# ENERGIS_Rack-PDU_1_0_0.net
KiCad netlist of a schematic drawn in EAGLE
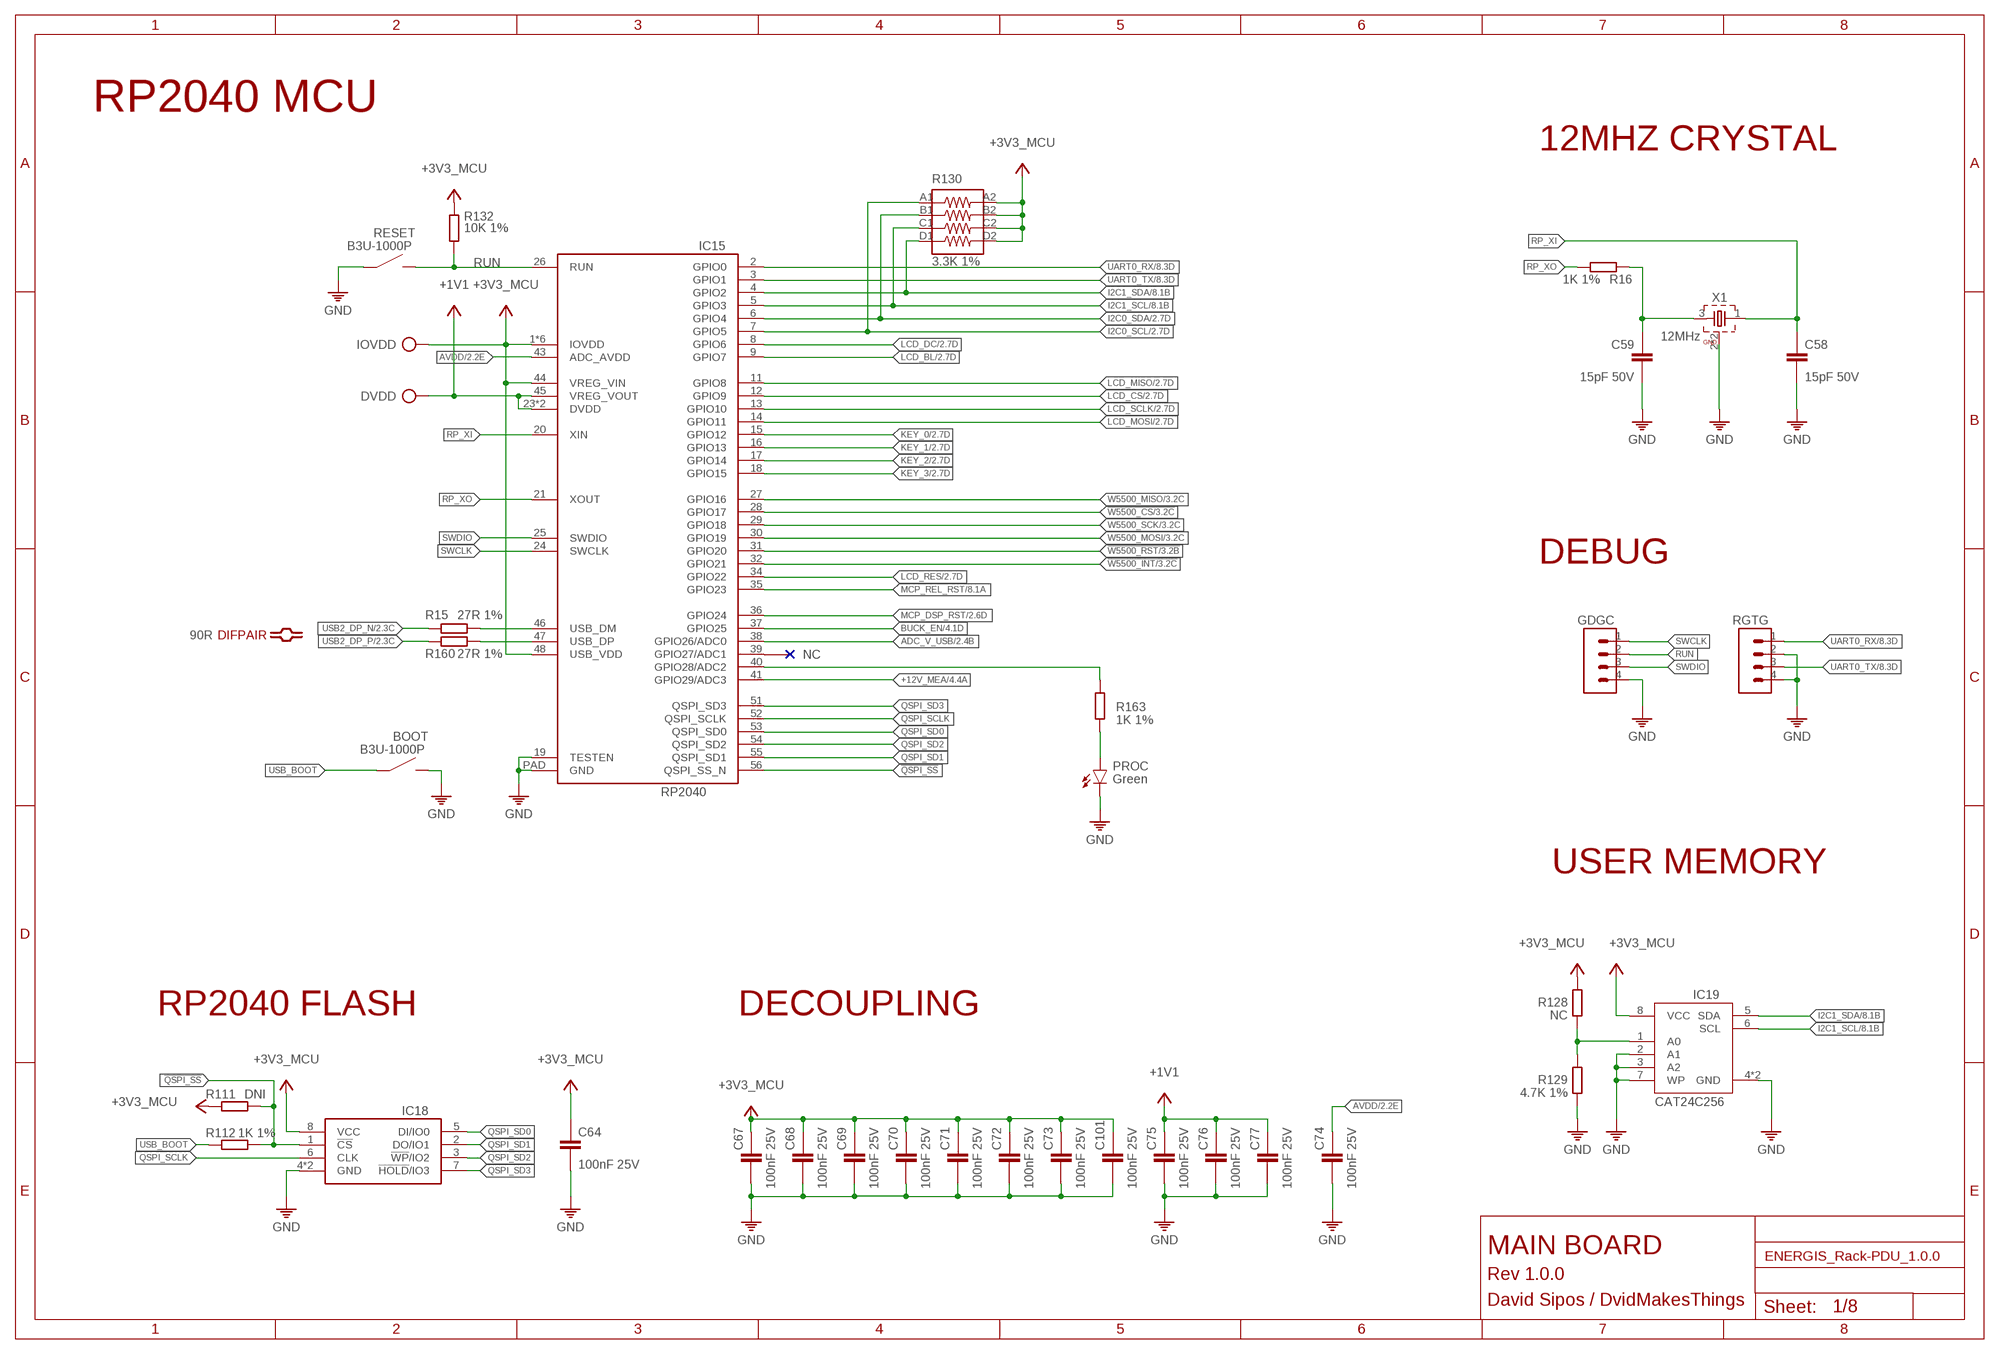
[diagram p0: schematic, sheet 1]
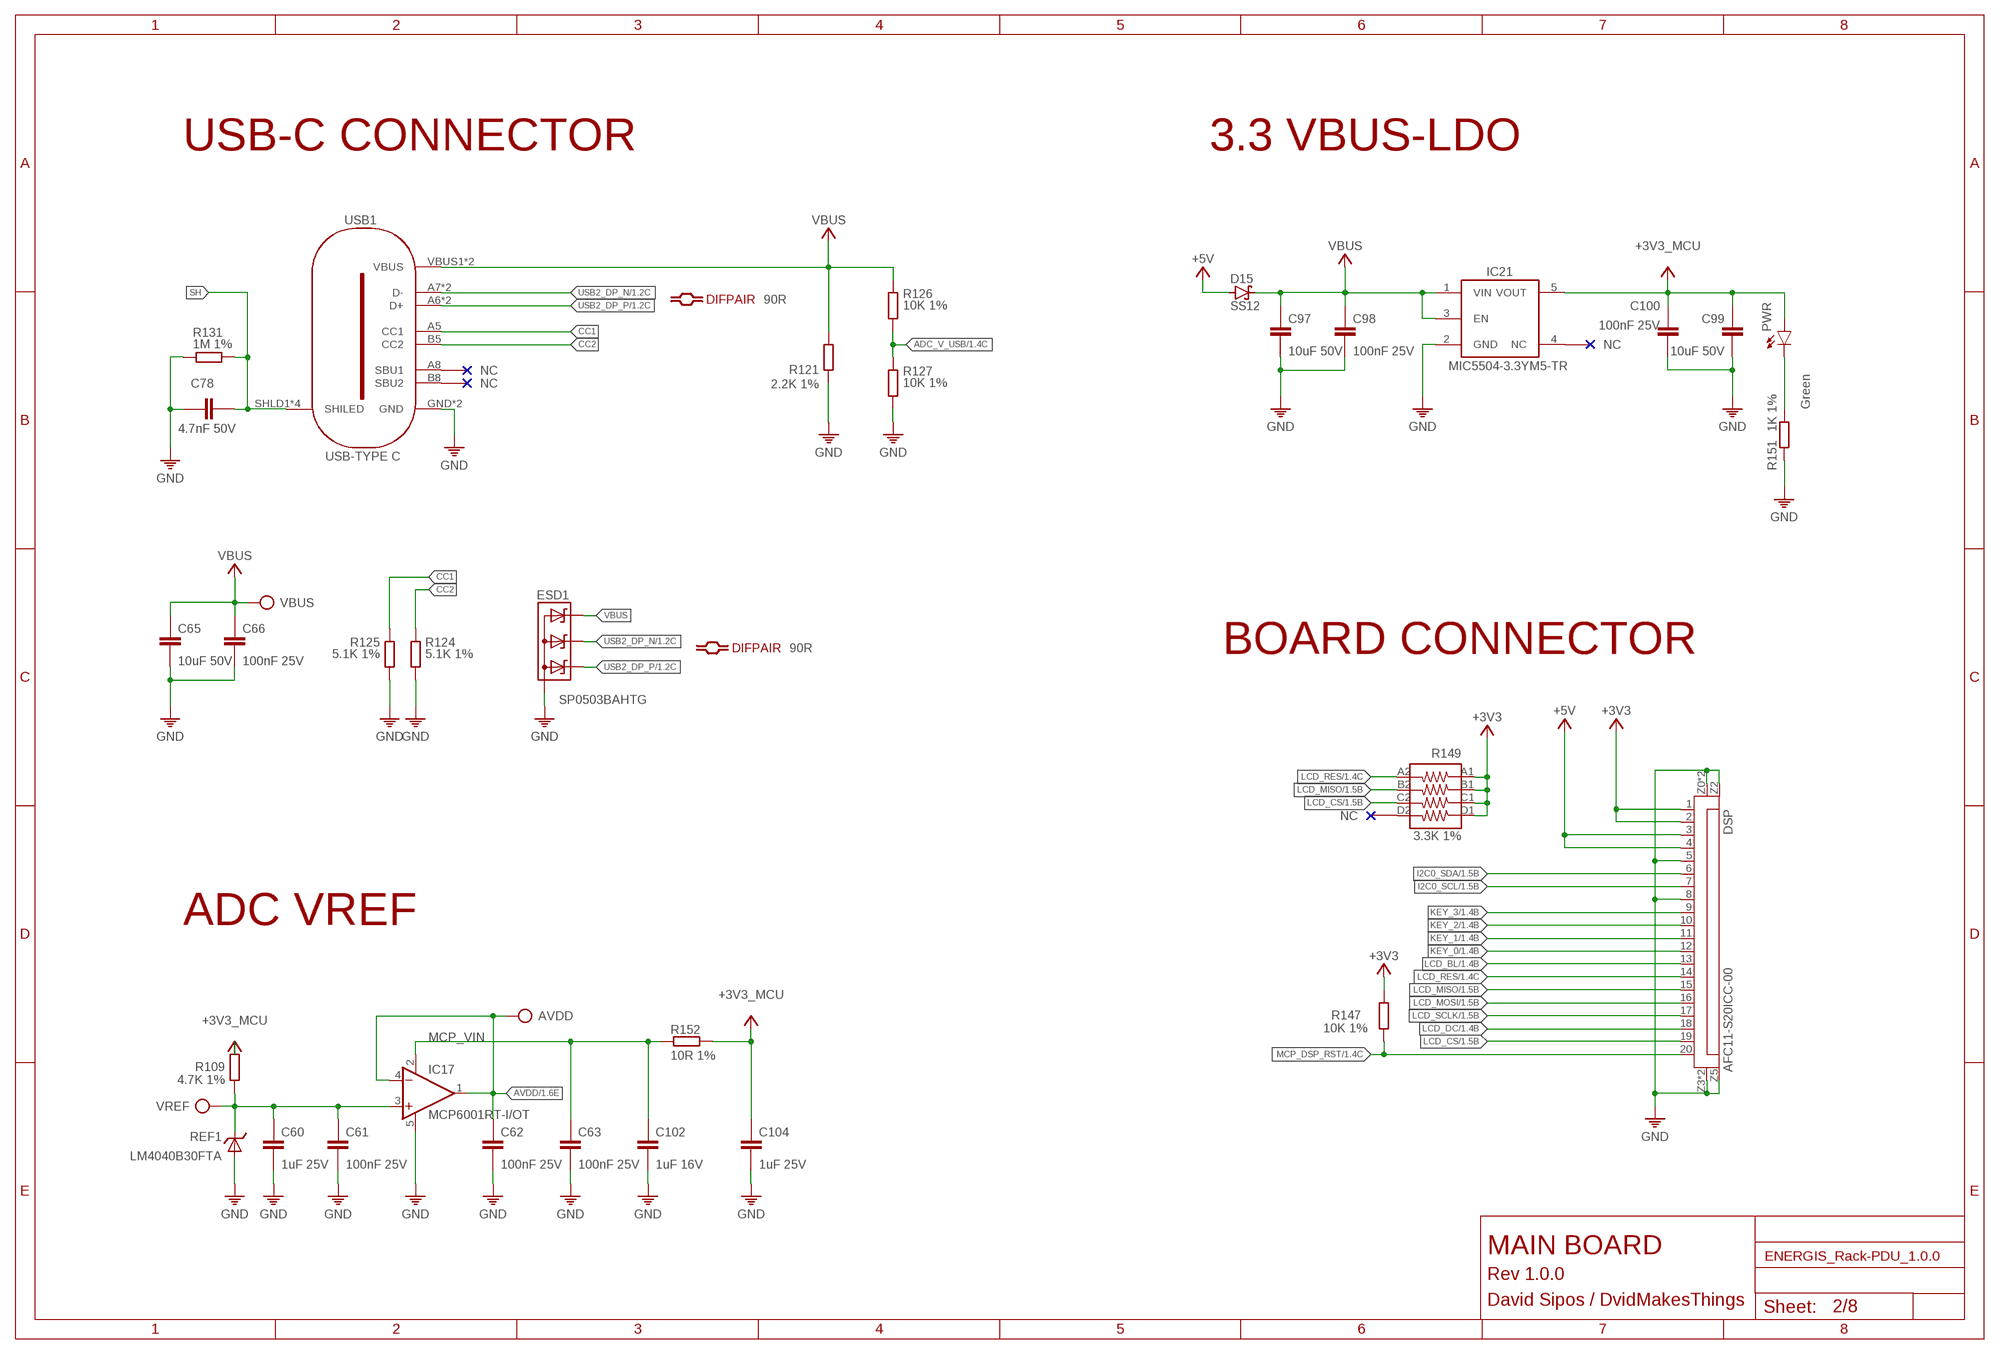
[diagram p1: schematic, sheet 2]
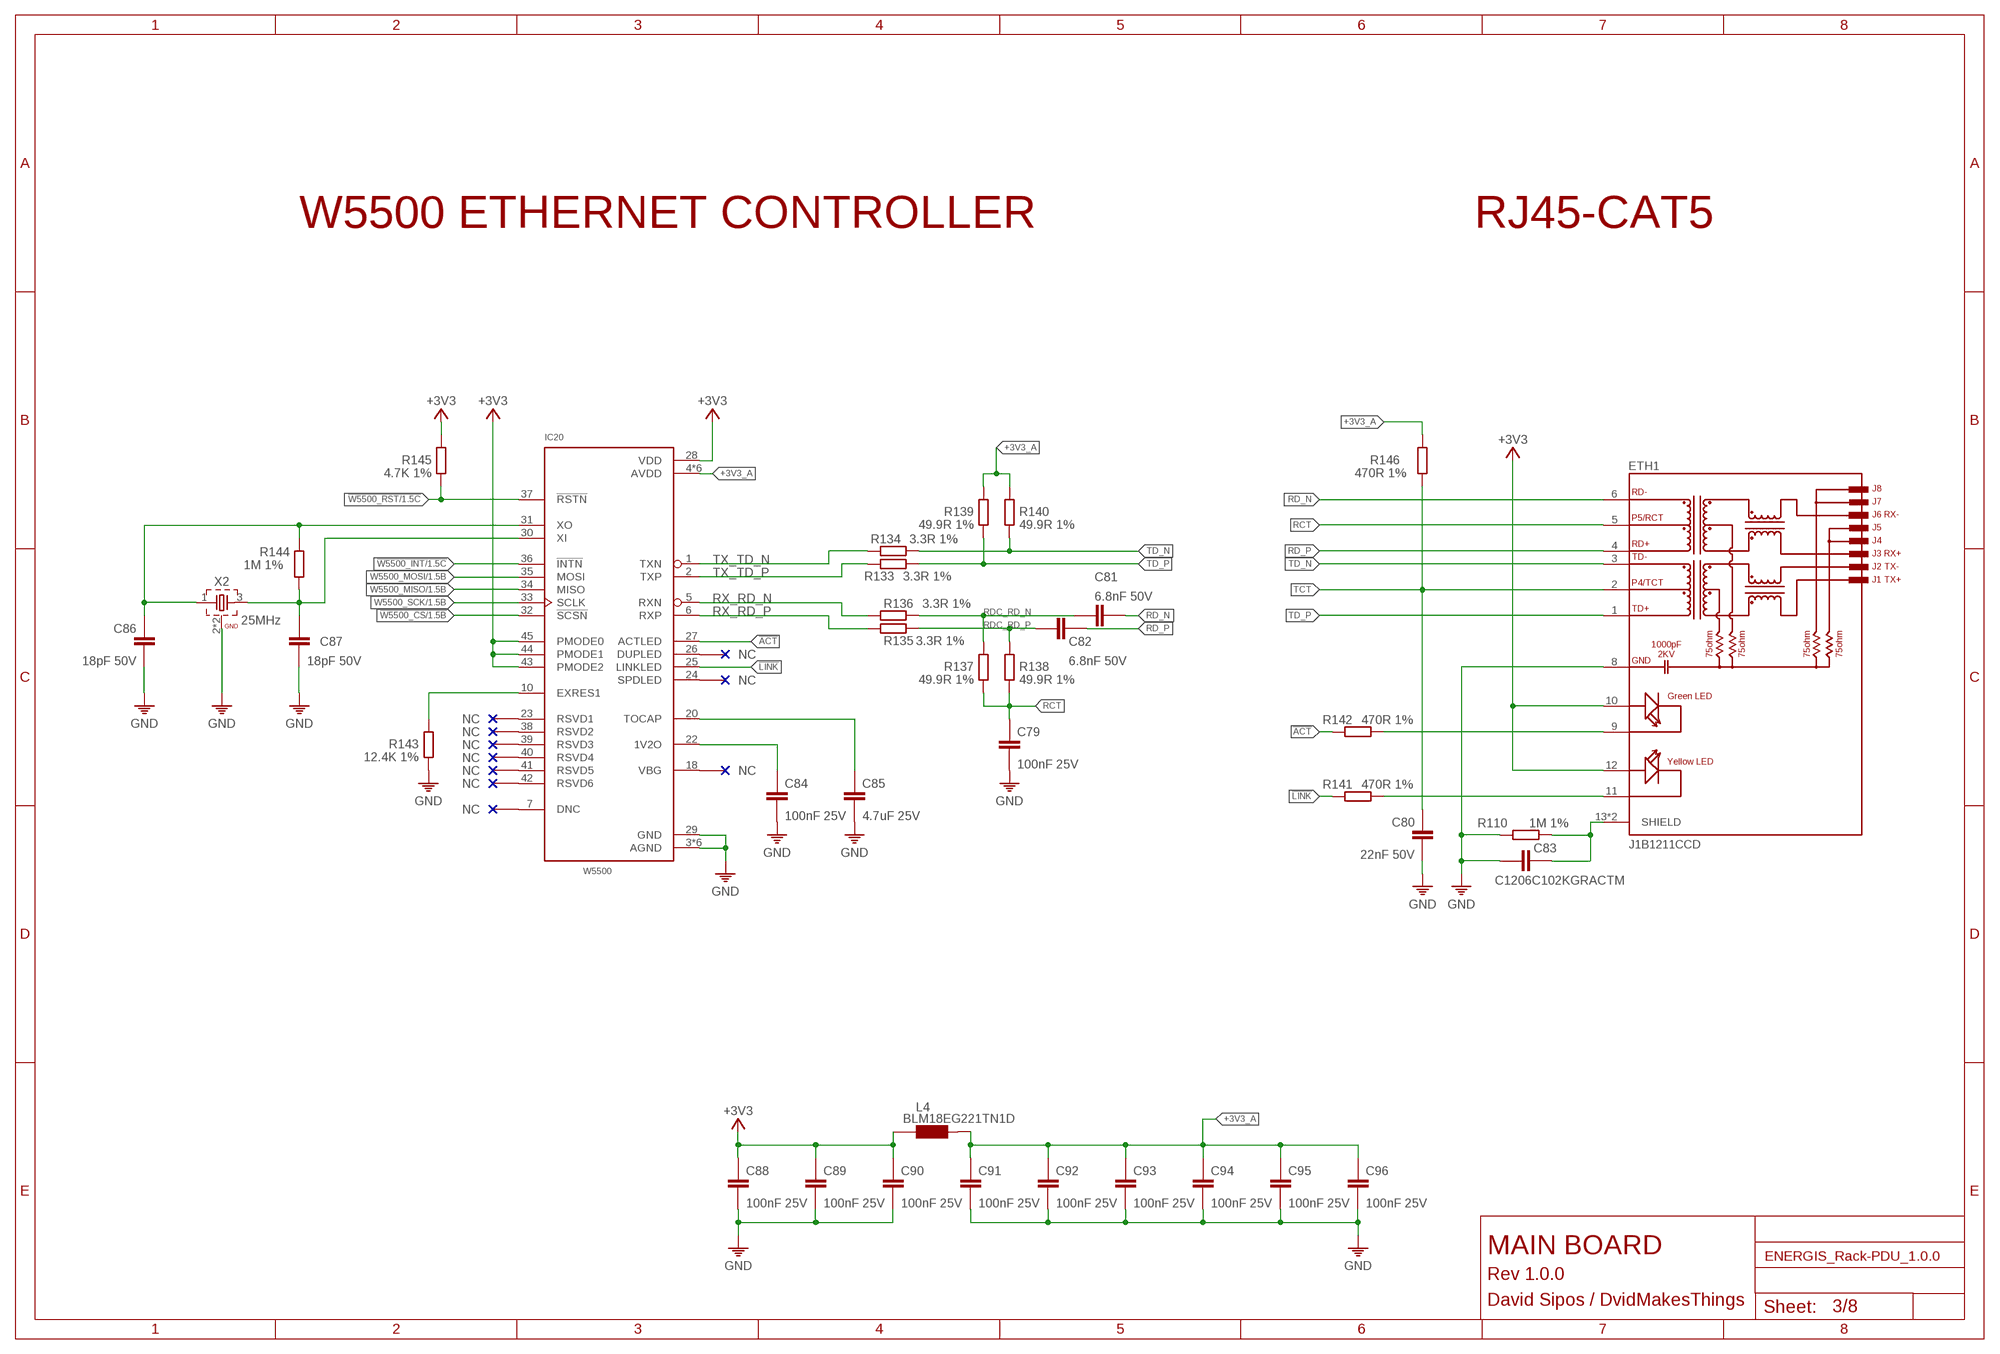
[diagram p2: schematic, sheet 3]
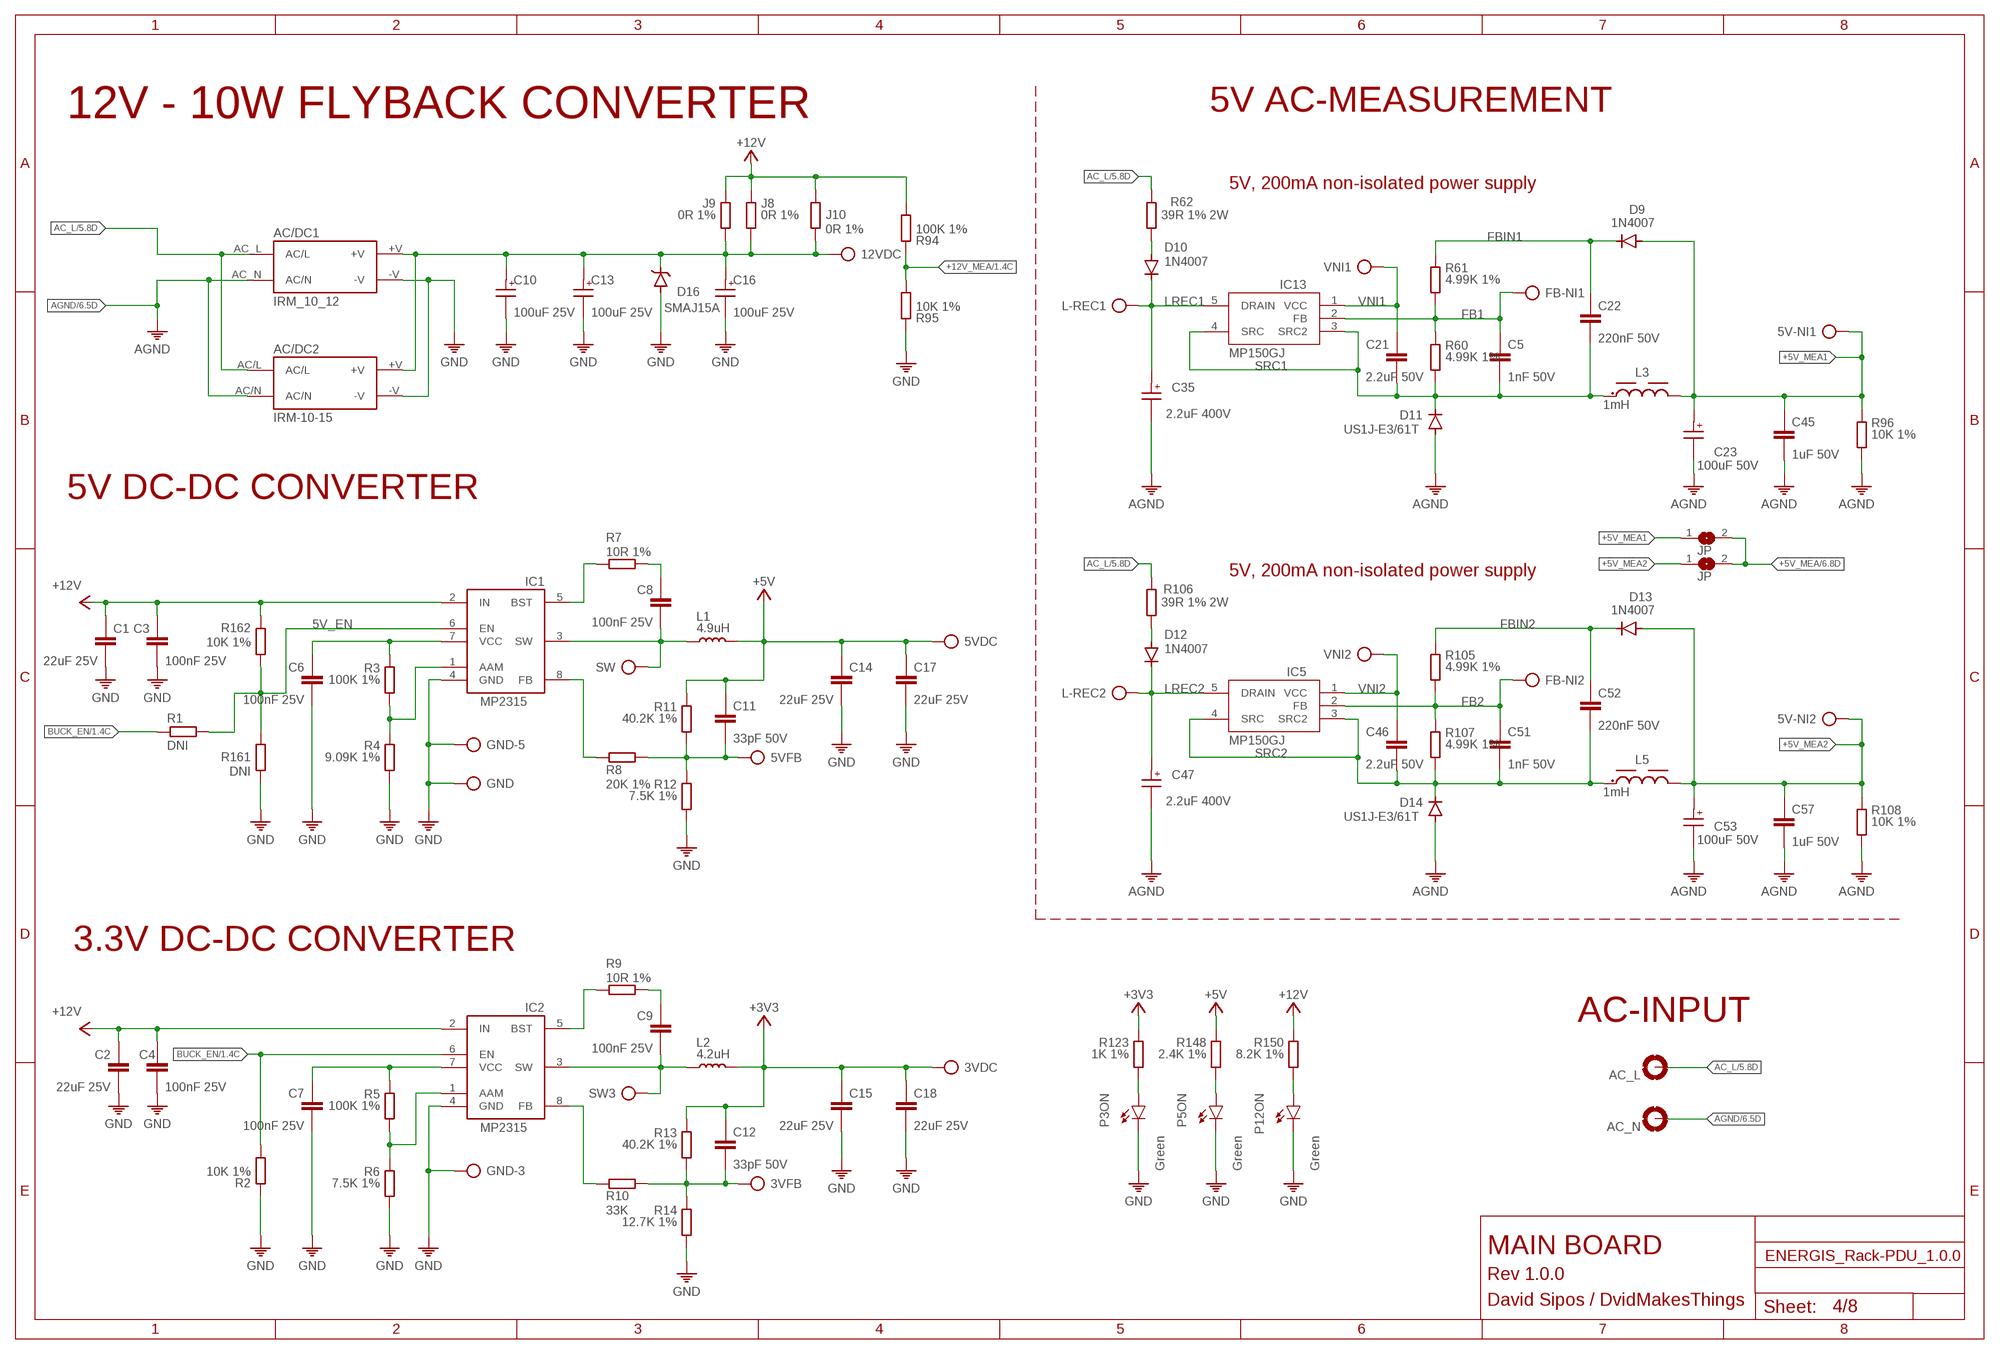
[diagram p3: schematic, sheet 4]
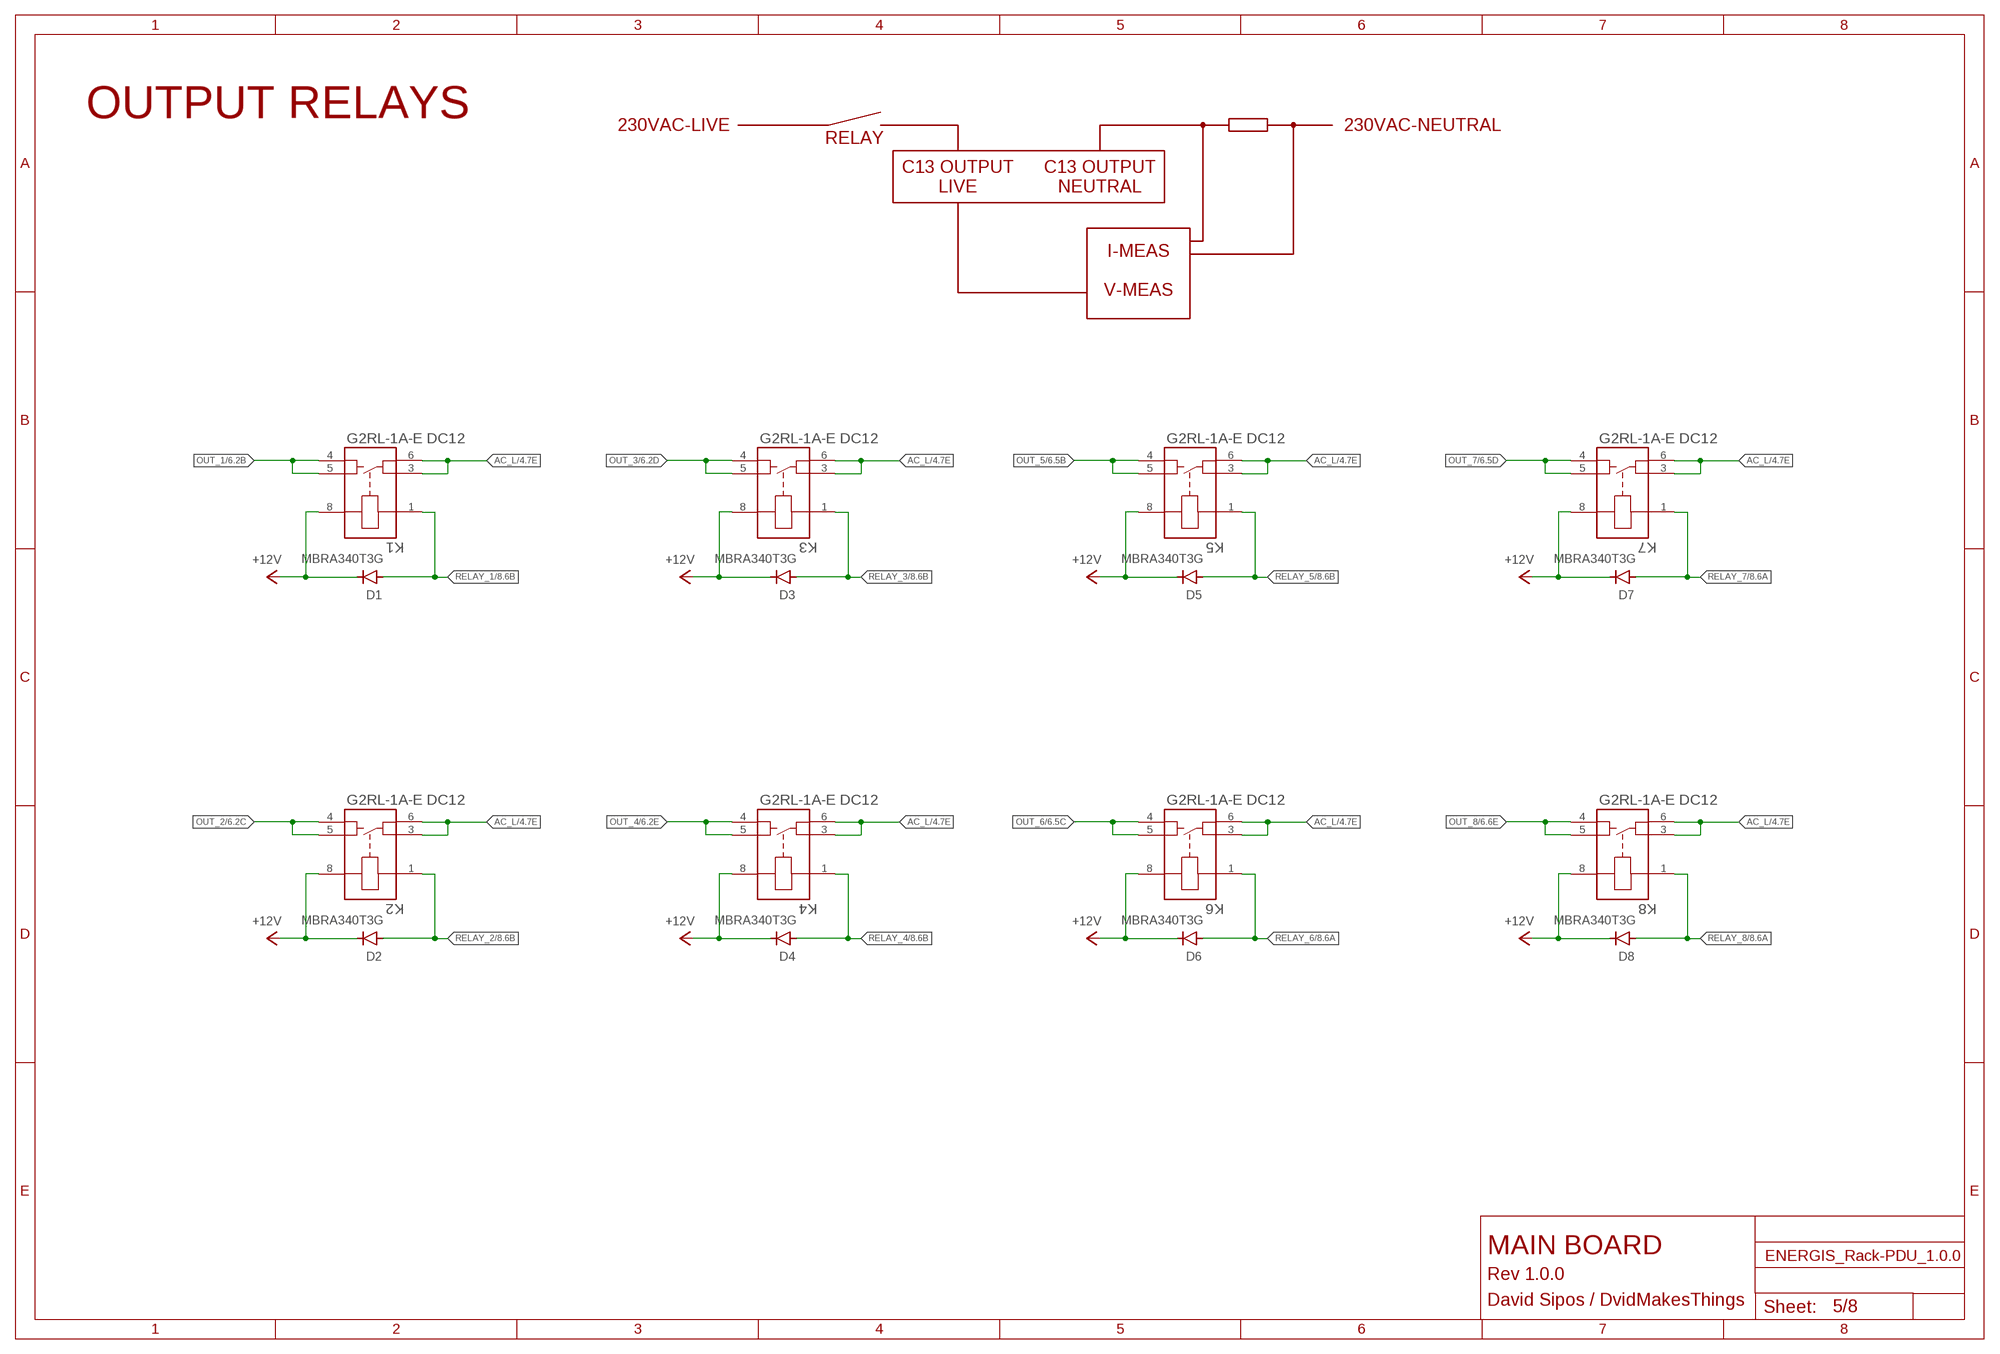
[diagram p4: schematic, sheet 5]
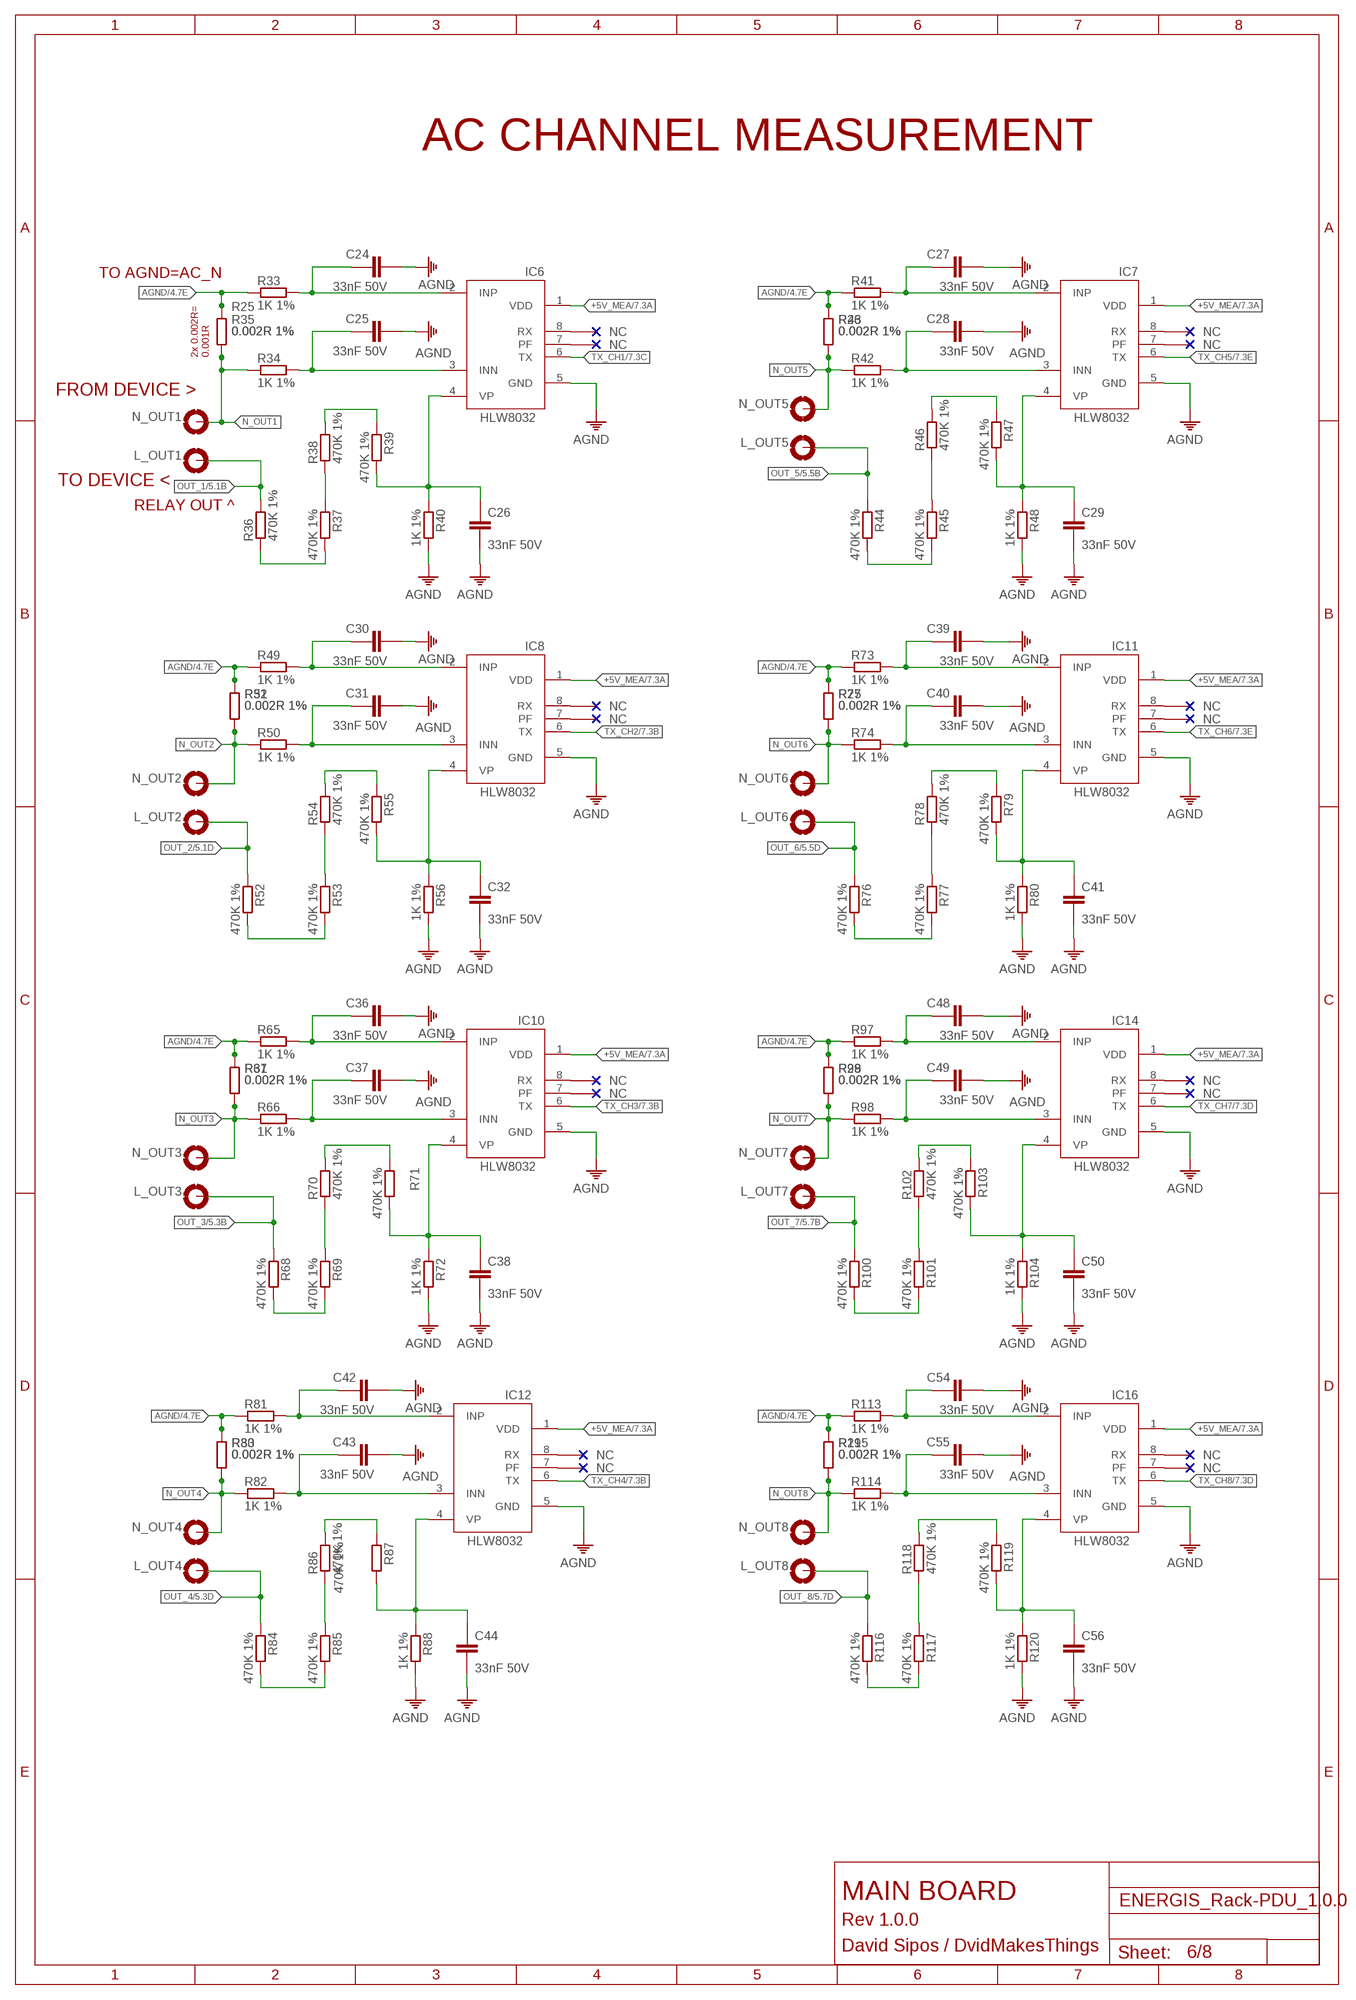
[diagram p5: schematic, sheet 6]
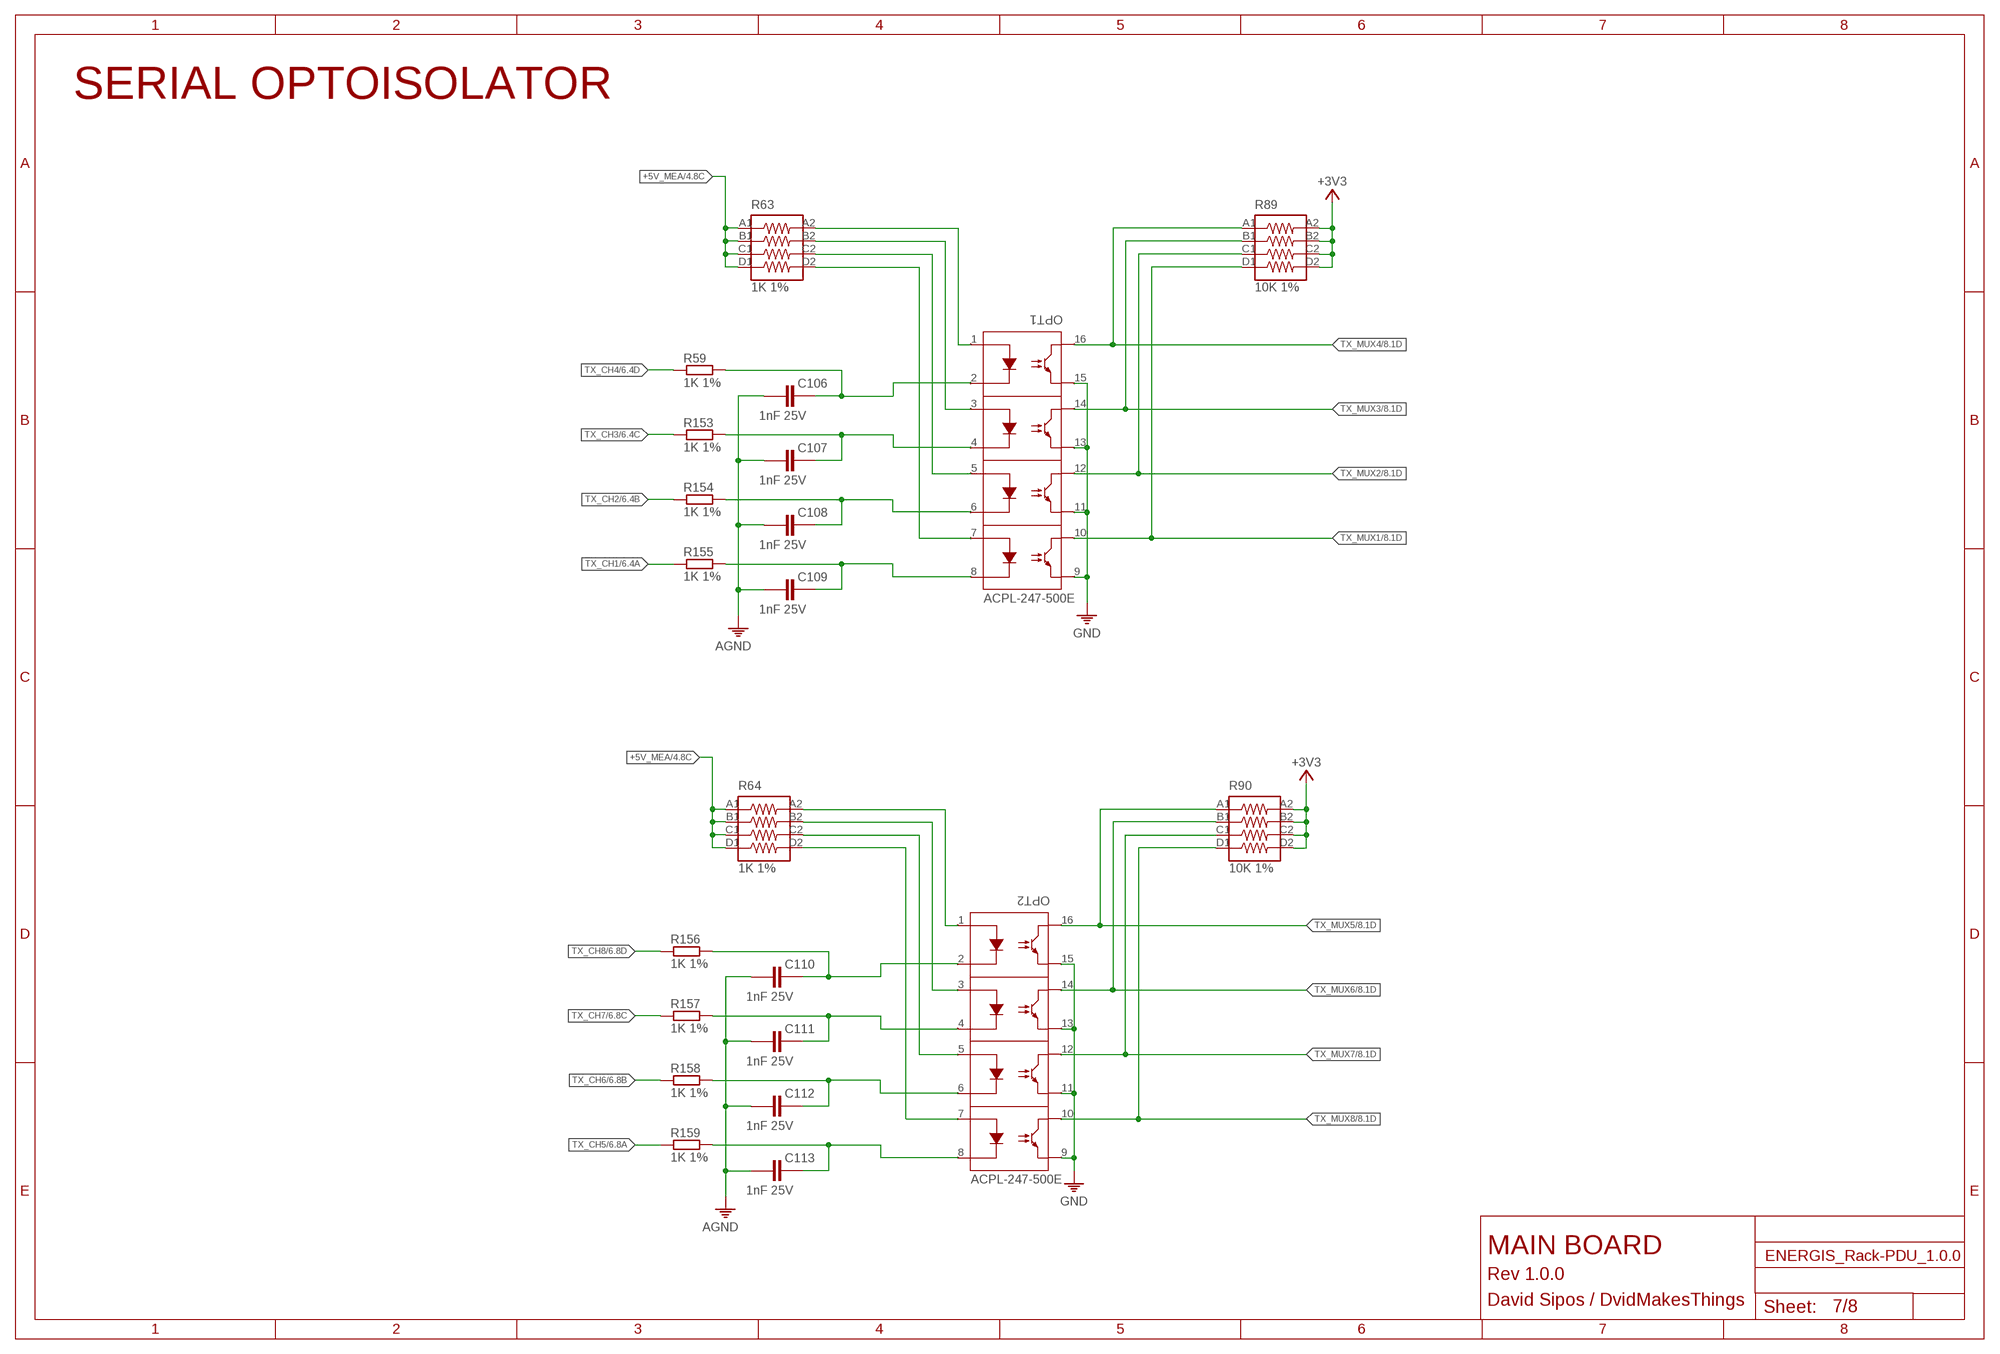
[diagram p6: schematic, sheet 7]
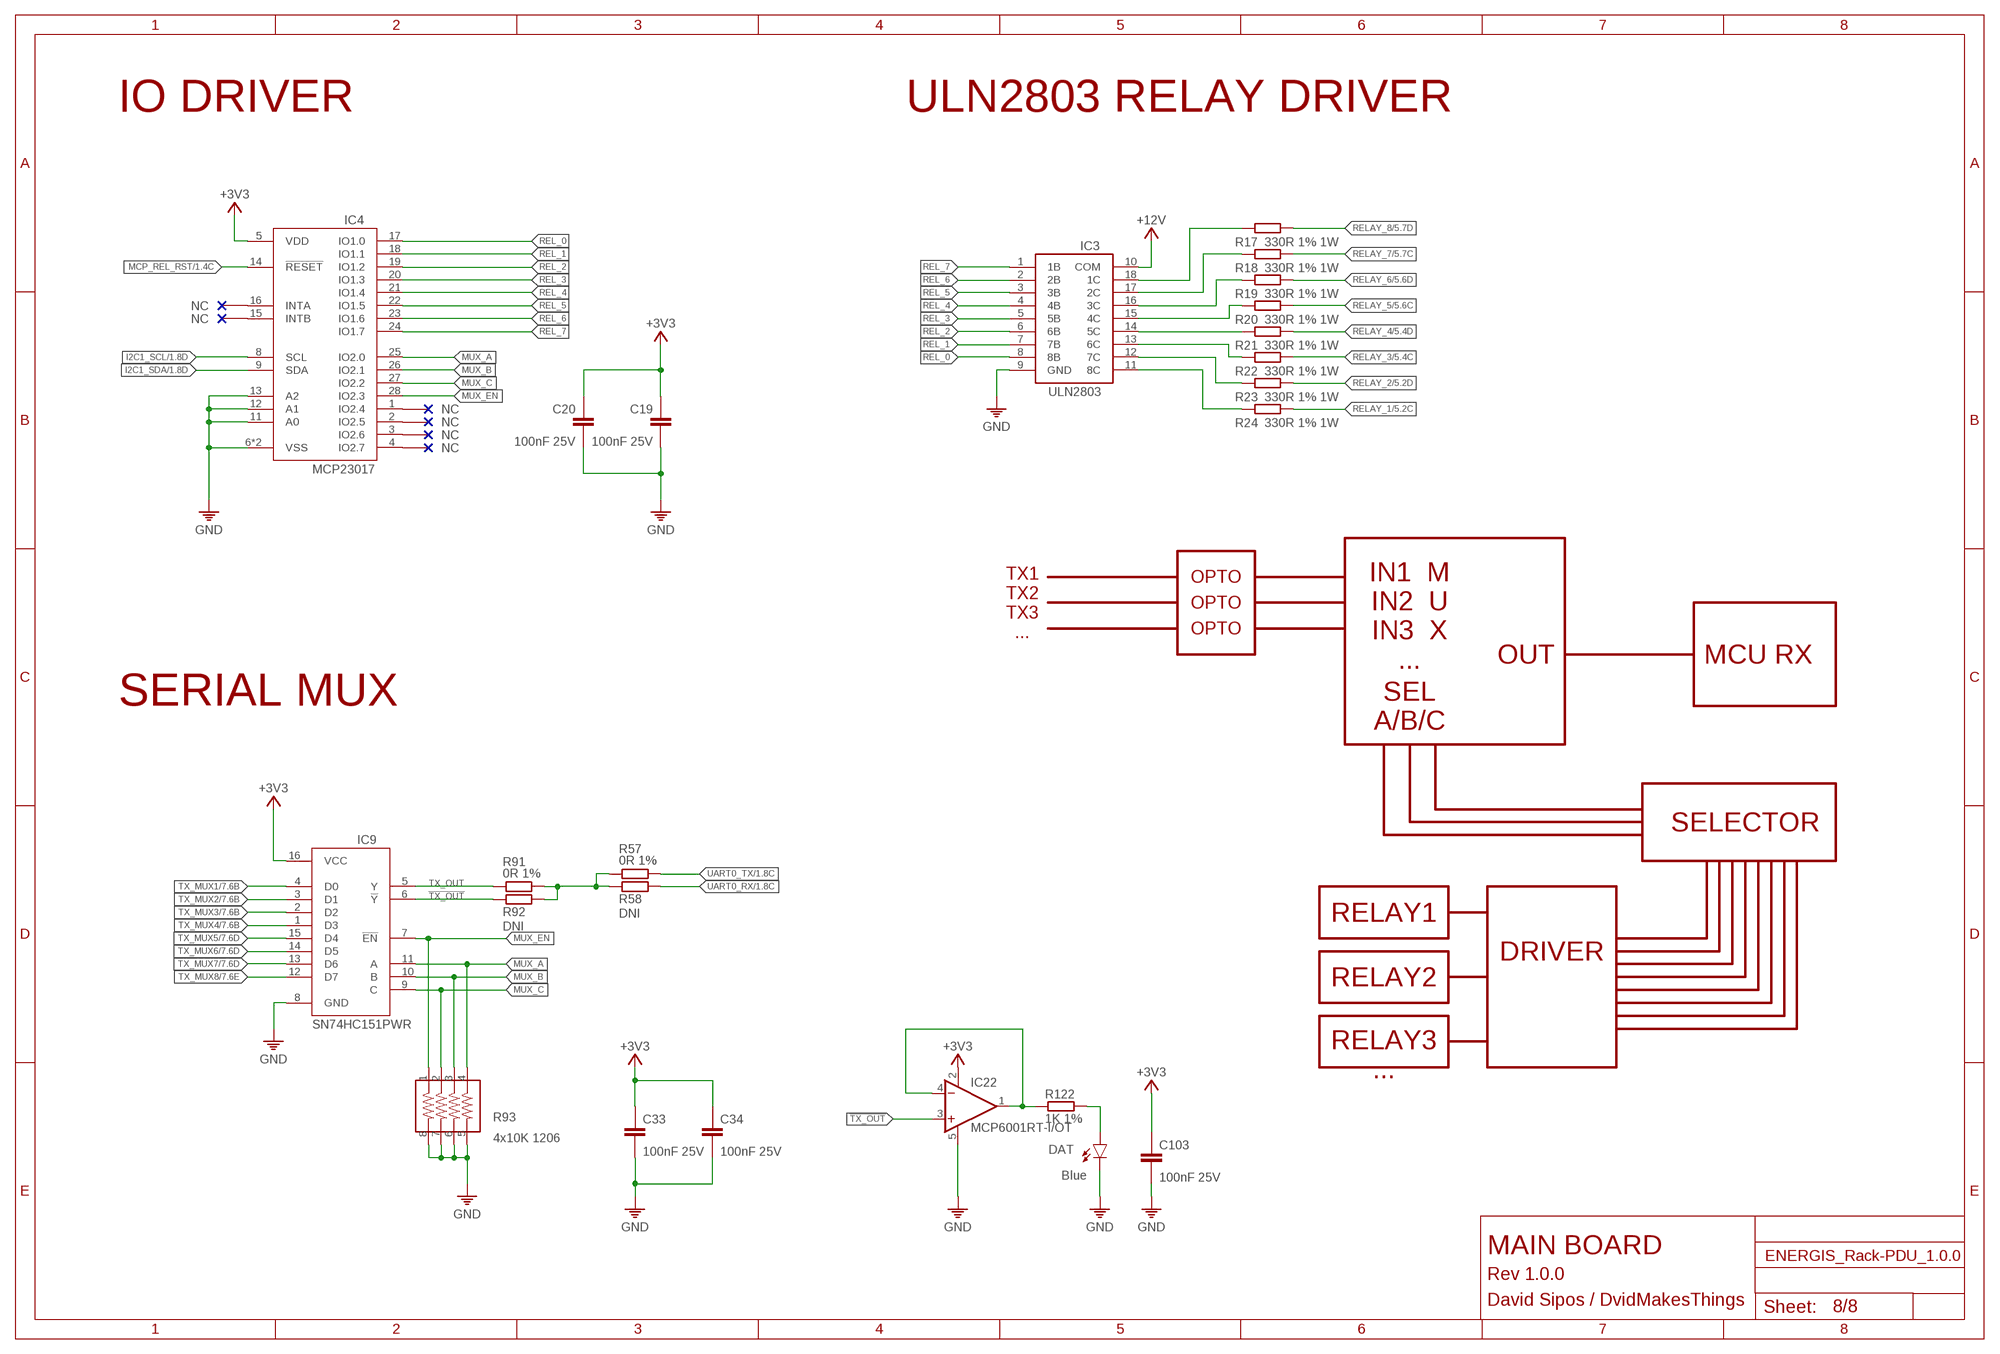
[diagram p7: schematic, sheet 8]

(export (version "E")
  (design (tool "Eeschema 10.0.6"))
  (components
    (comp (ref "D1")
      (value "MBRA340T3G")
      (footprint "eagle-import:SMA_DO-214AC")
      (fields (field (name "LCSC_PART") "C26178"))
      (libsource (lib "eagle-import") (part "MBRA340T3G"))
    )
    (comp (ref "D2")
      (value "MBRA340T3G")
      (footprint "eagle-import:SMA_DO-214AC")
      (fields (field (name "LCSC_PART") "C26178"))
      (libsource (lib "eagle-import") (part "MBRA340T3G"))
    )
    (comp (ref "D3")
      (value "MBRA340T3G")
      (footprint "eagle-import:SMA_DO-214AC")
      (fields (field (name "LCSC_PART") "C26178"))
      (libsource (lib "eagle-import") (part "MBRA340T3G"))
    )
    (comp (ref "D4")
      (value "MBRA340T3G")
      (footprint "eagle-import:SMA_DO-214AC")
      (fields (field (name "LCSC_PART") "C26178"))
      (libsource (lib "eagle-import") (part "MBRA340T3G"))
    )
    (comp (ref "D5")
      (value "MBRA340T3G")
      (footprint "eagle-import:SMA_DO-214AC")
      (fields (field (name "LCSC_PART") "C26178"))
      (libsource (lib "eagle-import") (part "MBRA340T3G"))
    )
    (comp (ref "D6")
      (value "MBRA340T3G")
      (footprint "eagle-import:SMA_DO-214AC")
      (fields (field (name "LCSC_PART") "C26178"))
      (libsource (lib "eagle-import") (part "MBRA340T3G"))
    )
    (comp (ref "D7")
      (value "MBRA340T3G")
      (footprint "eagle-import:SMA_DO-214AC")
      (fields (field (name "LCSC_PART") "C26178"))
      (libsource (lib "eagle-import") (part "MBRA340T3G"))
    )
    (comp (ref "D8")
      (value "MBRA340T3G")
      (footprint "eagle-import:SMA_DO-214AC")
      (fields (field (name "LCSC_PART") "C26178"))
      (libsource (lib "eagle-import") (part "MBRA340T3G"))
    )
    (comp (ref "K1")
      (value "G2RL-1A-E DC12")
      (footprint "eagle-import:RELAY_G2RL-1A-E_DC5_OMR")
      (fields (field (name "LCSC_PART") "C1564126"))
      (libsource (lib "eagle-import") (part "G2RL-1A-E_DC12"))
    )
    (comp (ref "K2")
      (value "G2RL-1A-E DC12")
      (footprint "eagle-import:RELAY_G2RL-1A-E_DC5_OMR")
      (fields (field (name "LCSC_PART") "C1564126"))
      (libsource (lib "eagle-import") (part "G2RL-1A-E_DC12"))
    )
    (comp (ref "K3")
      (value "G2RL-1A-E DC12")
      (footprint "eagle-import:RELAY_G2RL-1A-E_DC5_OMR")
      (fields (field (name "LCSC_PART") "C1564126"))
      (libsource (lib "eagle-import") (part "G2RL-1A-E_DC12"))
    )
    (comp (ref "K4")
      (value "G2RL-1A-E DC12")
      (footprint "eagle-import:RELAY_G2RL-1A-E_DC5_OMR")
      (fields (field (name "LCSC_PART") "C1564126"))
      (libsource (lib "eagle-import") (part "G2RL-1A-E_DC12"))
    )
    (comp (ref "K5")
      (value "G2RL-1A-E DC12")
      (footprint "eagle-import:RELAY_G2RL-1A-E_DC5_OMR")
      (fields (field (name "LCSC_PART") "C1564126"))
      (libsource (lib "eagle-import") (part "G2RL-1A-E_DC12"))
    )
    (comp (ref "K6")
      (value "G2RL-1A-E DC12")
      (footprint "eagle-import:RELAY_G2RL-1A-E_DC5_OMR")
      (fields (field (name "LCSC_PART") "C1564126"))
      (libsource (lib "eagle-import") (part "G2RL-1A-E_DC12"))
    )
    (comp (ref "K7")
      (value "G2RL-1A-E DC12")
      (footprint "eagle-import:RELAY_G2RL-1A-E_DC5_OMR")
      (fields (field (name "LCSC_PART") "C1564126"))
      (libsource (lib "eagle-import") (part "G2RL-1A-E_DC12"))
    )
    (comp (ref "K8")
      (value "G2RL-1A-E DC12")
      (footprint "eagle-import:RELAY_G2RL-1A-E_DC5_OMR")
      (fields (field (name "LCSC_PART") "C1564126"))
      (libsource (lib "eagle-import") (part "G2RL-1A-E_DC12"))
    )
    (comp (ref "C19")
      (value "100nF 25V")
      (footprint "eagle-import:0402")
      (fields (field (name "LCSC_PART") "C56392"))
      (libsource (lib "eagle-import") (part "100NF-25V-0402"))
    )
    (comp (ref "C20")
      (value "100nF 25V")
      (footprint "eagle-import:0402")
      (fields (field (name "LCSC_PART") "C56392"))
      (libsource (lib "eagle-import") (part "100NF-25V-0402"))
    )
    (comp (ref "C33")
      (value "100nF 25V")
      (footprint "eagle-import:0402")
      (fields (field (name "LCSC_PART") "C56392"))
      (libsource (lib "eagle-import") (part "100NF-25V-0402"))
    )
    (comp (ref "C34")
      (value "100nF 25V")
      (footprint "eagle-import:0402")
      (fields (field (name "LCSC_PART") "C56392"))
      (libsource (lib "eagle-import") (part "100NF-25V-0402"))
    )
    (comp (ref "C103")
      (value "100nF 25V")
      (footprint "eagle-import:0201")
      (fields (field (name "LCSC_PART") "C76939"))
      (libsource (lib "eagle-import") (part "100NF-25V-0201"))
    )
    (comp (ref "DAT")
      (value "Blue")
      (footprint "eagle-import:LED-0603")
      (fields (field (name "LCSC_PART") "C965807"))
      (libsource (lib "eagle-import") (part "LED-BLUELED-0603"))
    )
    (comp (ref "IC3")
      (value "ULN2803AFWG")
      (footprint "eagle-import:SO18")
      (fields (field (name "LCSC_PART") "C845537"))
      (libsource (lib "eagle-import") (part "ULN2803"))
    )
    (comp (ref "IC4")
      (value "MCP23017T-E/ML")
      (footprint "eagle-import:QFN28[6X6]ML")
      (fields (field (name "LCSC_PART") "C629439"))
      (libsource (lib "eagle-import") (part "MCP23017-E/ML"))
    )
    (comp (ref "IC9")
      (value "SN74HC151PWR")
      (footprint "eagle-import:TSSOP16")
      (fields (field (name "LCSC_PART") "C2653837"))
      (libsource (lib "eagle-import") (part "SN74HC151PWR"))
    )
    (comp (ref "IC22")
      (value "MCP6001RT-I/OT")
      (footprint "eagle-import:SOT23-5")
      (fields (field (name "LCSC_PART") "C154973"))
      (libsource (lib "eagle-import") (part "MCP6001RT"))
    )
    (comp (ref "R17")
      (value "330R 1% 1W")
      (footprint "eagle-import:2512")
      (fields (field (name "LCSC_PART") "C620880"))
      (libsource (lib "eagle-import") (part "330R-1%-2512"))
    )
    (comp (ref "R18")
      (value "330R 1% 1W")
      (footprint "eagle-import:2512")
      (fields (field (name "LCSC_PART") "C620880"))
      (libsource (lib "eagle-import") (part "330R-1%-2512"))
    )
    (comp (ref "R19")
      (value "330R 1% 1W")
      (footprint "eagle-import:2512")
      (fields (field (name "LCSC_PART") "C620880"))
      (libsource (lib "eagle-import") (part "330R-1%-2512"))
    )
    (comp (ref "R20")
      (value "330R 1% 1W")
      (footprint "eagle-import:2512")
      (fields (field (name "LCSC_PART") "C620880"))
      (libsource (lib "eagle-import") (part "330R-1%-2512"))
    )
    (comp (ref "R21")
      (value "330R 1% 1W")
      (footprint "eagle-import:2512")
      (fields (field (name "LCSC_PART") "C620880"))
      (libsource (lib "eagle-import") (part "330R-1%-2512"))
    )
    (comp (ref "R22")
      (value "330R 1% 1W")
      (footprint "eagle-import:2512")
      (fields (field (name "LCSC_PART") "C620880"))
      (libsource (lib "eagle-import") (part "330R-1%-2512"))
    )
    (comp (ref "R23")
      (value "330R 1% 1W")
      (footprint "eagle-import:2512")
      (fields (field (name "LCSC_PART") "C620880"))
      (libsource (lib "eagle-import") (part "330R-1%-2512"))
    )
    (comp (ref "R24")
      (value "330R 1% 1W")
      (footprint "eagle-import:2512")
      (fields (field (name "LCSC_PART") "C620880"))
      (libsource (lib "eagle-import") (part "330R-1%-2512"))
    )
    (comp (ref "R57")
      (value "0R 1%")
      (footprint "eagle-import:0402")
      (fields (field (name "LCSC_PART") "C17168"))
      (libsource (lib "eagle-import") (part "0R0402"))
    )
    (comp (ref "R58")
      (value "DNI")
      (footprint "eagle-import:0402")
      (libsource (lib "eagle-import") (part "R0402"))
    )
    (comp (ref "R91")
      (value "0R 1%")
      (footprint "eagle-import:0402")
      (fields (field (name "LCSC_PART") "C17168"))
      (libsource (lib "eagle-import") (part "0R0402"))
    )
    (comp (ref "R92")
      (value "DNI")
      (footprint "eagle-import:0402")
      (libsource (lib "eagle-import") (part "R0402"))
    )
    (comp (ref "R93")
      (value "4x10K 1206")
      (footprint "eagle-import:742C083103JP")
      (fields
        (field (name "MANUFACTURER") "CTS Resistor Products")
        (field (name "MPN") "742C083103JP")
        (field (name "CREATED_BY") "PCBLayout.com")
      )
      (libsource (lib "eagle-import") (part "742C083103JP"))
    )
    (comp (ref "R122")
      (value "1K 1%")
      (footprint "eagle-import:0402")
      (fields (field (name "LCSC_PART") "C11702"))
      (libsource (lib "eagle-import") (part "1K-1%0402"))
    )
    (comp (ref "3VDC")
      (value "TP")
      (footprint "eagle-import:TP")
      (libsource (lib "eagle-import") (part "TP"))
    )
    (comp (ref "3VFB")
      (value "TP")
      (footprint "eagle-import:TP")
      (libsource (lib "eagle-import") (part "TP"))
    )
    (comp (ref "5V-NI1")
      (value "TP")
      (footprint "eagle-import:TP")
      (libsource (lib "eagle-import") (part "TP"))
    )
    (comp (ref "5V-NI2")
      (value "TP")
      (footprint "eagle-import:TP")
      (libsource (lib "eagle-import") (part "TP"))
    )
    (comp (ref "5VDC")
      (value "TP")
      (footprint "eagle-import:TP")
      (libsource (lib "eagle-import") (part "TP"))
    )
    (comp (ref "5VFB")
      (value "TP")
      (footprint "eagle-import:TP")
      (libsource (lib "eagle-import") (part "TP"))
    )
    (comp (ref "12VDC")
      (value "TP")
      (footprint "eagle-import:TP")
      (libsource (lib "eagle-import") (part "TP"))
    )
    (comp (ref "AC/DC1")
      (value "IRM_10_12")
      (footprint "eagle-import:IRM_10_12")
      (fields (field (name "LCSC_PART") "C20618065"))
      (libsource (lib "eagle-import") (part "IRM_10_12"))
    )
    (comp (ref "AC/DC2")
      (value "IRM-10-15")
      (footprint "eagle-import:IRM_15_12")
      (fields (field (name "LCSC_PART") "C5439799"))
      (libsource (lib "eagle-import") (part "IRM_10_12-2"))
    )
    (comp (ref "AC_L")
      (value "MOUNT-PAD-ROUND3.0")
      (footprint "eagle-import:3,0-PAD")
      (libsource (lib "eagle-import") (part "MOUNT-PAD-ROUND3.0"))
    )
    (comp (ref "AC_N")
      (value "MOUNT-PAD-ROUND3.0")
      (footprint "eagle-import:3,0-PAD")
      (libsource (lib "eagle-import") (part "MOUNT-PAD-ROUND3.0"))
    )
    (comp (ref "C1")
      (value "22uF 25V")
      (footprint "eagle-import:1206")
      (fields (field (name "LCSC_PART") "C12891"))
      (libsource (lib "eagle-import") (part "22UF-25V-1206"))
    )
    (comp (ref "C2")
      (value "22uF 25V")
      (footprint "eagle-import:1206")
      (fields (field (name "LCSC_PART") "C12891"))
      (libsource (lib "eagle-import") (part "22UF-25V-1206"))
    )
    (comp (ref "C3")
      (value "100nF 25V")
      (footprint "eagle-import:0402")
      (fields (field (name "LCSC_PART") "C56392"))
      (libsource (lib "eagle-import") (part "100NF-25V-0402"))
    )
    (comp (ref "C4")
      (value "100nF 25V")
      (footprint "eagle-import:0402")
      (fields (field (name "LCSC_PART") "C56392"))
      (libsource (lib "eagle-import") (part "100NF-25V-0402"))
    )
    (comp (ref "C5")
      (value "1nF 50V")
      (footprint "eagle-import:0603")
      (fields (field (name "LCSC_PART") "C1588"))
      (libsource (lib "eagle-import") (part "1NF-50V-0603"))
    )
    (comp (ref "C6")
      (value "100nF 25V")
      (footprint "eagle-import:0402")
      (fields (field (name "LCSC_PART") "C56392"))
      (libsource (lib "eagle-import") (part "100NF-25V-0402"))
    )
    (comp (ref "C7")
      (value "100nF 25V")
      (footprint "eagle-import:0402")
      (fields (field (name "LCSC_PART") "C56392"))
      (libsource (lib "eagle-import") (part "100NF-25V-0402"))
    )
    (comp (ref "C8")
      (value "100nF 25V")
      (footprint "eagle-import:0402")
      (fields (field (name "LCSC_PART") "C56392"))
      (libsource (lib "eagle-import") (part "100NF-25V-0402"))
    )
    (comp (ref "C9")
      (value "100nF 25V")
      (footprint "eagle-import:0402")
      (fields (field (name "LCSC_PART") "C56392"))
      (libsource (lib "eagle-import") (part "100NF-25V-0402"))
    )
    (comp (ref "C10")
      (value "100uF 25V")
      (footprint "eagle-import:6.3X7.7(DXL)")
      (fields (field (name "LCSC_PART") "C267469"))
      (libsource (lib "eagle-import") (part "100UF-25V6.3X7.7(DXL)"))
    )
    (comp (ref "C11")
      (value "33pF 50V")
      (footprint "eagle-import:0402")
      (fields (field (name "LCSC_PART") "C107005"))
      (libsource (lib "eagle-import") (part "33PF-50V0402"))
    )
    (comp (ref "C12")
      (value "33pF 50V")
      (footprint "eagle-import:0402")
      (fields (field (name "LCSC_PART") "C107005"))
      (libsource (lib "eagle-import") (part "33PF-50V0402"))
    )
    (comp (ref "C13")
      (value "100uF 25V")
      (footprint "eagle-import:6.3X7.7(DXL)")
      (fields (field (name "LCSC_PART") "C267469"))
      (libsource (lib "eagle-import") (part "100UF-25V6.3X7.7(DXL)"))
    )
    (comp (ref "C14")
      (value "22uF 25V")
      (footprint "eagle-import:1206")
      (fields (field (name "LCSC_PART") "C12891"))
      (libsource (lib "eagle-import") (part "22UF-25V-1206"))
    )
    (comp (ref "C15")
      (value "22uF 25V")
      (footprint "eagle-import:1206")
      (fields (field (name "LCSC_PART") "C12891"))
      (libsource (lib "eagle-import") (part "22UF-25V-1206"))
    )
    (comp (ref "C16")
      (value "100uF 25V")
      (footprint "eagle-import:6.3X7.7(DXL)")
      (fields (field (name "LCSC_PART") "C267469"))
      (libsource (lib "eagle-import") (part "100UF-25V6.3X7.7(DXL)"))
    )
    (comp (ref "C17")
      (value "22uF 25V")
      (footprint "eagle-import:1206")
      (fields (field (name "LCSC_PART") "C12891"))
      (libsource (lib "eagle-import") (part "22UF-25V-1206"))
    )
    (comp (ref "C18")
      (value "22uF 25V")
      (footprint "eagle-import:1206")
      (fields (field (name "LCSC_PART") "C12891"))
      (libsource (lib "eagle-import") (part "22UF-25V-1206"))
    )
    (comp (ref "C21")
      (value "2.2uF 50V")
      (footprint "eagle-import:0603")
      (fields (field (name "LCSC_PART") "C913904"))
      (libsource (lib "eagle-import") (part "2.2UF-50V0603"))
    )
    (comp (ref "C22")
      (value "220nF 50V")
      (footprint "eagle-import:0805")
      (fields (field (name "LCSC_PART") "C5378"))
      (libsource (lib "eagle-import") (part "220NF-50V0805"))
    )
    (comp (ref "C23")
      (value "100uF 50V")
      (footprint "eagle-import:6.3X7.7(DXL)")
      (fields (field (name "LCSC_PART") "C3151829"))
      (libsource (lib "eagle-import") (part "100UF-50V6.3X7.7(DXL)"))
    )
    (comp (ref "C35")
      (value "2.2uF 400V")
      (footprint "eagle-import:6.3X7.7(DXL)")
      (fields (field (name "LCSC_PART") "C3345109"))
      (libsource (lib "eagle-import") (part "2.2UF-400V6.3X7.7(DXL)"))
    )
    (comp (ref "C45")
      (value "1uF 50V")
      (footprint "eagle-import:0805")
      (fields (field (name "LCSC_PART") "C28323"))
      (libsource (lib "eagle-import") (part "1UF-50V0805"))
    )
    (comp (ref "C46")
      (value "2.2uF 50V")
      (footprint "eagle-import:0603")
      (fields (field (name "LCSC_PART") "C913904"))
      (libsource (lib "eagle-import") (part "2.2UF-50V0603"))
    )
    (comp (ref "C47")
      (value "2.2uF 400V")
      (footprint "eagle-import:6.3X7.7(DXL)")
      (fields (field (name "LCSC_PART") "C3345109"))
      (libsource (lib "eagle-import") (part "2.2UF-400V6.3X7.7(DXL)"))
    )
    (comp (ref "C51")
      (value "1nF 50V")
      (footprint "eagle-import:0603")
      (fields (field (name "LCSC_PART") "C1588"))
      (libsource (lib "eagle-import") (part "1NF-50V-0603"))
    )
    (comp (ref "C52")
      (value "220nF 50V")
      (footprint "eagle-import:0805")
      (fields (field (name "LCSC_PART") "C5378"))
      (libsource (lib "eagle-import") (part "220NF-50V0805"))
    )
    (comp (ref "C53")
      (value "100uF 50V")
      (footprint "eagle-import:6.3X7.7(DXL)")
      (fields (field (name "LCSC_PART") "C3151829"))
      (libsource (lib "eagle-import") (part "100UF-50V6.3X7.7(DXL)"))
    )
    (comp (ref "C57")
      (value "1uF 50V")
      (footprint "eagle-import:0805")
      (fields (field (name "LCSC_PART") "C28323"))
      (libsource (lib "eagle-import") (part "1UF-50V0805"))
    )
    (comp (ref "D9")
      (value "1N4007")
      (footprint "eagle-import:SMA_DO-214AC")
      (fields (field (name "LCSC_PART") "C727081"))
      (libsource (lib "eagle-import") (part "1N4007"))
    )
    (comp (ref "D10")
      (value "1N4007")
      (footprint "eagle-import:SMA_DO-214AC")
      (fields (field (name "LCSC_PART") "C727081"))
      (libsource (lib "eagle-import") (part "1N4007"))
    )
    (comp (ref "D11")
      (value "US1J-E3/61T")
      (footprint "eagle-import:SMA_DO-214AC")
      (fields (field (name "LCSC_PART") "C44763"))
      (libsource (lib "eagle-import") (part "US1J-E3/61T"))
    )
    (comp (ref "D12")
      (value "1N4007")
      (footprint "eagle-import:SMA_DO-214AC")
      (fields (field (name "LCSC_PART") "C727081"))
      (libsource (lib "eagle-import") (part "1N4007"))
    )
    (comp (ref "D13")
      (value "1N4007")
      (footprint "eagle-import:SMA_DO-214AC")
      (fields (field (name "LCSC_PART") "C727081"))
      (libsource (lib "eagle-import") (part "1N4007"))
    )
    (comp (ref "D14")
      (value "US1J-E3/61T")
      (footprint "eagle-import:SMA_DO-214AC")
      (fields (field (name "LCSC_PART") "C44763"))
      (libsource (lib "eagle-import") (part "US1J-E3/61T"))
    )
    (comp (ref "D16")
      (value "SMAJ15A")
      (footprint "eagle-import:SMA_DO-214AC")
      (fields (field (name "LCSC_PART") "C23424"))
      (libsource (lib "eagle-import") (part "SMAJ15A"))
    )
    (comp (ref "FB-NI1")
      (value "TP")
      (footprint "eagle-import:TP")
      (libsource (lib "eagle-import") (part "TP"))
    )
    (comp (ref "FB-NI2")
      (value "TP")
      (footprint "eagle-import:TP")
      (libsource (lib "eagle-import") (part "TP"))
    )
    (comp (ref "GND") (value "TP") (footprint "eagle-import:TP") (libsource (lib "eagle-import") (part "TP")))
    (comp (ref "GND-3")
      (value "TP")
      (footprint "eagle-import:TP")
      (libsource (lib "eagle-import") (part "TP"))
    )
    (comp (ref "GND-5")
      (value "TP")
      (footprint "eagle-import:TP")
      (libsource (lib "eagle-import") (part "TP"))
    )
    (comp (ref "IC1")
      (value "MP2315GJ-Z")
      (footprint "eagle-import:SOT65P280X110-8N")
      (fields (field (name "LCSC_PART") "C45889"))
      (libsource (lib "eagle-import") (part "MP2315TSOT23-8"))
    )
    (comp (ref "IC2")
      (value "MP2315GJ-Z")
      (footprint "eagle-import:SOT65P280X110-8N")
      (fields (field (name "LCSC_PART") "C45889"))
      (libsource (lib "eagle-import") (part "MP2315TSOT23-8"))
    )
    (comp (ref "IC5")
      (value "MP150GJ")
      (footprint "eagle-import:SOT23-5")
      (libsource (lib "eagle-import") (part "MP150GJ"))
    )
    (comp (ref "IC13")
      (value "MP150GJ")
      (footprint "eagle-import:SOT23-5")
      (libsource (lib "eagle-import") (part "MP150GJ"))
    )
    (comp (ref "J2") (value "JP") (footprint "eagle-import:SJ") (libsource (lib "eagle-import") (part "SJ")))
    (comp (ref "J7") (value "JP") (footprint "eagle-import:SJ") (libsource (lib "eagle-import") (part "SJ")))
    (comp (ref "J8")
      (value "0R 1%")
      (footprint "eagle-import:0805")
      (fields (field (name "LCSC_PART") "C17477"))
      (libsource (lib "eagle-import") (part "0R0805"))
    )
    (comp (ref "J9")
      (value "0R 1%")
      (footprint "eagle-import:0805")
      (fields (field (name "LCSC_PART") "C17477"))
      (libsource (lib "eagle-import") (part "0R0805"))
    )
    (comp (ref "J10")
      (value "0R 1%")
      (footprint "eagle-import:0805")
      (fields (field (name "LCSC_PART") "C17477"))
      (libsource (lib "eagle-import") (part "0R0805"))
    )
    (comp (ref "L-REC1")
      (value "TP")
      (footprint "eagle-import:TP")
      (libsource (lib "eagle-import") (part "TP"))
    )
    (comp (ref "L-REC2")
      (value "TP")
      (footprint "eagle-import:TP")
      (libsource (lib "eagle-import") (part "TP"))
    )
    (comp (ref "L1")
      (value "4.9uH")
      (footprint "eagle-import:SRR5228A")
      (libsource (lib "eagle-import") (part "L"))
    )
    (comp (ref "L2")
      (value "4.2uH")
      (footprint "eagle-import:SRR5228A")
      (libsource (lib "eagle-import") (part "L"))
    )
    (comp (ref "L3")
      (value "1mH")
      (footprint "eagle-import:L-6.6X6.6")
      (fields (field (name "LCSC_PART") "C168049"))
      (libsource (lib "eagle-import") (part "1MHL-6.6X6.6"))
    )
    (comp (ref "L5")
      (value "1mH")
      (footprint "eagle-import:L-6.6X6.6")
      (fields (field (name "LCSC_PART") "C168049"))
      (libsource (lib "eagle-import") (part "1MHL-6.6X6.6"))
    )
    (comp (ref "P3ON")
      (value "Green")
      (footprint "eagle-import:LED-0603")
      (fields (field (name "LCSC_PART") "C965804"))
      (libsource (lib "eagle-import") (part "LED-GREENLED-0603"))
    )
    (comp (ref "P5ON")
      (value "Green")
      (footprint "eagle-import:LED-0603")
      (fields (field (name "LCSC_PART") "C965804"))
      (libsource (lib "eagle-import") (part "LED-GREENLED-0603"))
    )
    (comp (ref "P12ON")
      (value "Green")
      (footprint "eagle-import:LED-0603")
      (fields (field (name "LCSC_PART") "C965804"))
      (libsource (lib "eagle-import") (part "LED-GREENLED-0603"))
    )
    (comp (ref "R1")
      (value "DNI")
      (footprint "eagle-import:0402")
      (libsource (lib "eagle-import") (part "R0402"))
    )
    (comp (ref "R2")
      (value "10K 1%")
      (footprint "eagle-import:0402")
      (fields (field (name "LCSC_PART") "C25744"))
      (libsource (lib "eagle-import") (part "10K-1%0402"))
    )
    (comp (ref "R3")
      (value "100K 1%")
      (footprint "eagle-import:0402")
      (fields (field (name "LCSC_PART") "C25741"))
      (libsource (lib "eagle-import") (part "100K-1%0402"))
    )
    (comp (ref "R4")
      (value "9.09K 1%")
      (footprint "eagle-import:0402")
      (fields (field (name "LCSC_PART") "C11549"))
      (libsource (lib "eagle-import") (part "9.09K-1%0402"))
    )
    (comp (ref "R5")
      (value "100K 1%")
      (footprint "eagle-import:0402")
      (fields (field (name "LCSC_PART") "C25741"))
      (libsource (lib "eagle-import") (part "100K-1%0402"))
    )
    (comp (ref "R6")
      (value "7.5K 1%")
      (footprint "eagle-import:0402")
      (fields (field (name "LCSC_PART") "C25918"))
      (libsource (lib "eagle-import") (part "7.5K-1%0402"))
    )
    (comp (ref "R7")
      (value "10R 1%")
      (footprint "eagle-import:0402")
      (fields (field (name "LCSC_PART") "C25077"))
      (libsource (lib "eagle-import") (part "10R-1%0402"))
    )
    (comp (ref "R8")
      (value "20K 1%")
      (footprint "eagle-import:0402")
      (fields (field (name "LCSC_PART") "C25765"))
      (libsource (lib "eagle-import") (part "20K-1%0402"))
    )
    (comp (ref "R9")
      (value "10R 1%")
      (footprint "eagle-import:0402")
      (fields (field (name "LCSC_PART") "C25077"))
      (libsource (lib "eagle-import") (part "10R-1%0402"))
    )
    (comp (ref "R10")
      (value "33K")
      (footprint "eagle-import:0402")
      (libsource (lib "eagle-import") (part "R0402"))
    )
    (comp (ref "R11")
      (value "40.2K 1%")
      (footprint "eagle-import:0402")
      (fields (field (name "LCSC_PART") "C25893"))
      (libsource (lib "eagle-import") (part "40.2K-1%0402"))
    )
    (comp (ref "R12")
      (value "7.5K 1%")
      (footprint "eagle-import:0402")
      (fields (field (name "LCSC_PART") "C25918"))
      (libsource (lib "eagle-import") (part "7.5K-1%0402"))
    )
    (comp (ref "R13")
      (value "40.2K 1%")
      (footprint "eagle-import:0402")
      (fields (field (name "LCSC_PART") "C25893"))
      (libsource (lib "eagle-import") (part "40.2K-1%0402"))
    )
    (comp (ref "R14")
      (value "12.7K 1%")
      (footprint "eagle-import:0402")
      (fields (field (name "LCSC_PART") "C25853"))
      (libsource (lib "eagle-import") (part "12.7K-1%0402"))
    )
    (comp (ref "R60")
      (value "4.99K 1%")
      (footprint "eagle-import:0603")
      (fields (field (name "LCSC_PART") "C23046"))
      (libsource (lib "eagle-import") (part "4.99K-1%0603"))
    )
    (comp (ref "R61")
      (value "4.99K 1%")
      (footprint "eagle-import:0603")
      (fields (field (name "LCSC_PART") "C23046"))
      (libsource (lib "eagle-import") (part "4.99K-1%0603"))
    )
    (comp (ref "R62")
      (value "39R 1% 2W")
      (footprint "eagle-import:2512")
      (fields (field (name "LCSC_PART") "C175263"))
      (libsource (lib "eagle-import") (part "39R-1%2512"))
    )
    (comp (ref "R94")
      (value "100K 1%")
      (footprint "eagle-import:0402")
      (fields (field (name "LCSC_PART") "C25741"))
      (libsource (lib "eagle-import") (part "100K-1%0402"))
    )
    (comp (ref "R95")
      (value "10K 1%")
      (footprint "eagle-import:0402")
      (fields (field (name "LCSC_PART") "C25744"))
      (libsource (lib "eagle-import") (part "10K-1%0402"))
    )
    (comp (ref "R96")
      (value "10K 1%")
      (footprint "eagle-import:0805")
      (fields (field (name "LCSC_PART") "C17414"))
      (libsource (lib "eagle-import") (part "10K-1%0805"))
    )
    (comp (ref "R105")
      (value "4.99K 1%")
      (footprint "eagle-import:0603")
      (fields (field (name "LCSC_PART") "C23046"))
      (libsource (lib "eagle-import") (part "4.99K-1%0603"))
    )
    (comp (ref "R106")
      (value "39R 1% 2W")
      (footprint "eagle-import:2512")
      (fields (field (name "LCSC_PART") "C175263"))
      (libsource (lib "eagle-import") (part "39R-1%2512"))
    )
    (comp (ref "R107")
      (value "4.99K 1%")
      (footprint "eagle-import:0603")
      (fields (field (name "LCSC_PART") "C23046"))
      (libsource (lib "eagle-import") (part "4.99K-1%0603"))
    )
    (comp (ref "R108")
      (value "10K 1%")
      (footprint "eagle-import:0805")
      (fields (field (name "LCSC_PART") "C17414"))
      (libsource (lib "eagle-import") (part "10K-1%0805"))
    )
    (comp (ref "R123")
      (value "1K 1%")
      (footprint "eagle-import:0402")
      (fields (field (name "LCSC_PART") "C11702"))
      (libsource (lib "eagle-import") (part "1K-1%0402"))
    )
    (comp (ref "R148")
      (value "2.4K 1%")
      (footprint "eagle-import:0402")
      (fields (field (name "LCSC_PART") "C25882"))
      (libsource (lib "eagle-import") (part "2.4K-1%0402"))
    )
    (comp (ref "R150")
      (value "8.2K 1%")
      (footprint "eagle-import:0402")
      (fields (field (name "LCSC_PART") "C25924"))
      (libsource (lib "eagle-import") (part "8.2K-1%0402"))
    )
    (comp (ref "R161")
      (value "DNI")
      (footprint "eagle-import:0402")
      (libsource (lib "eagle-import") (part "R0402"))
    )
    (comp (ref "R162")
      (value "10K 1%")
      (footprint "eagle-import:0402")
      (fields (field (name "LCSC_PART") "C25744"))
      (libsource (lib "eagle-import") (part "10K-1%0402"))
    )
    (comp (ref "SW") (value "TP") (footprint "eagle-import:TP") (libsource (lib "eagle-import") (part "TP")))
    (comp (ref "SW3") (value "TP") (footprint "eagle-import:TP") (libsource (lib "eagle-import") (part "TP")))
    (comp (ref "VNI1")
      (value "TP")
      (footprint "eagle-import:TP")
      (libsource (lib "eagle-import") (part "TP"))
    )
    (comp (ref "VNI2")
      (value "TP")
      (footprint "eagle-import:TP")
      (libsource (lib "eagle-import") (part "TP"))
    )
    (comp (ref "AVDD")
      (value "TP")
      (footprint "eagle-import:TP")
      (libsource (lib "eagle-import") (part "TP"))
    )
    (comp (ref "C60")
      (value "1uF 25V")
      (footprint "eagle-import:0402")
      (fields (field (name "LCSC_PART") "C52923"))
      (libsource (lib "eagle-import") (part "1UF-25V0402"))
    )
    (comp (ref "C61")
      (value "100nF 25V")
      (footprint "eagle-import:0201")
      (fields (field (name "LCSC_PART") "C76939"))
      (libsource (lib "eagle-import") (part "100NF-25V-0201"))
    )
    (comp (ref "C62")
      (value "100nF 25V")
      (footprint "eagle-import:0201")
      (fields (field (name "LCSC_PART") "C76939"))
      (libsource (lib "eagle-import") (part "100NF-25V-0201"))
    )
    (comp (ref "C63")
      (value "100nF 25V")
      (footprint "eagle-import:0201")
      (fields (field (name "LCSC_PART") "C76939"))
      (libsource (lib "eagle-import") (part "100NF-25V-0201"))
    )
    (comp (ref "C65")
      (value "10uF 50V")
      (footprint "eagle-import:0805")
      (fields (field (name "LCSC_PART") "C440198"))
      (libsource (lib "eagle-import") (part "10UF-50V-0805"))
    )
    (comp (ref "C66")
      (value "100nF 25V")
      (footprint "eagle-import:0402")
      (fields (field (name "LCSC_PART") "C56392"))
      (libsource (lib "eagle-import") (part "100NF-25V-0402"))
    )
    (comp (ref "C78")
      (value "4.7nF 50V")
      (footprint "eagle-import:0402")
      (fields (field (name "LCSC_PART") "C1538"))
      (libsource (lib "eagle-import") (part "4.7NF-50V0402"))
    )
    (comp (ref "C97")
      (value "10uF 50V")
      (footprint "eagle-import:0805")
      (fields (field (name "LCSC_PART") "C440198"))
      (libsource (lib "eagle-import") (part "10UF-50V-0805"))
    )
    (comp (ref "C98")
      (value "100nF 25V")
      (footprint "eagle-import:0201")
      (fields (field (name "LCSC_PART") "C76939"))
      (libsource (lib "eagle-import") (part "100NF-25V-0201"))
    )
    (comp (ref "C99")
      (value "10uF 50V")
      (footprint "eagle-import:0805")
      (fields (field (name "LCSC_PART") "C440198"))
      (libsource (lib "eagle-import") (part "10UF-50V-0805"))
    )
    (comp (ref "C100")
      (value "100nF 25V")
      (footprint "eagle-import:0201")
      (fields (field (name "LCSC_PART") "C76939"))
      (libsource (lib "eagle-import") (part "100NF-25V-0201"))
    )
    (comp (ref "C102")
      (value "1uF 16V")
      (footprint "eagle-import:0201")
      (fields (field (name "LCSC_PART") "C307385"))
      (libsource (lib "eagle-import") (part "1UF-16V0201"))
    )
    (comp (ref "C104")
      (value "1uF 25V")
      (footprint "eagle-import:0402")
      (fields (field (name "LCSC_PART") "C52923"))
      (libsource (lib "eagle-import") (part "1UF-25V0402"))
    )
    (comp (ref "D15")
      (value "SS12")
      (footprint "eagle-import:SMA_DO-214AC")
      (fields (field (name "LCSC_PART") "C727049"))
      (libsource (lib "eagle-import") (part "SS12"))
    )
    (comp (ref "DSP")
      (value "AFC11-S20ICC-00")
      (footprint "eagle-import:FPC20")
      (fields (field (name "LCSC_PART") "C11073"))
      (libsource (lib "eagle-import") (part "AFC11-S20ICC-00"))
    )
    (comp (ref "ESD1")
      (value "SP0503BAHTG")
      (footprint "eagle-import:SOT143")
      (fields (field (name "LCSC_PART") "C3040626"))
      (libsource (lib "eagle-import") (part "SP0503BAHT"))
    )
    (comp (ref "IC17")
      (value "MCP6001RT-I/OT")
      (footprint "eagle-import:SOT23-5")
      (fields (field (name "LCSC_PART") "C154973"))
      (libsource (lib "eagle-import") (part "MCP6001RT"))
    )
    (comp (ref "IC21")
      (value "MIC5504-3.3YM5")
      (footprint "eagle-import:SOT23-5")
      (fields (field (name "LCSC_PART") "C41348078"))
      (libsource (lib "eagle-import") (part "MIC5504-3.3YM5-TR"))
    )
    (comp (ref "PWR")
      (value "Green")
      (footprint "eagle-import:LED-0603")
      (fields (field (name "LCSC_PART") "C965804"))
      (libsource (lib "eagle-import") (part "LED-GREENLED-0603"))
    )
    (comp (ref "R109")
      (value "4.7K 1%")
      (footprint "eagle-import:0201")
      (fields (field (name "LCSC_PART") "C270346"))
      (libsource (lib "eagle-import") (part "4.7K-1%0201"))
    )
    (comp (ref "R121")
      (value "2.2K 1%")
      (footprint "eagle-import:0201")
      (fields (field (name "LCSC_PART") "C473508"))
      (libsource (lib "eagle-import") (part "2.2K-1%0201"))
    )
    (comp (ref "R124")
      (value "5.1K 1%")
      (footprint "eagle-import:0201")
      (fields (field (name "LCSC_PART") "C274341"))
      (libsource (lib "eagle-import") (part "5.1K-1%0201"))
    )
    (comp (ref "R125")
      (value "5.1K 1%")
      (footprint "eagle-import:0201")
      (fields (field (name "LCSC_PART") "C274341"))
      (libsource (lib "eagle-import") (part "5.1K-1%0201"))
    )
    (comp (ref "R126")
      (value "10K 1%")
      (footprint "eagle-import:0201")
      (fields (field (name "LCSC_PART") "C473048"))
      (libsource (lib "eagle-import") (part "10K-1%0201"))
    )
    (comp (ref "R127")
      (value "10K 1%")
      (footprint "eagle-import:0201")
      (fields (field (name "LCSC_PART") "C473048"))
      (libsource (lib "eagle-import") (part "10K-1%0201"))
    )
    (comp (ref "R131")
      (value "1M 1%")
      (footprint "eagle-import:0402")
      (fields (field (name "LCSC_PART") "C26083"))
      (libsource (lib "eagle-import") (part "1M-1%0402"))
    )
    (comp (ref "R147")
      (value "10K 1%")
      (footprint "eagle-import:0402")
      (fields (field (name "LCSC_PART") "C25744"))
      (libsource (lib "eagle-import") (part "10K-1%0402"))
    )
    (comp (ref "R149")
      (value "3.3K 1%")
      (footprint "eagle-import:_0603X4-1206")
      (fields (field (name "LCSC_PART") "C1734380"))
      (libsource (lib "eagle-import") (part "3.3K-1%_ARRAY0603X4-1206"))
    )
    (comp (ref "R151")
      (value "1K 1%")
      (footprint "eagle-import:0402")
      (fields (field (name "LCSC_PART") "C11702"))
      (libsource (lib "eagle-import") (part "1K-1%0402"))
    )
    (comp (ref "R152")
      (value "10R 1%")
      (footprint "eagle-import:0201")
      (fields (field (name "LCSC_PART") "C270817"))
      (libsource (lib "eagle-import") (part "10R-1%0201"))
    )
    (comp (ref "REF1")
      (value "LM4040B30FTA")
      (footprint "eagle-import:SOT23")
      (fields (field (name "LCSC_PART") "C460604"))
      (libsource (lib "eagle-import") (part "LM4040BXX"))
    )
    (comp (ref "USB1")
      (value "USB-TYPE-C-018")
      (footprint "eagle-import:USB-C")
      (fields (field (name "LCSC_PART") "C2927038"))
      (libsource (lib "eagle-import") (part "USB_C-THT"))
    )
    (comp (ref "VBUS")
      (value "TP")
      (footprint "eagle-import:TP")
      (libsource (lib "eagle-import") (part "TP"))
    )
    (comp (ref "VREF")
      (value "TP")
      (footprint "eagle-import:TP")
      (libsource (lib "eagle-import") (part "TP"))
    )
    (comp (ref "C79")
      (value "100nF 25V")
      (footprint "eagle-import:0402")
      (fields (field (name "LCSC_PART") "C56392"))
      (libsource (lib "eagle-import") (part "100NF-25V-0402"))
    )
    (comp (ref "C80")
      (value "22nF 50V")
      (footprint "eagle-import:0402")
      (fields (field (name "LCSC_PART") "C1532"))
      (libsource (lib "eagle-import") (part "22NF-50V0402"))
    )
    (comp (ref "C81")
      (value "6.8nF 50V")
      (footprint "eagle-import:0201")
      (fields (field (name "LCSC_PART") "C285015"))
      (libsource (lib "eagle-import") (part "6.8NF-50V0201"))
    )
    (comp (ref "C82")
      (value "6.8nF 50V")
      (footprint "eagle-import:0201")
      (fields (field (name "LCSC_PART") "C285015"))
      (libsource (lib "eagle-import") (part "6.8NF-50V0201"))
    )
    (comp (ref "C83")
      (value "C1206C102KGRACTM")
      (footprint "eagle-import:C1206")
      (libsource (lib "eagle-import") (part "C-1206"))
    )
    (comp (ref "C84")
      (value "100nF 25V")
      (footprint "eagle-import:0201")
      (fields (field (name "LCSC_PART") "C76939"))
      (libsource (lib "eagle-import") (part "100NF-25V-0201"))
    )
    (comp (ref "C85")
      (value "4.7uF 25V")
      (footprint "eagle-import:0402")
      (fields (field (name "LCSC_PART") "C22367824"))
      (libsource (lib "eagle-import") (part "4.7UF-25V0402"))
    )
    (comp (ref "C86")
      (value "18pF 50V")
      (footprint "eagle-import:0201")
      (fields (field (name "LCSC_PART") "C62164"))
      (libsource (lib "eagle-import") (part "18PF-50V-0201"))
    )
    (comp (ref "C87")
      (value "18pF 50V")
      (footprint "eagle-import:0201")
      (fields (field (name "LCSC_PART") "C62164"))
      (libsource (lib "eagle-import") (part "18PF-50V-0201"))
    )
    (comp (ref "C88")
      (value "100nF 25V")
      (footprint "eagle-import:0201")
      (fields (field (name "LCSC_PART") "C76939"))
      (libsource (lib "eagle-import") (part "100NF-25V-0201"))
    )
    (comp (ref "C89")
      (value "100nF 25V")
      (footprint "eagle-import:0201")
      (fields (field (name "LCSC_PART") "C76939"))
      (libsource (lib "eagle-import") (part "100NF-25V-0201"))
    )
    (comp (ref "C90")
      (value "100nF 25V")
      (footprint "eagle-import:0201")
      (fields (field (name "LCSC_PART") "C76939"))
      (libsource (lib "eagle-import") (part "100NF-25V-0201"))
    )
    (comp (ref "C91")
      (value "100nF 25V")
      (footprint "eagle-import:0201")
      (fields (field (name "LCSC_PART") "C76939"))
      (libsource (lib "eagle-import") (part "100NF-25V-0201"))
    )
    (comp (ref "C92")
      (value "100nF 25V")
      (footprint "eagle-import:0201")
      (fields (field (name "LCSC_PART") "C76939"))
      (libsource (lib "eagle-import") (part "100NF-25V-0201"))
    )
    (comp (ref "C93")
      (value "100nF 25V")
      (footprint "eagle-import:0201")
      (fields (field (name "LCSC_PART") "C76939"))
      (libsource (lib "eagle-import") (part "100NF-25V-0201"))
    )
    (comp (ref "C94")
      (value "100nF 25V")
      (footprint "eagle-import:0201")
      (fields (field (name "LCSC_PART") "C76939"))
      (libsource (lib "eagle-import") (part "100NF-25V-0201"))
    )
    (comp (ref "C95")
      (value "100nF 25V")
      (footprint "eagle-import:0201")
      (fields (field (name "LCSC_PART") "C76939"))
      (libsource (lib "eagle-import") (part "100NF-25V-0201"))
    )
    (comp (ref "C96")
      (value "100nF 25V")
      (footprint "eagle-import:0201")
      (fields (field (name "LCSC_PART") "C76939"))
      (libsource (lib "eagle-import") (part "100NF-25V-0201"))
    )
    (comp (ref "ETH1")
      (value "J1B1211CCD")
      (footprint "eagle-import:J1B1211CCD")
      (fields (field (name "LCSC_PART") "C910371"))
      (libsource (lib "eagle-import") (part "J1B1211CCD"))
    )
    (comp (ref "IC20")
      (value "W5500")
      (footprint "eagle-import:LQFP48")
      (fields (field (name "LCSC_PART") "C32843"))
      (libsource (lib "eagle-import") (part "W5500"))
    )
    (comp (ref "L4")
      (value "BLM18EG221TN1D")
      (footprint "eagle-import:0603")
      (fields (field (name "LCSC_PART") "C113025"))
      (libsource (lib "eagle-import") (part "BLM18EG221TN1D"))
    )
    (comp (ref "R110")
      (value "1M 1%")
      (footprint "eagle-import:1206")
      (fields (field (name "LCSC_PART") "C17927"))
      (libsource (lib "eagle-import") (part "1M-1%1206"))
    )
    (comp (ref "R133")
      (value "3.3R 1%")
      (footprint "eagle-import:0201")
      (fields (field (name "LCSC_PART") "C158547"))
      (libsource (lib "eagle-import") (part "3.3R-1%0201"))
    )
    (comp (ref "R134")
      (value "3.3R 1%")
      (footprint "eagle-import:0201")
      (fields (field (name "LCSC_PART") "C158547"))
      (libsource (lib "eagle-import") (part "3.3R-1%0201"))
    )
    (comp (ref "R135")
      (value "3.3R 1%")
      (footprint "eagle-import:0201")
      (fields (field (name "LCSC_PART") "C158547"))
      (libsource (lib "eagle-import") (part "3.3R-1%0201"))
    )
    (comp (ref "R136")
      (value "3.3R 1%")
      (footprint "eagle-import:0201")
      (fields (field (name "LCSC_PART") "C158547"))
      (libsource (lib "eagle-import") (part "3.3R-1%0201"))
    )
    (comp (ref "R137")
      (value "49.9R 1%")
      (footprint "eagle-import:0201")
      (fields (field (name "LCSC_PART") "C155744"))
      (libsource (lib "eagle-import") (part "49.9R-1%0201"))
    )
    (comp (ref "R138")
      (value "49.9R 1%")
      (footprint "eagle-import:0201")
      (fields (field (name "LCSC_PART") "C155744"))
      (libsource (lib "eagle-import") (part "49.9R-1%0201"))
    )
    (comp (ref "R139")
      (value "49.9R 1%")
      (footprint "eagle-import:0201")
      (fields (field (name "LCSC_PART") "C155744"))
      (libsource (lib "eagle-import") (part "49.9R-1%0201"))
    )
    (comp (ref "R140")
      (value "49.9R 1%")
      (footprint "eagle-import:0201")
      (fields (field (name "LCSC_PART") "C155744"))
      (libsource (lib "eagle-import") (part "49.9R-1%0201"))
    )
    (comp (ref "R141")
      (value "470R 1%")
      (footprint "eagle-import:0402")
      (fields (field (name "LCSC_PART") "C25117"))
      (libsource (lib "eagle-import") (part "470R-1%0402"))
    )
    (comp (ref "R142")
      (value "470R 1%")
      (footprint "eagle-import:0402")
      (fields (field (name "LCSC_PART") "C25117"))
      (libsource (lib "eagle-import") (part "470R-1%0402"))
    )
    (comp (ref "R143")
      (value "12.4K 1%")
      (footprint "eagle-import:R0201")
      (libsource (lib "eagle-import") (part "R0201"))
    )
    (comp (ref "R144")
      (value "1M 1%")
      (footprint "eagle-import:0201")
      (fields (field (name "LCSC_PART") "C295786"))
      (libsource (lib "eagle-import") (part "1M-1%0201"))
    )
    (comp (ref "R145")
      (value "4.7K 1%")
      (footprint "eagle-import:0201")
      (fields (field (name "LCSC_PART") "C270346"))
      (libsource (lib "eagle-import") (part "4.7K-1%0201"))
    )
    (comp (ref "R146")
      (value "470R 1%")
      (footprint "eagle-import:0402")
      (fields (field (name "LCSC_PART") "C25117"))
      (libsource (lib "eagle-import") (part "470R-1%0402"))
    )
    (comp (ref "X2")
      (value "25MHz")
      (footprint "eagle-import:WE-XTAL_CFPX-180")
      (fields (field (name "LCSC_PART") "C9006"))
      (libsource (lib "eagle-import") (part "CRYSTAL-3225X322525MOB4SI"))
    )
    (comp (ref "BOOT")
      (value "B3U-1000P")
      (footprint "eagle-import:B3U-1000P")
      (fields (field (name "LCSC_PART") "C231329"))
      (libsource (lib "eagle-import") (part "B3U-1000P"))
    )
    (comp (ref "C58")
      (value "15pF 50V")
      (footprint "eagle-import:0201")
      (fields (field (name "LCSC_PART") "C22374851"))
      (libsource (lib "eagle-import") (part "15PF-50V0201"))
    )
    (comp (ref "C59")
      (value "15pF 50V")
      (footprint "eagle-import:0201")
      (fields (field (name "LCSC_PART") "C22374851"))
      (libsource (lib "eagle-import") (part "15PF-50V0201"))
    )
    (comp (ref "C64")
      (value "100nF 25V")
      (footprint "eagle-import:0201")
      (fields (field (name "LCSC_PART") "C76939"))
      (libsource (lib "eagle-import") (part "100NF-25V-0201"))
    )
    (comp (ref "C67")
      (value "100nF 25V")
      (footprint "eagle-import:0201")
      (fields (field (name "LCSC_PART") "C76939"))
      (libsource (lib "eagle-import") (part "100NF-25V-0201"))
    )
    (comp (ref "C68")
      (value "100nF 25V")
      (footprint "eagle-import:0201")
      (fields (field (name "LCSC_PART") "C76939"))
      (libsource (lib "eagle-import") (part "100NF-25V-0201"))
    )
    (comp (ref "C69")
      (value "100nF 25V")
      (footprint "eagle-import:0201")
      (fields (field (name "LCSC_PART") "C76939"))
      (libsource (lib "eagle-import") (part "100NF-25V-0201"))
    )
    (comp (ref "C70")
      (value "100nF 25V")
      (footprint "eagle-import:0201")
      (fields (field (name "LCSC_PART") "C76939"))
      (libsource (lib "eagle-import") (part "100NF-25V-0201"))
    )
    (comp (ref "C71")
      (value "100nF 25V")
      (footprint "eagle-import:0201")
      (fields (field (name "LCSC_PART") "C76939"))
      (libsource (lib "eagle-import") (part "100NF-25V-0201"))
    )
    (comp (ref "C72")
      (value "100nF 25V")
      (footprint "eagle-import:0201")
      (fields (field (name "LCSC_PART") "C76939"))
      (libsource (lib "eagle-import") (part "100NF-25V-0201"))
    )
    (comp (ref "C73")
      (value "100nF 25V")
      (footprint "eagle-import:0201")
      (fields (field (name "LCSC_PART") "C76939"))
      (libsource (lib "eagle-import") (part "100NF-25V-0201"))
    )
    (comp (ref "C74")
      (value "100nF 25V")
      (footprint "eagle-import:0201")
      (fields (field (name "LCSC_PART") "C76939"))
      (libsource (lib "eagle-import") (part "100NF-25V-0201"))
    )
    (comp (ref "C75")
      (value "100nF 25V")
      (footprint "eagle-import:0201")
      (fields (field (name "LCSC_PART") "C76939"))
      (libsource (lib "eagle-import") (part "100NF-25V-0201"))
    )
    (comp (ref "C76")
      (value "100nF 25V")
      (footprint "eagle-import:0201")
      (fields (field (name "LCSC_PART") "C76939"))
      (libsource (lib "eagle-import") (part "100NF-25V-0201"))
    )
    (comp (ref "C77")
      (value "100nF 25V")
      (footprint "eagle-import:0201")
      (fields (field (name "LCSC_PART") "C76939"))
      (libsource (lib "eagle-import") (part "100NF-25V-0201"))
    )
    (comp (ref "C101")
      (value "100nF 25V")
      (footprint "eagle-import:0201")
      (fields (field (name "LCSC_PART") "C76939"))
      (libsource (lib "eagle-import") (part "100NF-25V-0201"))
    )
    (comp (ref "DVDD")
      (value "TP")
      (footprint "eagle-import:TP")
      (libsource (lib "eagle-import") (part "TP"))
    )
    (comp (ref "GDGC")
      (value "CON-1X4")
      (footprint "eagle-import:1X4")
      (libsource (lib "eagle-import") (part "CON-1X4"))
    )
    (comp (ref "IC15")
      (value "RP2040")
      (footprint "eagle-import:QFN56")
      (fields (field (name "LCSC_PART") "C2040"))
      (libsource (lib "eagle-import") (part "RP2040"))
    )
    (comp (ref "IC18")
      (value "W25Q128JVPIQ")
      (footprint "eagle-import:SON127P600X500X75-8N")
      (fields (field (name "LCSC_PART") "C190862"))
      (libsource (lib "eagle-import") (part "W25Q128JVP"))
    )
    (comp (ref "IC19")
      (value "CAT24C256HU4IGT3")
      (footprint "eagle-import:SON50P300X200X50-9T130X140N")
      (fields (field (name "LCSC_PART") "C233771"))
      (libsource (lib "eagle-import") (part "CAT24C256-HU4"))
    )
    (comp (ref "IOVDD")
      (value "TP")
      (footprint "eagle-import:TP")
      (libsource (lib "eagle-import") (part "TP"))
    )
    (comp (ref "PROC")
      (value "Green")
      (footprint "eagle-import:LED-0603")
      (fields (field (name "LCSC_PART") "C965804"))
      (libsource (lib "eagle-import") (part "LED-GREENLED-0603"))
    )
    (comp (ref "R15")
      (value "27R 1%")
      (footprint "eagle-import:0201")
      (fields (field (name "LCSC_PART") "C473051"))
      (libsource (lib "eagle-import") (part "27R-1%0201"))
    )
    (comp (ref "R16")
      (value "1K 1%")
      (footprint "eagle-import:0201")
      (fields (field (name "LCSC_PART") "C270365"))
      (libsource (lib "eagle-import") (part "1K-1%0201"))
    )
    (comp (ref "R111")
      (value "DNI")
      (footprint "eagle-import:R0201")
      (libsource (lib "eagle-import") (part "R0201"))
    )
    (comp (ref "R112")
      (value "1K 1%")
      (footprint "eagle-import:0402")
      (fields (field (name "LCSC_PART") "C11702"))
      (libsource (lib "eagle-import") (part "1K-1%0402"))
    )
    (comp (ref "R128")
      (value "NC")
      (footprint "eagle-import:R0201")
      (libsource (lib "eagle-import") (part "R0201"))
    )
    (comp (ref "R129")
      (value "4.7K 1%")
      (footprint "eagle-import:0201")
      (fields (field (name "LCSC_PART") "C270346"))
      (libsource (lib "eagle-import") (part "4.7K-1%0201"))
    )
    (comp (ref "R130")
      (value "3.3K 1%")
      (footprint "eagle-import:_0603X4-1206")
      (fields (field (name "LCSC_PART") "C1734380"))
      (libsource (lib "eagle-import") (part "3.3K-1%_ARRAY0603X4-1206"))
    )
    (comp (ref "R132")
      (value "10K 1%")
      (footprint "eagle-import:0402")
      (fields (field (name "LCSC_PART") "C25744"))
      (libsource (lib "eagle-import") (part "10K-1%0402"))
    )
    (comp (ref "R160")
      (value "27R 1%")
      (footprint "eagle-import:0201")
      (fields (field (name "LCSC_PART") "C473051"))
      (libsource (lib "eagle-import") (part "27R-1%0201"))
    )
    (comp (ref "R163")
      (value "1K 1%")
      (footprint "eagle-import:0402")
      (fields (field (name "LCSC_PART") "C11702"))
      (libsource (lib "eagle-import") (part "1K-1%0402"))
    )
    (comp (ref "RESET")
      (value "B3U-1000P")
      (footprint "eagle-import:B3U-1000P")
      (fields (field (name "LCSC_PART") "C231329"))
      (libsource (lib "eagle-import") (part "B3U-1000P"))
    )
    (comp (ref "RGTG")
      (value "CON-1X4")
      (footprint "eagle-import:1X4")
      (libsource (lib "eagle-import") (part "CON-1X4"))
    )
    (comp (ref "X1")
      (value "12MHz")
      (footprint "eagle-import:WE-XTAL_CFPX-180")
      (fields (field (name "LCSC_PART") "C9002"))
      (libsource (lib "eagle-import") (part "CRYSTAL-3225X322512MSB4SI"))
    )
    (comp (ref "C106")
      (value "1nF 25V")
      (footprint "eagle-import:0201")
      (fields (field (name "LCSC_PART") "C7694325V"))
      (libsource (lib "eagle-import") (part "1NF-25V-0201"))
    )
    (comp (ref "C107")
      (value "1nF 25V")
      (footprint "eagle-import:0201")
      (fields (field (name "LCSC_PART") "C7694325V"))
      (libsource (lib "eagle-import") (part "1NF-25V-0201"))
    )
    (comp (ref "C108")
      (value "1nF 25V")
      (footprint "eagle-import:0201")
      (fields (field (name "LCSC_PART") "C7694325V"))
      (libsource (lib "eagle-import") (part "1NF-25V-0201"))
    )
    (comp (ref "C109")
      (value "1nF 25V")
      (footprint "eagle-import:0201")
      (fields (field (name "LCSC_PART") "C7694325V"))
      (libsource (lib "eagle-import") (part "1NF-25V-0201"))
    )
    (comp (ref "C110")
      (value "1nF 25V")
      (footprint "eagle-import:0201")
      (fields (field (name "LCSC_PART") "C7694325V"))
      (libsource (lib "eagle-import") (part "1NF-25V-0201"))
    )
    (comp (ref "C111")
      (value "1nF 25V")
      (footprint "eagle-import:0201")
      (fields (field (name "LCSC_PART") "C7694325V"))
      (libsource (lib "eagle-import") (part "1NF-25V-0201"))
    )
    (comp (ref "C112")
      (value "1nF 25V")
      (footprint "eagle-import:0201")
      (fields (field (name "LCSC_PART") "C7694325V"))
      (libsource (lib "eagle-import") (part "1NF-25V-0201"))
    )
    (comp (ref "C113")
      (value "1nF 25V")
      (footprint "eagle-import:0201")
      (fields (field (name "LCSC_PART") "C7694325V"))
      (libsource (lib "eagle-import") (part "1NF-25V-0201"))
    )
    (comp (ref "OPT1")
      (value "ACPL-247-500E")
      (footprint "eagle-import:SO16")
      (fields (field (name "LCSC_PART") "C188681"))
      (libsource (lib "eagle-import") (part "ACPL-2471"))
    )
    (comp (ref "OPT2")
      (value "ACPL-247-500E")
      (footprint "eagle-import:SO16")
      (fields (field (name "LCSC_PART") "C188681"))
      (libsource (lib "eagle-import") (part "ACPL-2471"))
    )
    (comp (ref "R59")
      (value "1K 1%")
      (footprint "eagle-import:0201")
      (fields (field (name "LCSC_PART") "C270365"))
      (libsource (lib "eagle-import") (part "1K-1%0201"))
    )
    (comp (ref "R63")
      (value "1K 1%")
      (footprint "eagle-import:_0603X4-1206")
      (fields (field (name "LCSC_PART") "C110021"))
      (libsource (lib "eagle-import") (part "1K-1%_ARRAY0603X4-1206"))
    )
    (comp (ref "R64")
      (value "1K 1%")
      (footprint "eagle-import:_0603X4-1206")
      (fields (field (name "LCSC_PART") "C110021"))
      (libsource (lib "eagle-import") (part "1K-1%_ARRAY0603X4-1206"))
    )
    (comp (ref "R89")
      (value "10K 1%")
      (footprint "eagle-import:_0603X4-1206")
      (fields (field (name "LCSC_PART") "C110924"))
      (libsource (lib "eagle-import") (part "10K-1%_ARRAY0603X4-1206"))
    )
    (comp (ref "R90")
      (value "10K 1%")
      (footprint "eagle-import:_0603X4-1206")
      (fields (field (name "LCSC_PART") "C110924"))
      (libsource (lib "eagle-import") (part "10K-1%_ARRAY0603X4-1206"))
    )
    (comp (ref "R153")
      (value "1K 1%")
      (footprint "eagle-import:0201")
      (fields (field (name "LCSC_PART") "C270365"))
      (libsource (lib "eagle-import") (part "1K-1%0201"))
    )
    (comp (ref "R154")
      (value "1K 1%")
      (footprint "eagle-import:0201")
      (fields (field (name "LCSC_PART") "C270365"))
      (libsource (lib "eagle-import") (part "1K-1%0201"))
    )
    (comp (ref "R155")
      (value "1K 1%")
      (footprint "eagle-import:0201")
      (fields (field (name "LCSC_PART") "C270365"))
      (libsource (lib "eagle-import") (part "1K-1%0201"))
    )
    (comp (ref "R156")
      (value "1K 1%")
      (footprint "eagle-import:0201")
      (fields (field (name "LCSC_PART") "C270365"))
      (libsource (lib "eagle-import") (part "1K-1%0201"))
    )
    (comp (ref "R157")
      (value "1K 1%")
      (footprint "eagle-import:0201")
      (fields (field (name "LCSC_PART") "C270365"))
      (libsource (lib "eagle-import") (part "1K-1%0201"))
    )
    (comp (ref "R158")
      (value "1K 1%")
      (footprint "eagle-import:0201")
      (fields (field (name "LCSC_PART") "C270365"))
      (libsource (lib "eagle-import") (part "1K-1%0201"))
    )
    (comp (ref "R159")
      (value "1K 1%")
      (footprint "eagle-import:0201")
      (fields (field (name "LCSC_PART") "C270365"))
      (libsource (lib "eagle-import") (part "1K-1%0201"))
    )
    (comp (ref "C24")
      (value "33nF 50V")
      (footprint "eagle-import:0805")
      (fields (field (name "LCSC_PART") "C107150"))
      (libsource (lib "eagle-import") (part "33NF-50V0805"))
    )
    (comp (ref "C25")
      (value "33nF 50V")
      (footprint "eagle-import:0805")
      (fields (field (name "LCSC_PART") "C107150"))
      (libsource (lib "eagle-import") (part "33NF-50V0805"))
    )
    (comp (ref "C26")
      (value "33nF 50V")
      (footprint "eagle-import:0805")
      (fields (field (name "LCSC_PART") "C107150"))
      (libsource (lib "eagle-import") (part "33NF-50V0805"))
    )
    (comp (ref "C27")
      (value "33nF 50V")
      (footprint "eagle-import:0805")
      (fields (field (name "LCSC_PART") "C107150"))
      (libsource (lib "eagle-import") (part "33NF-50V0805"))
    )
    (comp (ref "C28")
      (value "33nF 50V")
      (footprint "eagle-import:0805")
      (fields (field (name "LCSC_PART") "C107150"))
      (libsource (lib "eagle-import") (part "33NF-50V0805"))
    )
    (comp (ref "C29")
      (value "33nF 50V")
      (footprint "eagle-import:0805")
      (fields (field (name "LCSC_PART") "C107150"))
      (libsource (lib "eagle-import") (part "33NF-50V0805"))
    )
    (comp (ref "C30")
      (value "33nF 50V")
      (footprint "eagle-import:0805")
      (fields (field (name "LCSC_PART") "C107150"))
      (libsource (lib "eagle-import") (part "33NF-50V0805"))
    )
    (comp (ref "C31")
      (value "33nF 50V")
      (footprint "eagle-import:0805")
      (fields (field (name "LCSC_PART") "C107150"))
      (libsource (lib "eagle-import") (part "33NF-50V0805"))
    )
    (comp (ref "C32")
      (value "33nF 50V")
      (footprint "eagle-import:0805")
      (fields (field (name "LCSC_PART") "C107150"))
      (libsource (lib "eagle-import") (part "33NF-50V0805"))
    )
    (comp (ref "C36")
      (value "33nF 50V")
      (footprint "eagle-import:0805")
      (fields (field (name "LCSC_PART") "C107150"))
      (libsource (lib "eagle-import") (part "33NF-50V0805"))
    )
    (comp (ref "C37")
      (value "33nF 50V")
      (footprint "eagle-import:0805")
      (fields (field (name "LCSC_PART") "C107150"))
      (libsource (lib "eagle-import") (part "33NF-50V0805"))
    )
    (comp (ref "C38")
      (value "33nF 50V")
      (footprint "eagle-import:0805")
      (fields (field (name "LCSC_PART") "C107150"))
      (libsource (lib "eagle-import") (part "33NF-50V0805"))
    )
    (comp (ref "C39")
      (value "33nF 50V")
      (footprint "eagle-import:0805")
      (fields (field (name "LCSC_PART") "C107150"))
      (libsource (lib "eagle-import") (part "33NF-50V0805"))
    )
    (comp (ref "C40")
      (value "33nF 50V")
      (footprint "eagle-import:0805")
      (fields (field (name "LCSC_PART") "C107150"))
      (libsource (lib "eagle-import") (part "33NF-50V0805"))
    )
    (comp (ref "C41")
      (value "33nF 50V")
      (footprint "eagle-import:0805")
      (fields (field (name "LCSC_PART") "C107150"))
      (libsource (lib "eagle-import") (part "33NF-50V0805"))
    )
    (comp (ref "C42")
      (value "33nF 50V")
      (footprint "eagle-import:0805")
      (fields (field (name "LCSC_PART") "C107150"))
      (libsource (lib "eagle-import") (part "33NF-50V0805"))
    )
    (comp (ref "C43")
      (value "33nF 50V")
      (footprint "eagle-import:0805")
      (fields (field (name "LCSC_PART") "C107150"))
      (libsource (lib "eagle-import") (part "33NF-50V0805"))
    )
    (comp (ref "C44")
      (value "33nF 50V")
      (footprint "eagle-import:0805")
      (fields (field (name "LCSC_PART") "C107150"))
      (libsource (lib "eagle-import") (part "33NF-50V0805"))
    )
    (comp (ref "C48")
      (value "33nF 50V")
      (footprint "eagle-import:0805")
      (fields (field (name "LCSC_PART") "C107150"))
      (libsource (lib "eagle-import") (part "33NF-50V0805"))
    )
    (comp (ref "C49")
      (value "33nF 50V")
      (footprint "eagle-import:0805")
      (fields (field (name "LCSC_PART") "C107150"))
      (libsource (lib "eagle-import") (part "33NF-50V0805"))
    )
    (comp (ref "C50")
      (value "33nF 50V")
      (footprint "eagle-import:0805")
      (fields (field (name "LCSC_PART") "C107150"))
      (libsource (lib "eagle-import") (part "33NF-50V0805"))
    )
    (comp (ref "C54")
      (value "33nF 50V")
      (footprint "eagle-import:0805")
      (fields (field (name "LCSC_PART") "C107150"))
      (libsource (lib "eagle-import") (part "33NF-50V0805"))
    )
    (comp (ref "C55")
      (value "33nF 50V")
      (footprint "eagle-import:0805")
      (fields (field (name "LCSC_PART") "C107150"))
      (libsource (lib "eagle-import") (part "33NF-50V0805"))
    )
    (comp (ref "C56")
      (value "33nF 50V")
      (footprint "eagle-import:0805")
      (fields (field (name "LCSC_PART") "C107150"))
      (libsource (lib "eagle-import") (part "33NF-50V0805"))
    )
    (comp (ref "IC6")
      (value "HLW8032")
      (footprint "eagle-import:SO8")
      (fields (field (name "LCSC_PART") "C128023"))
      (libsource (lib "eagle-import") (part "HLW8032"))
    )
    (comp (ref "IC7")
      (value "HLW8032")
      (footprint "eagle-import:SO8")
      (fields (field (name "LCSC_PART") "C128023"))
      (libsource (lib "eagle-import") (part "HLW8032"))
    )
    (comp (ref "IC8")
      (value "HLW8032")
      (footprint "eagle-import:SO8")
      (fields (field (name "LCSC_PART") "C128023"))
      (libsource (lib "eagle-import") (part "HLW8032"))
    )
    (comp (ref "IC10")
      (value "HLW8032")
      (footprint "eagle-import:SO8")
      (fields (field (name "LCSC_PART") "C128023"))
      (libsource (lib "eagle-import") (part "HLW8032"))
    )
    (comp (ref "IC11")
      (value "HLW8032")
      (footprint "eagle-import:SO8")
      (fields (field (name "LCSC_PART") "C128023"))
      (libsource (lib "eagle-import") (part "HLW8032"))
    )
    (comp (ref "IC12")
      (value "HLW8032")
      (footprint "eagle-import:SO8")
      (fields (field (name "LCSC_PART") "C128023"))
      (libsource (lib "eagle-import") (part "HLW8032"))
    )
    (comp (ref "IC14")
      (value "HLW8032")
      (footprint "eagle-import:SO8")
      (fields (field (name "LCSC_PART") "C128023"))
      (libsource (lib "eagle-import") (part "HLW8032"))
    )
    (comp (ref "IC16")
      (value "HLW8032")
      (footprint "eagle-import:SO8")
      (fields (field (name "LCSC_PART") "C128023"))
      (libsource (lib "eagle-import") (part "HLW8032"))
    )
    (comp (ref "L_OUT1")
      (value "MOUNT-PAD-ROUND2.8")
      (footprint "eagle-import:2,8-PAD")
      (libsource (lib "eagle-import") (part "MOUNT-PAD-ROUND2.8"))
    )
    (comp (ref "L_OUT2")
      (value "MOUNT-PAD-ROUND2.8")
      (footprint "eagle-import:2,8-PAD")
      (libsource (lib "eagle-import") (part "MOUNT-PAD-ROUND2.8"))
    )
    (comp (ref "L_OUT3")
      (value "MOUNT-PAD-ROUND2.8")
      (footprint "eagle-import:2,8-PAD")
      (libsource (lib "eagle-import") (part "MOUNT-PAD-ROUND2.8"))
    )
    (comp (ref "L_OUT4")
      (value "MOUNT-PAD-ROUND2.8")
      (footprint "eagle-import:2,8-PAD")
      (libsource (lib "eagle-import") (part "MOUNT-PAD-ROUND2.8"))
    )
    (comp (ref "L_OUT5")
      (value "MOUNT-PAD-ROUND2.8")
      (footprint "eagle-import:2,8-PAD")
      (libsource (lib "eagle-import") (part "MOUNT-PAD-ROUND2.8"))
    )
    (comp (ref "L_OUT6")
      (value "MOUNT-PAD-ROUND2.8")
      (footprint "eagle-import:2,8-PAD")
      (libsource (lib "eagle-import") (part "MOUNT-PAD-ROUND2.8"))
    )
    (comp (ref "L_OUT7")
      (value "MOUNT-PAD-ROUND2.8")
      (footprint "eagle-import:2,8-PAD")
      (libsource (lib "eagle-import") (part "MOUNT-PAD-ROUND2.8"))
    )
    (comp (ref "L_OUT8")
      (value "MOUNT-PAD-ROUND2.8")
      (footprint "eagle-import:2,8-PAD")
      (libsource (lib "eagle-import") (part "MOUNT-PAD-ROUND2.8"))
    )
    (comp (ref "N_OUT1")
      (value "MOUNT-PAD-ROUND2.8")
      (footprint "eagle-import:2,8-PAD")
      (libsource (lib "eagle-import") (part "MOUNT-PAD-ROUND2.8"))
    )
    (comp (ref "N_OUT2")
      (value "MOUNT-PAD-ROUND2.8")
      (footprint "eagle-import:2,8-PAD")
      (libsource (lib "eagle-import") (part "MOUNT-PAD-ROUND2.8"))
    )
    (comp (ref "N_OUT3")
      (value "MOUNT-PAD-ROUND2.8")
      (footprint "eagle-import:2,8-PAD")
      (libsource (lib "eagle-import") (part "MOUNT-PAD-ROUND2.8"))
    )
    (comp (ref "N_OUT4")
      (value "MOUNT-PAD-ROUND2.8")
      (footprint "eagle-import:2,8-PAD")
      (libsource (lib "eagle-import") (part "MOUNT-PAD-ROUND2.8"))
    )
    (comp (ref "N_OUT5")
      (value "MOUNT-PAD-ROUND2.8")
      (footprint "eagle-import:2,8-PAD")
      (libsource (lib "eagle-import") (part "MOUNT-PAD-ROUND2.8"))
    )
    (comp (ref "N_OUT6")
      (value "MOUNT-PAD-ROUND2.8")
      (footprint "eagle-import:2,8-PAD")
      (libsource (lib "eagle-import") (part "MOUNT-PAD-ROUND2.8"))
    )
    (comp (ref "N_OUT7")
      (value "MOUNT-PAD-ROUND2.8")
      (footprint "eagle-import:2,8-PAD")
      (libsource (lib "eagle-import") (part "MOUNT-PAD-ROUND2.8"))
    )
    (comp (ref "N_OUT8")
      (value "MOUNT-PAD-ROUND2.8")
      (footprint "eagle-import:2,8-PAD")
      (libsource (lib "eagle-import") (part "MOUNT-PAD-ROUND2.8"))
    )
    (comp (ref "R25")
      (value "0.002R 1%")
      (footprint "eagle-import:2512")
      (fields (field (name "LCSC_PART") "C728320"))
      (libsource (lib "eagle-import") (part "0.002R-1%2512"))
    )
    (comp (ref "R26")
      (value "0.002R 1%")
      (footprint "eagle-import:2512")
      (fields (field (name "LCSC_PART") "C728320"))
      (libsource (lib "eagle-import") (part "0.002R-1%2512"))
    )
    (comp (ref "R27")
      (value "0.002R 1%")
      (footprint "eagle-import:2512")
      (fields (field (name "LCSC_PART") "C728320"))
      (libsource (lib "eagle-import") (part "0.002R-1%2512"))
    )
    (comp (ref "R28")
      (value "0.002R 1%")
      (footprint "eagle-import:2512")
      (fields (field (name "LCSC_PART") "C728320"))
      (libsource (lib "eagle-import") (part "0.002R-1%2512"))
    )
    (comp (ref "R29")
      (value "0.002R 1%")
      (footprint "eagle-import:2512")
      (fields (field (name "LCSC_PART") "C728320"))
      (libsource (lib "eagle-import") (part "0.002R-1%2512"))
    )
    (comp (ref "R30")
      (value "0.002R 1%")
      (footprint "eagle-import:2512")
      (fields (field (name "LCSC_PART") "C728320"))
      (libsource (lib "eagle-import") (part "0.002R-1%2512"))
    )
    (comp (ref "R31")
      (value "0.002R 1%")
      (footprint "eagle-import:2512")
      (fields (field (name "LCSC_PART") "C728320"))
      (libsource (lib "eagle-import") (part "0.002R-1%2512"))
    )
    (comp (ref "R32")
      (value "0.002R 1%")
      (footprint "eagle-import:2512")
      (fields (field (name "LCSC_PART") "C728320"))
      (libsource (lib "eagle-import") (part "0.002R-1%2512"))
    )
    (comp (ref "R33")
      (value "1K 1%")
      (footprint "eagle-import:0805")
      (fields (field (name "LCSC_PART") "C17513"))
      (libsource (lib "eagle-import") (part "1K-1%0805"))
    )
    (comp (ref "R34")
      (value "1K 1%")
      (footprint "eagle-import:0805")
      (fields (field (name "LCSC_PART") "C17513"))
      (libsource (lib "eagle-import") (part "1K-1%0805"))
    )
    (comp (ref "R35")
      (value "0.002R 1%")
      (footprint "eagle-import:2512")
      (fields (field (name "LCSC_PART") "C728320"))
      (libsource (lib "eagle-import") (part "0.002R-1%2512"))
    )
    (comp (ref "R36")
      (value "470K 1%")
      (footprint "eagle-import:0805")
      (fields (field (name "LCSC_PART") "C17709"))
      (libsource (lib "eagle-import") (part "470K-1%0805"))
    )
    (comp (ref "R37")
      (value "470K 1%")
      (footprint "eagle-import:0805")
      (fields (field (name "LCSC_PART") "C17709"))
      (libsource (lib "eagle-import") (part "470K-1%0805"))
    )
    (comp (ref "R38")
      (value "470K 1%")
      (footprint "eagle-import:0805")
      (fields (field (name "LCSC_PART") "C17709"))
      (libsource (lib "eagle-import") (part "470K-1%0805"))
    )
    (comp (ref "R39")
      (value "470K 1%")
      (footprint "eagle-import:0805")
      (fields (field (name "LCSC_PART") "C17709"))
      (libsource (lib "eagle-import") (part "470K-1%0805"))
    )
    (comp (ref "R40")
      (value "1K 1%")
      (footprint "eagle-import:0805")
      (fields (field (name "LCSC_PART") "C17513"))
      (libsource (lib "eagle-import") (part "1K-1%0805"))
    )
    (comp (ref "R41")
      (value "1K 1%")
      (footprint "eagle-import:0805")
      (fields (field (name "LCSC_PART") "C17513"))
      (libsource (lib "eagle-import") (part "1K-1%0805"))
    )
    (comp (ref "R42")
      (value "1K 1%")
      (footprint "eagle-import:0805")
      (fields (field (name "LCSC_PART") "C17513"))
      (libsource (lib "eagle-import") (part "1K-1%0805"))
    )
    (comp (ref "R43")
      (value "0.002R 1%")
      (footprint "eagle-import:2512")
      (fields (field (name "LCSC_PART") "C728320"))
      (libsource (lib "eagle-import") (part "0.002R-1%2512"))
    )
    (comp (ref "R44")
      (value "470K 1%")
      (footprint "eagle-import:0805")
      (fields (field (name "LCSC_PART") "C17709"))
      (libsource (lib "eagle-import") (part "470K-1%0805"))
    )
    (comp (ref "R45")
      (value "470K 1%")
      (footprint "eagle-import:0805")
      (fields (field (name "LCSC_PART") "C17709"))
      (libsource (lib "eagle-import") (part "470K-1%0805"))
    )
    (comp (ref "R46")
      (value "470K 1%")
      (footprint "eagle-import:0805")
      (fields (field (name "LCSC_PART") "C17709"))
      (libsource (lib "eagle-import") (part "470K-1%0805"))
    )
    (comp (ref "R47")
      (value "470K 1%")
      (footprint "eagle-import:0805")
      (fields (field (name "LCSC_PART") "C17709"))
      (libsource (lib "eagle-import") (part "470K-1%0805"))
    )
    (comp (ref "R48")
      (value "1K 1%")
      (footprint "eagle-import:0805")
      (fields (field (name "LCSC_PART") "C17513"))
      (libsource (lib "eagle-import") (part "1K-1%0805"))
    )
    (comp (ref "R49")
      (value "1K 1%")
      (footprint "eagle-import:0805")
      (fields (field (name "LCSC_PART") "C17513"))
      (libsource (lib "eagle-import") (part "1K-1%0805"))
    )
    (comp (ref "R50")
      (value "1K 1%")
      (footprint "eagle-import:0805")
      (fields (field (name "LCSC_PART") "C17513"))
      (libsource (lib "eagle-import") (part "1K-1%0805"))
    )
    (comp (ref "R51")
      (value "0.002R 1%")
      (footprint "eagle-import:2512")
      (fields (field (name "LCSC_PART") "C728320"))
      (libsource (lib "eagle-import") (part "0.002R-1%2512"))
    )
    (comp (ref "R52")
      (value "470K 1%")
      (footprint "eagle-import:0805")
      (fields (field (name "LCSC_PART") "C17709"))
      (libsource (lib "eagle-import") (part "470K-1%0805"))
    )
    (comp (ref "R53")
      (value "470K 1%")
      (footprint "eagle-import:0805")
      (fields (field (name "LCSC_PART") "C17709"))
      (libsource (lib "eagle-import") (part "470K-1%0805"))
    )
    (comp (ref "R54")
      (value "470K 1%")
      (footprint "eagle-import:0805")
      (fields (field (name "LCSC_PART") "C17709"))
      (libsource (lib "eagle-import") (part "470K-1%0805"))
    )
    (comp (ref "R55")
      (value "470K 1%")
      (footprint "eagle-import:0805")
      (fields (field (name "LCSC_PART") "C17709"))
      (libsource (lib "eagle-import") (part "470K-1%0805"))
    )
    (comp (ref "R56")
      (value "1K 1%")
      (footprint "eagle-import:0805")
      (fields (field (name "LCSC_PART") "C17513"))
      (libsource (lib "eagle-import") (part "1K-1%0805"))
    )
    (comp (ref "R65")
      (value "1K 1%")
      (footprint "eagle-import:0805")
      (fields (field (name "LCSC_PART") "C17513"))
      (libsource (lib "eagle-import") (part "1K-1%0805"))
    )
    (comp (ref "R66")
      (value "1K 1%")
      (footprint "eagle-import:0805")
      (fields (field (name "LCSC_PART") "C17513"))
      (libsource (lib "eagle-import") (part "1K-1%0805"))
    )
    (comp (ref "R67")
      (value "0.002R 1%")
      (footprint "eagle-import:2512")
      (fields (field (name "LCSC_PART") "C728320"))
      (libsource (lib "eagle-import") (part "0.002R-1%2512"))
    )
    (comp (ref "R68")
      (value "470K 1%")
      (footprint "eagle-import:0805")
      (fields (field (name "LCSC_PART") "C17709"))
      (libsource (lib "eagle-import") (part "470K-1%0805"))
    )
    (comp (ref "R69")
      (value "470K 1%")
      (footprint "eagle-import:0805")
      (fields (field (name "LCSC_PART") "C17709"))
      (libsource (lib "eagle-import") (part "470K-1%0805"))
    )
    (comp (ref "R70")
      (value "470K 1%")
      (footprint "eagle-import:0805")
      (fields (field (name "LCSC_PART") "C17709"))
      (libsource (lib "eagle-import") (part "470K-1%0805"))
    )
    (comp (ref "R71")
      (value "470K 1%")
      (footprint "eagle-import:0805")
      (fields (field (name "LCSC_PART") "C17709"))
      (libsource (lib "eagle-import") (part "470K-1%0805"))
    )
    (comp (ref "R72")
      (value "1K 1%")
      (footprint "eagle-import:0805")
      (fields (field (name "LCSC_PART") "C17513"))
      (libsource (lib "eagle-import") (part "1K-1%0805"))
    )
    (comp (ref "R73")
      (value "1K 1%")
      (footprint "eagle-import:0805")
      (fields (field (name "LCSC_PART") "C17513"))
      (libsource (lib "eagle-import") (part "1K-1%0805"))
    )
    (comp (ref "R74")
      (value "1K 1%")
      (footprint "eagle-import:0805")
      (fields (field (name "LCSC_PART") "C17513"))
      (libsource (lib "eagle-import") (part "1K-1%0805"))
    )
    (comp (ref "R75")
      (value "0.002R 1%")
      (footprint "eagle-import:2512")
      (fields (field (name "LCSC_PART") "C728320"))
      (libsource (lib "eagle-import") (part "0.002R-1%2512"))
    )
    (comp (ref "R76")
      (value "470K 1%")
      (footprint "eagle-import:0805")
      (fields (field (name "LCSC_PART") "C17709"))
      (libsource (lib "eagle-import") (part "470K-1%0805"))
    )
    (comp (ref "R77")
      (value "470K 1%")
      (footprint "eagle-import:0805")
      (fields (field (name "LCSC_PART") "C17709"))
      (libsource (lib "eagle-import") (part "470K-1%0805"))
    )
    (comp (ref "R78")
      (value "470K 1%")
      (footprint "eagle-import:0805")
      (fields (field (name "LCSC_PART") "C17709"))
      (libsource (lib "eagle-import") (part "470K-1%0805"))
    )
    (comp (ref "R79")
      (value "470K 1%")
      (footprint "eagle-import:0805")
      (fields (field (name "LCSC_PART") "C17709"))
      (libsource (lib "eagle-import") (part "470K-1%0805"))
    )
    (comp (ref "R80")
      (value "1K 1%")
      (footprint "eagle-import:0805")
      (fields (field (name "LCSC_PART") "C17513"))
      (libsource (lib "eagle-import") (part "1K-1%0805"))
    )
    (comp (ref "R81")
      (value "1K 1%")
      (footprint "eagle-import:0805")
      (fields (field (name "LCSC_PART") "C17513"))
      (libsource (lib "eagle-import") (part "1K-1%0805"))
    )
    (comp (ref "R82")
      (value "1K 1%")
      (footprint "eagle-import:0805")
      (fields (field (name "LCSC_PART") "C17513"))
      (libsource (lib "eagle-import") (part "1K-1%0805"))
    )
    (comp (ref "R83")
      (value "0.002R 1%")
      (footprint "eagle-import:2512")
      (fields (field (name "LCSC_PART") "C728320"))
      (libsource (lib "eagle-import") (part "0.002R-1%2512"))
    )
    (comp (ref "R84")
      (value "470K 1%")
      (footprint "eagle-import:0805")
      (fields (field (name "LCSC_PART") "C17709"))
      (libsource (lib "eagle-import") (part "470K-1%0805"))
    )
    (comp (ref "R85")
      (value "470K 1%")
      (footprint "eagle-import:0805")
      (fields (field (name "LCSC_PART") "C17709"))
      (libsource (lib "eagle-import") (part "470K-1%0805"))
    )
    (comp (ref "R86")
      (value "470K 1%")
      (footprint "eagle-import:0805")
      (fields (field (name "LCSC_PART") "C17709"))
      (libsource (lib "eagle-import") (part "470K-1%0805"))
    )
    (comp (ref "R87")
      (value "470K 1%")
      (footprint "eagle-import:0805")
      (fields (field (name "LCSC_PART") "C17709"))
      (libsource (lib "eagle-import") (part "470K-1%0805"))
    )
    (comp (ref "R88")
      (value "1K 1%")
      (footprint "eagle-import:0805")
      (fields (field (name "LCSC_PART") "C17513"))
      (libsource (lib "eagle-import") (part "1K-1%0805"))
    )
    (comp (ref "R97")
      (value "1K 1%")
      (footprint "eagle-import:0805")
      (fields (field (name "LCSC_PART") "C17513"))
      (libsource (lib "eagle-import") (part "1K-1%0805"))
    )
    (comp (ref "R98")
      (value "1K 1%")
      (footprint "eagle-import:0805")
      (fields (field (name "LCSC_PART") "C17513"))
      (libsource (lib "eagle-import") (part "1K-1%0805"))
    )
    (comp (ref "R99")
      (value "0.002R 1%")
      (footprint "eagle-import:2512")
      (fields (field (name "LCSC_PART") "C728320"))
      (libsource (lib "eagle-import") (part "0.002R-1%2512"))
    )
    (comp (ref "R100")
      (value "470K 1%")
      (footprint "eagle-import:0805")
      (fields (field (name "LCSC_PART") "C17709"))
      (libsource (lib "eagle-import") (part "470K-1%0805"))
    )
    (comp (ref "R101")
      (value "470K 1%")
      (footprint "eagle-import:0805")
      (fields (field (name "LCSC_PART") "C17709"))
      (libsource (lib "eagle-import") (part "470K-1%0805"))
    )
    (comp (ref "R102")
      (value "470K 1%")
      (footprint "eagle-import:0805")
      (fields (field (name "LCSC_PART") "C17709"))
      (libsource (lib "eagle-import") (part "470K-1%0805"))
    )
    (comp (ref "R103")
      (value "470K 1%")
      (footprint "eagle-import:0805")
      (fields (field (name "LCSC_PART") "C17709"))
      (libsource (lib "eagle-import") (part "470K-1%0805"))
    )
    (comp (ref "R104")
      (value "1K 1%")
      (footprint "eagle-import:0805")
      (fields (field (name "LCSC_PART") "C17513"))
      (libsource (lib "eagle-import") (part "1K-1%0805"))
    )
    (comp (ref "R113")
      (value "1K 1%")
      (footprint "eagle-import:0805")
      (fields (field (name "LCSC_PART") "C17513"))
      (libsource (lib "eagle-import") (part "1K-1%0805"))
    )
    (comp (ref "R114")
      (value "1K 1%")
      (footprint "eagle-import:0805")
      (fields (field (name "LCSC_PART") "C17513"))
      (libsource (lib "eagle-import") (part "1K-1%0805"))
    )
    (comp (ref "R115")
      (value "0.002R 1%")
      (footprint "eagle-import:2512")
      (fields (field (name "LCSC_PART") "C728320"))
      (libsource (lib "eagle-import") (part "0.002R-1%2512"))
    )
    (comp (ref "R116")
      (value "470K 1%")
      (footprint "eagle-import:0805")
      (fields (field (name "LCSC_PART") "C17709"))
      (libsource (lib "eagle-import") (part "470K-1%0805"))
    )
    (comp (ref "R117")
      (value "470K 1%")
      (footprint "eagle-import:0805")
      (fields (field (name "LCSC_PART") "C17709"))
      (libsource (lib "eagle-import") (part "470K-1%0805"))
    )
    (comp (ref "R118")
      (value "470K 1%")
      (footprint "eagle-import:0805")
      (fields (field (name "LCSC_PART") "C17709"))
      (libsource (lib "eagle-import") (part "470K-1%0805"))
    )
    (comp (ref "R119")
      (value "470K 1%")
      (footprint "eagle-import:0805")
      (fields (field (name "LCSC_PART") "C17709"))
      (libsource (lib "eagle-import") (part "470K-1%0805"))
    )
    (comp (ref "R120")
      (value "1K 1%")
      (footprint "eagle-import:0805")
      (fields (field (name "LCSC_PART") "C17513"))
      (libsource (lib "eagle-import") (part "1K-1%0805"))
    )
  )
  (nets
    (net (code "1") (name "+1V1") (class "Default")
      (node (ref "C75") (pin "1") (pinfunction "1_1") (pintype "passive"))
      (node (ref "C76") (pin "1") (pinfunction "1_1") (pintype "passive"))
      (node (ref "C77") (pin "1") (pinfunction "1_1") (pintype "passive"))
      (node (ref "DVDD") (pin "TP") (pinfunction "P$1_TP") (pintype "bidirectional"))
      (node (ref "IC15") (pin "23") (pinfunction "DVDD_23") (pintype "bidirectional"))
      (node (ref "IC15") (pin "45") (pinfunction "VREG_VOUT_45") (pintype "bidirectional"))
      (node (ref "IC15") (pin "50") (pinfunction "DVDD_50") (pintype "bidirectional"))
    )
    (net (code "2") (name "+3V3") (class "Default")
      (node (ref "3VDC") (pin "TP") (pinfunction "P$1_TP") (pintype "bidirectional"))
      (node (ref "C103") (pin "1") (pinfunction "1_1") (pintype "passive"))
      (node (ref "C12") (pin "1") (pinfunction "1_1") (pintype "passive"))
      (node (ref "C15") (pin "1") (pinfunction "1_1") (pintype "passive"))
      (node (ref "C18") (pin "1") (pinfunction "1_1") (pintype "passive"))
      (node (ref "C19") (pin "1") (pinfunction "1_1") (pintype "passive"))
      (node (ref "C20") (pin "1") (pinfunction "1_1") (pintype "passive"))
      (node (ref "C33") (pin "1") (pinfunction "1_1") (pintype "passive"))
      (node (ref "C34") (pin "1") (pinfunction "1_1") (pintype "passive"))
      (node (ref "C88") (pin "1") (pinfunction "1_1") (pintype "passive"))
      (node (ref "C89") (pin "1") (pinfunction "1_1") (pintype "passive"))
      (node (ref "C90") (pin "1") (pinfunction "1_1") (pintype "passive"))
      (node (ref "DSP") (pin "1") (pinfunction "1_1") (pintype "bidirectional"))
      (node (ref "DSP") (pin "2") (pinfunction "2_2") (pintype "bidirectional"))
      (node (ref "ETH1") (pin "10") (pinfunction "GREEN+_10") (pintype "passive"))
      (node (ref "ETH1") (pin "12") (pinfunction "YELLOW+_12") (pintype "passive"))
      (node (ref "IC20") (pin "28") (pinfunction "VDD_28") (pintype "power_in"))
      (node (ref "IC20") (pin "43") (pinfunction "PMODE2_43") (pintype "input"))
      (node (ref "IC20") (pin "44") (pinfunction "PMODE1_44") (pintype "input"))
      (node (ref "IC20") (pin "45") (pinfunction "PMODE0_45") (pintype "input"))
      (node (ref "IC22") (pin "2") (pinfunction "V+_2") (pintype "power_in"))
      (node (ref "IC4") (pin "5") (pinfunction "VDD_5") (pintype "bidirectional"))
      (node (ref "IC9") (pin "16") (pinfunction "VCC_16") (pintype "power_in"))
      (node (ref "L2") (pin "2") (pinfunction "2_2") (pintype "passive"))
      (node (ref "L4") (pin "1") (pinfunction "1_1") (pintype "passive"))
      (node (ref "R123") (pin "1") (pinfunction "1_1") (pintype "passive"))
      (node (ref "R13") (pin "1") (pinfunction "1_1") (pintype "passive"))
      (node (ref "R145") (pin "2") (pinfunction "2_2") (pintype "passive"))
      (node (ref "R147") (pin "2") (pinfunction "2_2") (pintype "passive"))
      (node (ref "R149") (pin "A1") (pinfunction "1_A1") (pintype "passive"))
      (node (ref "R149") (pin "B1") (pinfunction "2_B1") (pintype "passive"))
      (node (ref "R149") (pin "C1") (pinfunction "3_C1") (pintype "passive"))
      (node (ref "R149") (pin "D1") (pinfunction "4_D1") (pintype "passive"))
      (node (ref "R89") (pin "A2") (pinfunction "8_A2") (pintype "passive"))
      (node (ref "R89") (pin "B2") (pinfunction "7_B2") (pintype "passive"))
      (node (ref "R89") (pin "C2") (pinfunction "6_C2") (pintype "passive"))
      (node (ref "R89") (pin "D2") (pinfunction "5_D2") (pintype "passive"))
      (node (ref "R90") (pin "A2") (pinfunction "8_A2") (pintype "passive"))
      (node (ref "R90") (pin "B2") (pinfunction "7_B2") (pintype "passive"))
      (node (ref "R90") (pin "C2") (pinfunction "6_C2") (pintype "passive"))
      (node (ref "R90") (pin "D2") (pinfunction "5_D2") (pintype "passive"))
    )
    (net (code "3") (name "+3V3_A") (class "Default")
      (node (ref "C91") (pin "1") (pinfunction "1_1") (pintype "passive"))
      (node (ref "C92") (pin "1") (pinfunction "1_1") (pintype "passive"))
      (node (ref "C93") (pin "1") (pinfunction "1_1") (pintype "passive"))
      (node (ref "C94") (pin "1") (pinfunction "1_1") (pintype "passive"))
      (node (ref "C95") (pin "1") (pinfunction "1_1") (pintype "passive"))
      (node (ref "C96") (pin "1") (pinfunction "1_1") (pintype "passive"))
      (node (ref "IC20") (pin "11") (pinfunction "AVDD_11") (pintype "power_in"))
      (node (ref "IC20") (pin "15") (pinfunction "AVDD_15") (pintype "power_in"))
      (node (ref "IC20") (pin "17") (pinfunction "AVDD_17") (pintype "power_in"))
      (node (ref "IC20") (pin "21") (pinfunction "AVDD_21") (pintype "power_in"))
      (node (ref "IC20") (pin "4") (pinfunction "AVDD_4") (pintype "power_in"))
      (node (ref "IC20") (pin "8") (pinfunction "AVDD_8") (pintype "power_in"))
      (node (ref "L4") (pin "2") (pinfunction "2_2") (pintype "passive"))
      (node (ref "R139") (pin "2") (pinfunction "2_2") (pintype "passive"))
      (node (ref "R140") (pin "2") (pinfunction "2_2") (pintype "passive"))
      (node (ref "R146") (pin "2") (pinfunction "2_2") (pintype "passive"))
    )
    (net (code "4") (name "+3V3_MCU") (class "Default")
      (node (ref "C100") (pin "1") (pinfunction "1_1") (pintype "passive"))
      (node (ref "C101") (pin "1") (pinfunction "1_1") (pintype "passive"))
      (node (ref "C104") (pin "1") (pinfunction "1_1") (pintype "passive"))
      (node (ref "C64") (pin "1") (pinfunction "1_1") (pintype "passive"))
      (node (ref "C67") (pin "1") (pinfunction "1_1") (pintype "passive"))
      (node (ref "C68") (pin "1") (pinfunction "1_1") (pintype "passive"))
      (node (ref "C69") (pin "1") (pinfunction "1_1") (pintype "passive"))
      (node (ref "C70") (pin "1") (pinfunction "1_1") (pintype "passive"))
      (node (ref "C71") (pin "1") (pinfunction "1_1") (pintype "passive"))
      (node (ref "C72") (pin "1") (pinfunction "1_1") (pintype "passive"))
      (node (ref "C73") (pin "1") (pinfunction "1_1") (pintype "passive"))
      (node (ref "C99") (pin "1") (pinfunction "1_1") (pintype "passive"))
      (node (ref "IC15") (pin "1") (pinfunction "IOVDD_1") (pintype "bidirectional"))
      (node (ref "IC15") (pin "10") (pinfunction "IOVDD_10") (pintype "bidirectional"))
      (node (ref "IC15") (pin "22") (pinfunction "IOVDD_22") (pintype "bidirectional"))
      (node (ref "IC15") (pin "33") (pinfunction "IOVDD_33") (pintype "bidirectional"))
      (node (ref "IC15") (pin "42") (pinfunction "IOVDD_42") (pintype "bidirectional"))
      (node (ref "IC15") (pin "44") (pinfunction "VREG_VIN_44") (pintype "bidirectional"))
      (node (ref "IC15") (pin "48") (pinfunction "USB_VDD_48") (pintype "bidirectional"))
      (node (ref "IC15") (pin "49") (pinfunction "IOVDD_49") (pintype "bidirectional"))
      (node (ref "IC18") (pin "8") (pinfunction "VCC_8") (pintype "power_in"))
      (node (ref "IC19") (pin "8") (pinfunction "VCC_8") (pintype "power_in"))
      (node (ref "IC21") (pin "5") (pinfunction "VOUT_5") (pintype "bidirectional"))
      (node (ref "IOVDD") (pin "TP") (pinfunction "P$1_TP") (pintype "bidirectional"))
      (node (ref "PWR") (pin "A") (pinfunction "A_A") (pintype "passive"))
      (node (ref "R109") (pin "2") (pinfunction "2_2") (pintype "passive"))
      (node (ref "R111") (pin "2") (pinfunction "2_2") (pintype "passive"))
      (node (ref "R128") (pin "2") (pinfunction "2_2") (pintype "passive"))
      (node (ref "R130") (pin "A2") (pinfunction "8_A2") (pintype "passive"))
      (node (ref "R130") (pin "B2") (pinfunction "7_B2") (pintype "passive"))
      (node (ref "R130") (pin "C2") (pinfunction "6_C2") (pintype "passive"))
      (node (ref "R130") (pin "D2") (pinfunction "5_D2") (pintype "passive"))
      (node (ref "R132") (pin "1") (pinfunction "1_1") (pintype "passive"))
      (node (ref "R152") (pin "1") (pinfunction "1_1") (pintype "passive"))
    )
    (net (code "5") (name "+5V") (class "Default")
      (node (ref "5VDC") (pin "TP") (pinfunction "P$1_TP") (pintype "bidirectional"))
      (node (ref "C11") (pin "1") (pinfunction "1_1") (pintype "passive"))
      (node (ref "C14") (pin "1") (pinfunction "1_1") (pintype "passive"))
      (node (ref "C17") (pin "1") (pinfunction "1_1") (pintype "passive"))
      (node (ref "D15") (pin "A") (pinfunction "A_A") (pintype "passive"))
      (node (ref "DSP") (pin "3") (pinfunction "3_3") (pintype "bidirectional"))
      (node (ref "DSP") (pin "4") (pinfunction "4_4") (pintype "bidirectional"))
      (node (ref "L1") (pin "2") (pinfunction "2_2") (pintype "passive"))
      (node (ref "R11") (pin "1") (pinfunction "1_1") (pintype "passive"))
      (node (ref "R148") (pin "1") (pinfunction "1_1") (pintype "passive"))
    )
    (net (code "6") (name "+5V_MEA") (class "Default")
      (node (ref "IC10") (pin "1") (pinfunction "VDD_1") (pintype "power_in"))
      (node (ref "IC11") (pin "1") (pinfunction "VDD_1") (pintype "power_in"))
      (node (ref "IC12") (pin "1") (pinfunction "VDD_1") (pintype "power_in"))
      (node (ref "IC14") (pin "1") (pinfunction "VDD_1") (pintype "power_in"))
      (node (ref "IC16") (pin "1") (pinfunction "VDD_1") (pintype "power_in"))
      (node (ref "IC6") (pin "1") (pinfunction "VDD_1") (pintype "power_in"))
      (node (ref "IC7") (pin "1") (pinfunction "VDD_1") (pintype "power_in"))
      (node (ref "IC8") (pin "1") (pinfunction "VDD_1") (pintype "power_in"))
      (node (ref "J2") (pin "2") (pinfunction "2_2") (pintype "passive"))
      (node (ref "J7") (pin "2") (pinfunction "2_2") (pintype "passive"))
      (node (ref "R63") (pin "A1") (pinfunction "1_A1") (pintype "passive"))
      (node (ref "R63") (pin "B1") (pinfunction "2_B1") (pintype "passive"))
      (node (ref "R63") (pin "C1") (pinfunction "3_C1") (pintype "passive"))
      (node (ref "R63") (pin "D1") (pinfunction "4_D1") (pintype "passive"))
      (node (ref "R64") (pin "A1") (pinfunction "1_A1") (pintype "passive"))
      (node (ref "R64") (pin "B1") (pinfunction "2_B1") (pintype "passive"))
      (node (ref "R64") (pin "C1") (pinfunction "3_C1") (pintype "passive"))
      (node (ref "R64") (pin "D1") (pinfunction "4_D1") (pintype "passive"))
    )
    (net (code "7") (name "+5V_MEA1") (class "Default")
      (node (ref "5V-NI1") (pin "TP") (pinfunction "P$1_TP") (pintype "bidirectional"))
      (node (ref "C23") (pin "1") (pinfunction "+_1") (pintype "passive"))
      (node (ref "C45") (pin "2") (pinfunction "2_2") (pintype "passive"))
      (node (ref "D9") (pin "A") (pinfunction "A_A") (pintype "passive"))
      (node (ref "J2") (pin "1") (pinfunction "1_1") (pintype "passive"))
      (node (ref "L3") (pin "2") (pinfunction "2_2") (pintype "passive"))
      (node (ref "R96") (pin "1") (pinfunction "1_1") (pintype "passive"))
    )
    (net (code "8") (name "+5V_MEA2") (class "Default")
      (node (ref "5V-NI2") (pin "TP") (pinfunction "P$1_TP") (pintype "bidirectional"))
      (node (ref "C53") (pin "1") (pinfunction "+_1") (pintype "passive"))
      (node (ref "C57") (pin "2") (pinfunction "2_2") (pintype "passive"))
      (node (ref "D13") (pin "A") (pinfunction "A_A") (pintype "passive"))
      (node (ref "J7") (pin "1") (pinfunction "1_1") (pintype "passive"))
      (node (ref "L5") (pin "2") (pinfunction "2_2") (pintype "passive"))
      (node (ref "R108") (pin "1") (pinfunction "1_1") (pintype "passive"))
    )
    (net (code "9") (name "+12V") (class "Default")
      (node (ref "C1") (pin "1") (pinfunction "1_1") (pintype "passive"))
      (node (ref "C2") (pin "1") (pinfunction "1_1") (pintype "passive"))
      (node (ref "C3") (pin "1") (pinfunction "1_1") (pintype "passive"))
      (node (ref "C4") (pin "1") (pinfunction "1_1") (pintype "passive"))
      (node (ref "D1") (pin "C") (pinfunction "C_C") (pintype "passive"))
      (node (ref "D2") (pin "C") (pinfunction "C_C") (pintype "passive"))
      (node (ref "D3") (pin "C") (pinfunction "C_C") (pintype "passive"))
      (node (ref "D4") (pin "C") (pinfunction "C_C") (pintype "passive"))
      (node (ref "D5") (pin "C") (pinfunction "C_C") (pintype "passive"))
      (node (ref "D6") (pin "C") (pinfunction "C_C") (pintype "passive"))
      (node (ref "D7") (pin "C") (pinfunction "C_C") (pintype "passive"))
      (node (ref "D8") (pin "C") (pinfunction "C_C") (pintype "passive"))
      (node (ref "IC1") (pin "2") (pinfunction "IN_2") (pintype "bidirectional"))
      (node (ref "IC2") (pin "2") (pinfunction "IN_2") (pintype "bidirectional"))
      (node (ref "IC3") (pin "10") (pinfunction "COM_10") (pintype "bidirectional"))
      (node (ref "J10") (pin "1") (pinfunction "1_1") (pintype "passive"))
      (node (ref "J8") (pin "1") (pinfunction "1_1") (pintype "passive"))
      (node (ref "J9") (pin "1") (pinfunction "1_1") (pintype "passive"))
      (node (ref "K1") (pin "8") (pinfunction "8_8") (pintype "passive"))
      (node (ref "K2") (pin "8") (pinfunction "8_8") (pintype "passive"))
      (node (ref "K3") (pin "8") (pinfunction "8_8") (pintype "passive"))
      (node (ref "K4") (pin "8") (pinfunction "8_8") (pintype "passive"))
      (node (ref "K5") (pin "8") (pinfunction "8_8") (pintype "passive"))
      (node (ref "K6") (pin "8") (pinfunction "8_8") (pintype "passive"))
      (node (ref "K7") (pin "8") (pinfunction "8_8") (pintype "passive"))
      (node (ref "K8") (pin "8") (pinfunction "8_8") (pintype "passive"))
      (node (ref "R150") (pin "1") (pinfunction "1_1") (pintype "passive"))
      (node (ref "R162") (pin "2") (pinfunction "2_2") (pintype "passive"))
      (node (ref "R94") (pin "2") (pinfunction "2_2") (pintype "passive"))
    )
    (net (code "10") (name "+12V_MEA") (class "Default")
      (node (ref "IC15") (pin "41") (pinfunction "GPIO29/ADC3_41") (pintype "bidirectional"))
      (node (ref "R94") (pin "1") (pinfunction "1_1") (pintype "passive"))
      (node (ref "R95") (pin "2") (pinfunction "2_2") (pintype "passive"))
    )
    (net (code "11") (name "5V_EN") (class "Default")
      (node (ref "IC1") (pin "6") (pinfunction "EN_6") (pintype "bidirectional"))
      (node (ref "R1") (pin "1") (pinfunction "1_1") (pintype "passive"))
      (node (ref "R161") (pin "2") (pinfunction "2_2") (pintype "passive"))
      (node (ref "R162") (pin "1") (pinfunction "1_1") (pintype "passive"))
    )
    (net (code "12") (name "AC_L") (class "Default")
      (node (ref "AC/DC1") (pin "AC_L") (pinfunction "AC/L_AC_L") (pintype "input"))
      (node (ref "AC/DC2") (pin "AC/L") (pinfunction "AC/L_AC/L") (pintype "input"))
      (node (ref "AC_L") (pin "B3,0") (pinfunction "MOUNT_B3,0") (pintype "passive"))
      (node (ref "K1") (pin "3") (pinfunction "3_3") (pintype "passive"))
      (node (ref "K1") (pin "6") (pinfunction "6_6") (pintype "passive"))
      (node (ref "K2") (pin "3") (pinfunction "3_3") (pintype "passive"))
      (node (ref "K2") (pin "6") (pinfunction "6_6") (pintype "passive"))
      (node (ref "K3") (pin "3") (pinfunction "3_3") (pintype "passive"))
      (node (ref "K3") (pin "6") (pinfunction "6_6") (pintype "passive"))
      (node (ref "K4") (pin "3") (pinfunction "3_3") (pintype "passive"))
      (node (ref "K4") (pin "6") (pinfunction "6_6") (pintype "passive"))
      (node (ref "K5") (pin "3") (pinfunction "3_3") (pintype "passive"))
      (node (ref "K5") (pin "6") (pinfunction "6_6") (pintype "passive"))
      (node (ref "K6") (pin "3") (pinfunction "3_3") (pintype "passive"))
      (node (ref "K6") (pin "6") (pinfunction "6_6") (pintype "passive"))
      (node (ref "K7") (pin "3") (pinfunction "3_3") (pintype "passive"))
      (node (ref "K7") (pin "6") (pinfunction "6_6") (pintype "passive"))
      (node (ref "K8") (pin "3") (pinfunction "3_3") (pintype "passive"))
      (node (ref "K8") (pin "6") (pinfunction "6_6") (pintype "passive"))
      (node (ref "R106") (pin "1") (pinfunction "1_1") (pintype "passive"))
      (node (ref "R62") (pin "1") (pinfunction "1_1") (pintype "passive"))
    )
    (net (code "13") (name "ADC_V_USB") (class "Default")
      (node (ref "IC15") (pin "38") (pinfunction "GPIO26/ADC0_38") (pintype "bidirectional"))
      (node (ref "R126") (pin "2") (pinfunction "2_2") (pintype "passive"))
      (node (ref "R127") (pin "1") (pinfunction "1_1") (pintype "passive"))
    )
    (net (code "14") (name "AGND") (class "Default")
      (node (ref "AC/DC1") (pin "AC_N") (pinfunction "AC/N_AC_N") (pintype "input"))
      (node (ref "AC/DC2") (pin "AC/N") (pinfunction "AC/N_AC/N") (pintype "input"))
      (node (ref "AC_N") (pin "B3,0") (pinfunction "MOUNT_B3,0") (pintype "passive"))
      (node (ref "C106") (pin "2") (pinfunction "2_2") (pintype "passive"))
      (node (ref "C107") (pin "2") (pinfunction "2_2") (pintype "passive"))
      (node (ref "C108") (pin "2") (pinfunction "2_2") (pintype "passive"))
      (node (ref "C109") (pin "2") (pinfunction "2_2") (pintype "passive"))
      (node (ref "C110") (pin "2") (pinfunction "2_2") (pintype "passive"))
      (node (ref "C111") (pin "2") (pinfunction "2_2") (pintype "passive"))
      (node (ref "C112") (pin "2") (pinfunction "2_2") (pintype "passive"))
      (node (ref "C113") (pin "2") (pinfunction "2_2") (pintype "passive"))
      (node (ref "C23") (pin "2") (pinfunction "-_2") (pintype "passive"))
      (node (ref "C24") (pin "2") (pinfunction "2_2") (pintype "passive"))
      (node (ref "C25") (pin "2") (pinfunction "2_2") (pintype "passive"))
      (node (ref "C26") (pin "2") (pinfunction "2_2") (pintype "passive"))
      (node (ref "C27") (pin "2") (pinfunction "2_2") (pintype "passive"))
      (node (ref "C28") (pin "2") (pinfunction "2_2") (pintype "passive"))
      (node (ref "C29") (pin "2") (pinfunction "2_2") (pintype "passive"))
      (node (ref "C30") (pin "2") (pinfunction "2_2") (pintype "passive"))
      (node (ref "C31") (pin "2") (pinfunction "2_2") (pintype "passive"))
      (node (ref "C32") (pin "2") (pinfunction "2_2") (pintype "passive"))
      (node (ref "C35") (pin "2") (pinfunction "-_2") (pintype "passive"))
      (node (ref "C36") (pin "2") (pinfunction "2_2") (pintype "passive"))
      (node (ref "C37") (pin "2") (pinfunction "2_2") (pintype "passive"))
      (node (ref "C38") (pin "2") (pinfunction "2_2") (pintype "passive"))
      (node (ref "C39") (pin "2") (pinfunction "2_2") (pintype "passive"))
      (node (ref "C40") (pin "2") (pinfunction "2_2") (pintype "passive"))
      (node (ref "C41") (pin "2") (pinfunction "2_2") (pintype "passive"))
      (node (ref "C42") (pin "2") (pinfunction "2_2") (pintype "passive"))
      (node (ref "C43") (pin "2") (pinfunction "2_2") (pintype "passive"))
      (node (ref "C44") (pin "2") (pinfunction "2_2") (pintype "passive"))
      (node (ref "C45") (pin "1") (pinfunction "1_1") (pintype "passive"))
      (node (ref "C47") (pin "2") (pinfunction "-_2") (pintype "passive"))
      (node (ref "C48") (pin "2") (pinfunction "2_2") (pintype "passive"))
      (node (ref "C49") (pin "2") (pinfunction "2_2") (pintype "passive"))
      (node (ref "C50") (pin "2") (pinfunction "2_2") (pintype "passive"))
      (node (ref "C53") (pin "2") (pinfunction "-_2") (pintype "passive"))
      (node (ref "C54") (pin "2") (pinfunction "2_2") (pintype "passive"))
      (node (ref "C55") (pin "2") (pinfunction "2_2") (pintype "passive"))
      (node (ref "C56") (pin "2") (pinfunction "2_2") (pintype "passive"))
      (node (ref "C57") (pin "1") (pinfunction "1_1") (pintype "passive"))
      (node (ref "D11") (pin "A") (pinfunction "A_A") (pintype "passive"))
      (node (ref "D14") (pin "A") (pinfunction "A_A") (pintype "passive"))
      (node (ref "IC10") (pin "5") (pinfunction "GND_5") (pintype "power_in"))
      (node (ref "IC11") (pin "5") (pinfunction "GND_5") (pintype "power_in"))
      (node (ref "IC12") (pin "5") (pinfunction "GND_5") (pintype "power_in"))
      (node (ref "IC14") (pin "5") (pinfunction "GND_5") (pintype "power_in"))
      (node (ref "IC16") (pin "5") (pinfunction "GND_5") (pintype "power_in"))
      (node (ref "IC6") (pin "5") (pinfunction "GND_5") (pintype "power_in"))
      (node (ref "IC7") (pin "5") (pinfunction "GND_5") (pintype "power_in"))
      (node (ref "IC8") (pin "5") (pinfunction "GND_5") (pintype "power_in"))
      (node (ref "R104") (pin "2") (pinfunction "2_2") (pintype "passive"))
      (node (ref "R108") (pin "2") (pinfunction "2_2") (pintype "passive"))
      (node (ref "R113") (pin "1") (pinfunction "1_1") (pintype "passive"))
      (node (ref "R115") (pin "2") (pinfunction "2_2") (pintype "passive"))
      (node (ref "R120") (pin "2") (pinfunction "2_2") (pintype "passive"))
      (node (ref "R25") (pin "2") (pinfunction "2_2") (pintype "passive"))
      (node (ref "R26") (pin "2") (pinfunction "2_2") (pintype "passive"))
      (node (ref "R27") (pin "2") (pinfunction "2_2") (pintype "passive"))
      (node (ref "R28") (pin "2") (pinfunction "2_2") (pintype "passive"))
      (node (ref "R29") (pin "2") (pinfunction "2_2") (pintype "passive"))
      (node (ref "R30") (pin "2") (pinfunction "2_2") (pintype "passive"))
      (node (ref "R31") (pin "2") (pinfunction "2_2") (pintype "passive"))
      (node (ref "R32") (pin "2") (pinfunction "2_2") (pintype "passive"))
      (node (ref "R33") (pin "1") (pinfunction "1_1") (pintype "passive"))
      (node (ref "R35") (pin "2") (pinfunction "2_2") (pintype "passive"))
      (node (ref "R40") (pin "2") (pinfunction "2_2") (pintype "passive"))
      (node (ref "R41") (pin "1") (pinfunction "1_1") (pintype "passive"))
      (node (ref "R43") (pin "2") (pinfunction "2_2") (pintype "passive"))
      (node (ref "R48") (pin "2") (pinfunction "2_2") (pintype "passive"))
      (node (ref "R49") (pin "1") (pinfunction "1_1") (pintype "passive"))
      (node (ref "R51") (pin "2") (pinfunction "2_2") (pintype "passive"))
      (node (ref "R56") (pin "2") (pinfunction "2_2") (pintype "passive"))
      (node (ref "R65") (pin "1") (pinfunction "1_1") (pintype "passive"))
      (node (ref "R67") (pin "2") (pinfunction "2_2") (pintype "passive"))
      (node (ref "R72") (pin "2") (pinfunction "2_2") (pintype "passive"))
      (node (ref "R73") (pin "1") (pinfunction "1_1") (pintype "passive"))
      (node (ref "R75") (pin "2") (pinfunction "2_2") (pintype "passive"))
      (node (ref "R80") (pin "2") (pinfunction "2_2") (pintype "passive"))
      (node (ref "R81") (pin "1") (pinfunction "1_1") (pintype "passive"))
      (node (ref "R83") (pin "2") (pinfunction "2_2") (pintype "passive"))
      (node (ref "R88") (pin "2") (pinfunction "2_2") (pintype "passive"))
      (node (ref "R96") (pin "2") (pinfunction "2_2") (pintype "passive"))
      (node (ref "R97") (pin "1") (pinfunction "1_1") (pintype "passive"))
      (node (ref "R99") (pin "2") (pinfunction "2_2") (pintype "passive"))
    )
    (net (code "15") (name "AVDD") (class "Default")
      (node (ref "AVDD") (pin "TP") (pinfunction "P$1_TP") (pintype "bidirectional"))
      (node (ref "C62") (pin "1") (pinfunction "1_1") (pintype "passive"))
      (node (ref "C74") (pin "1") (pinfunction "1_1") (pintype "passive"))
      (node (ref "IC15") (pin "43") (pinfunction "ADC_AVDD_43") (pintype "bidirectional"))
      (node (ref "IC17") (pin "1") (pinfunction "OUT_1") (pintype "output"))
      (node (ref "IC17") (pin "4") (pinfunction "-IN_4") (pintype "input"))
    )
    (net (code "16") (name "BUCK_EN") (class "Default")
      (node (ref "IC15") (pin "37") (pinfunction "GPIO25_37") (pintype "bidirectional"))
      (node (ref "IC2") (pin "6") (pinfunction "EN_6") (pintype "bidirectional"))
      (node (ref "R1") (pin "2") (pinfunction "2_2") (pintype "passive"))
      (node (ref "R2") (pin "2") (pinfunction "2_2") (pintype "passive"))
    )
    (net (code "17") (name "CC1") (class "Default")
      (node (ref "R125") (pin "1") (pinfunction "1_1") (pintype "passive"))
      (node (ref "USB1") (pin "A5") (pinfunction "CC1_A5") (pintype "bidirectional"))
    )
    (net (code "18") (name "CC2") (class "Default")
      (node (ref "R124") (pin "1") (pinfunction "1_1") (pintype "passive"))
      (node (ref "USB1") (pin "B5") (pinfunction "CC2_B5") (pintype "bidirectional"))
    )
    (net (code "19") (name "FB1") (class "Default")
      (node (ref "C5") (pin "2") (pinfunction "2_2") (pintype "passive"))
      (node (ref "FB-NI1") (pin "TP") (pinfunction "P$1_TP") (pintype "bidirectional"))
      (node (ref "IC13") (pin "2") (pinfunction "FB_2") (pintype "input"))
      (node (ref "R60") (pin "1") (pinfunction "1_1") (pintype "passive"))
      (node (ref "R61") (pin "2") (pinfunction "2_2") (pintype "passive"))
    )
    (net (code "20") (name "FB2") (class "Default")
      (node (ref "C51") (pin "2") (pinfunction "2_2") (pintype "passive"))
      (node (ref "FB-NI2") (pin "TP") (pinfunction "P$1_TP") (pintype "bidirectional"))
      (node (ref "IC5") (pin "2") (pinfunction "FB_2") (pintype "input"))
      (node (ref "R105") (pin "2") (pinfunction "2_2") (pintype "passive"))
      (node (ref "R107") (pin "1") (pinfunction "1_1") (pintype "passive"))
    )
    (net (code "21") (name "FBIN1") (class "Default")
      (node (ref "C22") (pin "2") (pinfunction "2_2") (pintype "passive"))
      (node (ref "D9") (pin "C") (pinfunction "C_C") (pintype "passive"))
      (node (ref "R61") (pin "1") (pinfunction "1_1") (pintype "passive"))
    )
    (net (code "22") (name "FBIN2") (class "Default")
      (node (ref "C52") (pin "2") (pinfunction "2_2") (pintype "passive"))
      (node (ref "D13") (pin "C") (pinfunction "C_C") (pintype "passive"))
      (node (ref "R105") (pin "1") (pinfunction "1_1") (pintype "passive"))
    )
    (net (code "23") (name "GND") (class "Default")
      (node (ref "AC/DC1") (pin "-V") (pinfunction "-V_-V") (pintype "output"))
      (node (ref "AC/DC2") (pin "-V") (pinfunction "-V_-V") (pintype "output"))
      (node (ref "BOOT") (pin "2") (pinfunction "P$2_2") (pintype "bidirectional"))
      (node (ref "C1") (pin "2") (pinfunction "2_2") (pintype "passive"))
      (node (ref "C10") (pin "2") (pinfunction "-_2") (pintype "passive"))
      (node (ref "C100") (pin "2") (pinfunction "2_2") (pintype "passive"))
      (node (ref "C101") (pin "2") (pinfunction "2_2") (pintype "passive"))
      (node (ref "C102") (pin "2") (pinfunction "2_2") (pintype "passive"))
      (node (ref "C103") (pin "2") (pinfunction "2_2") (pintype "passive"))
      (node (ref "C104") (pin "2") (pinfunction "2_2") (pintype "passive"))
      (node (ref "C13") (pin "2") (pinfunction "-_2") (pintype "passive"))
      (node (ref "C14") (pin "2") (pinfunction "2_2") (pintype "passive"))
      (node (ref "C15") (pin "2") (pinfunction "2_2") (pintype "passive"))
      (node (ref "C16") (pin "2") (pinfunction "-_2") (pintype "passive"))
      (node (ref "C17") (pin "2") (pinfunction "2_2") (pintype "passive"))
      (node (ref "C18") (pin "2") (pinfunction "2_2") (pintype "passive"))
      (node (ref "C19") (pin "2") (pinfunction "2_2") (pintype "passive"))
      (node (ref "C2") (pin "2") (pinfunction "2_2") (pintype "passive"))
      (node (ref "C20") (pin "2") (pinfunction "2_2") (pintype "passive"))
      (node (ref "C3") (pin "2") (pinfunction "2_2") (pintype "passive"))
      (node (ref "C33") (pin "2") (pinfunction "2_2") (pintype "passive"))
      (node (ref "C34") (pin "2") (pinfunction "2_2") (pintype "passive"))
      (node (ref "C4") (pin "2") (pinfunction "2_2") (pintype "passive"))
      (node (ref "C58") (pin "2") (pinfunction "2_2") (pintype "passive"))
      (node (ref "C59") (pin "2") (pinfunction "2_2") (pintype "passive"))
      (node (ref "C6") (pin "2") (pinfunction "2_2") (pintype "passive"))
      (node (ref "C60") (pin "2") (pinfunction "2_2") (pintype "passive"))
      (node (ref "C61") (pin "2") (pinfunction "2_2") (pintype "passive"))
      (node (ref "C62") (pin "2") (pinfunction "2_2") (pintype "passive"))
      (node (ref "C63") (pin "2") (pinfunction "2_2") (pintype "passive"))
      (node (ref "C64") (pin "2") (pinfunction "2_2") (pintype "passive"))
      (node (ref "C65") (pin "2") (pinfunction "2_2") (pintype "passive"))
      (node (ref "C66") (pin "2") (pinfunction "2_2") (pintype "passive"))
      (node (ref "C67") (pin "2") (pinfunction "2_2") (pintype "passive"))
      (node (ref "C68") (pin "2") (pinfunction "2_2") (pintype "passive"))
      (node (ref "C69") (pin "2") (pinfunction "2_2") (pintype "passive"))
      (node (ref "C7") (pin "2") (pinfunction "2_2") (pintype "passive"))
      (node (ref "C70") (pin "2") (pinfunction "2_2") (pintype "passive"))
      (node (ref "C71") (pin "2") (pinfunction "2_2") (pintype "passive"))
      (node (ref "C72") (pin "2") (pinfunction "2_2") (pintype "passive"))
      (node (ref "C73") (pin "2") (pinfunction "2_2") (pintype "passive"))
      (node (ref "C74") (pin "2") (pinfunction "2_2") (pintype "passive"))
      (node (ref "C75") (pin "2") (pinfunction "2_2") (pintype "passive"))
      (node (ref "C76") (pin "2") (pinfunction "2_2") (pintype "passive"))
      (node (ref "C77") (pin "2") (pinfunction "2_2") (pintype "passive"))
      (node (ref "C78") (pin "2") (pinfunction "2_2") (pintype "passive"))
      (node (ref "C79") (pin "2") (pinfunction "2_2") (pintype "passive"))
      (node (ref "C80") (pin "2") (pinfunction "2_2") (pintype "passive"))
      (node (ref "C83") (pin "1") (pinfunction "1_1") (pintype "passive"))
      (node (ref "C84") (pin "2") (pinfunction "2_2") (pintype "passive"))
      (node (ref "C85") (pin "2") (pinfunction "2_2") (pintype "passive"))
      (node (ref "C86") (pin "2") (pinfunction "2_2") (pintype "passive"))
      (node (ref "C87") (pin "2") (pinfunction "2_2") (pintype "passive"))
      (node (ref "C88") (pin "2") (pinfunction "2_2") (pintype "passive"))
      (node (ref "C89") (pin "2") (pinfunction "2_2") (pintype "passive"))
      (node (ref "C90") (pin "2") (pinfunction "2_2") (pintype "passive"))
      (node (ref "C91") (pin "2") (pinfunction "2_2") (pintype "passive"))
      (node (ref "C92") (pin "2") (pinfunction "2_2") (pintype "passive"))
      (node (ref "C93") (pin "2") (pinfunction "2_2") (pintype "passive"))
      (node (ref "C94") (pin "2") (pinfunction "2_2") (pintype "passive"))
      (node (ref "C95") (pin "2") (pinfunction "2_2") (pintype "passive"))
      (node (ref "C96") (pin "2") (pinfunction "2_2") (pintype "passive"))
      (node (ref "C97") (pin "2") (pinfunction "2_2") (pintype "passive"))
      (node (ref "C98") (pin "2") (pinfunction "2_2") (pintype "passive"))
      (node (ref "C99") (pin "2") (pinfunction "2_2") (pintype "passive"))
      (node (ref "D16") (pin "A") (pinfunction "A_A") (pintype "passive"))
      (node (ref "DAT") (pin "C") (pinfunction "C_C") (pintype "passive"))
      (node (ref "DSP") (pin "5") (pinfunction "5_5") (pintype "bidirectional"))
      (node (ref "DSP") (pin "8") (pinfunction "8_8") (pintype "bidirectional"))
      (node (ref "DSP") (pin "Z0") (pinfunction "Z1_Z0") (pintype "bidirectional"))
      (node (ref "DSP") (pin "Z1") (pinfunction "Z1_Z1") (pintype "bidirectional"))
      (node (ref "DSP") (pin "Z2") (pinfunction "Z2_Z2") (pintype "bidirectional"))
      (node (ref "DSP") (pin "Z3") (pinfunction "Z3_Z3") (pintype "bidirectional"))
      (node (ref "DSP") (pin "Z4") (pinfunction "Z3_Z4") (pintype "bidirectional"))
      (node (ref "DSP") (pin "Z5") (pinfunction "Z4_Z5") (pintype "bidirectional"))
      (node (ref "ESD1") (pin "1") (pinfunction "A_1") (pintype "bidirectional"))
      (node (ref "ETH1") (pin "8") (pinfunction "GND_8") (pintype "power_in"))
      (node (ref "GDGC") (pin "4") (pinfunction "P$4_4") (pintype "bidirectional"))
      (node (ref "GND") (pin "TP") (pinfunction "P$1_TP") (pintype "bidirectional"))
      (node (ref "GND-3") (pin "TP") (pinfunction "P$1_TP") (pintype "bidirectional"))
      (node (ref "GND-5") (pin "TP") (pinfunction "P$1_TP") (pintype "bidirectional"))
      (node (ref "IC1") (pin "4") (pinfunction "GND_4") (pintype "bidirectional"))
      (node (ref "IC15") (pin "19") (pinfunction "TESTEN_19") (pintype "bidirectional"))
      (node (ref "IC15") (pin "PAD") (pinfunction "GND_PAD") (pintype "bidirectional"))
      (node (ref "IC17") (pin "5") (pinfunction "V-_5") (pintype "power_in"))
      (node (ref "IC18") (pin "4") (pinfunction "GND_4") (pintype "power_in"))
      (node (ref "IC18") (pin "PAD") (pinfunction "GND_PAD") (pintype "power_in"))
      (node (ref "IC19") (pin "2") (pinfunction "A1_2") (pintype "bidirectional"))
      (node (ref "IC19") (pin "3") (pinfunction "A2_3") (pintype "bidirectional"))
      (node (ref "IC19") (pin "4") (pinfunction "GND_4") (pintype "power_in"))
      (node (ref "IC19") (pin "7") (pinfunction "WP_7") (pintype "bidirectional"))
      (node (ref "IC19") (pin "9") (pinfunction "GND_9") (pintype "power_in"))
      (node (ref "IC2") (pin "4") (pinfunction "GND_4") (pintype "bidirectional"))
      (node (ref "IC20") (pin "14") (pinfunction "AGND_14") (pintype "power_in"))
      (node (ref "IC20") (pin "16") (pinfunction "AGND_16") (pintype "power_in"))
      (node (ref "IC20") (pin "19") (pinfunction "AGND_19") (pintype "power_in"))
      (node (ref "IC20") (pin "29") (pinfunction "GND_29") (pintype "passive"))
      (node (ref "IC20") (pin "3") (pinfunction "AGND_3") (pintype "power_in"))
      (node (ref "IC20") (pin "48") (pinfunction "AGND_48") (pintype "power_in"))
      (node (ref "IC20") (pin "9") (pinfunction "AGND_9") (pintype "power_in"))
      (node (ref "IC21") (pin "2") (pinfunction "GND_2") (pintype "bidirectional"))
      (node (ref "IC22") (pin "5") (pinfunction "V-_5") (pintype "power_in"))
      (node (ref "IC3") (pin "9") (pinfunction "GND_9") (pintype "bidirectional"))
      (node (ref "IC4") (pin "11") (pinfunction "A0_11") (pintype "bidirectional"))
      (node (ref "IC4") (pin "12") (pinfunction "A1_12") (pintype "bidirectional"))
      (node (ref "IC4") (pin "13") (pinfunction "A2_13") (pintype "bidirectional"))
      (node (ref "IC4") (pin "6") (pinfunction "VSS_6") (pintype "bidirectional"))
      (node (ref "IC4") (pin "PAD") (pinfunction "VSS_PAD") (pintype "bidirectional"))
      (node (ref "IC9") (pin "8") (pinfunction "GND_8") (pintype "power_in"))
      (node (ref "OPT1") (pin "11") (pinfunction "11_11") (pintype "passive"))
      (node (ref "OPT1") (pin "13") (pinfunction "13_13") (pintype "passive"))
      (node (ref "OPT1") (pin "15") (pinfunction "15_15") (pintype "passive"))
      (node (ref "OPT1") (pin "9") (pinfunction "9_9") (pintype "passive"))
      (node (ref "OPT2") (pin "11") (pinfunction "11_11") (pintype "passive"))
      (node (ref "OPT2") (pin "13") (pinfunction "13_13") (pintype "passive"))
      (node (ref "OPT2") (pin "15") (pinfunction "15_15") (pintype "passive"))
      (node (ref "OPT2") (pin "9") (pinfunction "9_9") (pintype "passive"))
      (node (ref "P12ON") (pin "C") (pinfunction "C_C") (pintype "passive"))
      (node (ref "P3ON") (pin "C") (pinfunction "C_C") (pintype "passive"))
      (node (ref "P5ON") (pin "C") (pinfunction "C_C") (pintype "passive"))
      (node (ref "PROC") (pin "C") (pinfunction "C_C") (pintype "passive"))
      (node (ref "R110") (pin "1") (pinfunction "1_1") (pintype "passive"))
      (node (ref "R12") (pin "2") (pinfunction "2_2") (pintype "passive"))
      (node (ref "R121") (pin "2") (pinfunction "2_2") (pintype "passive"))
      (node (ref "R124") (pin "2") (pinfunction "2_2") (pintype "passive"))
      (node (ref "R125") (pin "2") (pinfunction "2_2") (pintype "passive"))
      (node (ref "R127") (pin "2") (pinfunction "2_2") (pintype "passive"))
      (node (ref "R129") (pin "1") (pinfunction "1_1") (pintype "passive"))
      (node (ref "R131") (pin "2") (pinfunction "2_2") (pintype "passive"))
      (node (ref "R14") (pin "2") (pinfunction "2_2") (pintype "passive"))
      (node (ref "R143") (pin "1") (pinfunction "1_1") (pintype "passive"))
      (node (ref "R151") (pin "1") (pinfunction "1_1") (pintype "passive"))
      (node (ref "R161") (pin "1") (pinfunction "1_1") (pintype "passive"))
      (node (ref "R2") (pin "1") (pinfunction "1_1") (pintype "passive"))
      (node (ref "R4") (pin "2") (pinfunction "2_2") (pintype "passive"))
      (node (ref "R6") (pin "2") (pinfunction "2_2") (pintype "passive"))
      (node (ref "R93") (pin "5") (pinfunction "5_5") (pintype "passive"))
      (node (ref "R93") (pin "6") (pinfunction "6_6") (pintype "passive"))
      (node (ref "R93") (pin "7") (pinfunction "7_7") (pintype "passive"))
      (node (ref "R93") (pin "8") (pinfunction "8_8") (pintype "passive"))
      (node (ref "R95") (pin "1") (pinfunction "1_1") (pintype "passive"))
      (node (ref "REF1") (pin "2") (pinfunction "A_2") (pintype "passive"))
      (node (ref "REF1") (pin "3") (pinfunction "A_3") (pintype "passive"))
      (node (ref "RESET") (pin "1") (pinfunction "P$1_1") (pintype "bidirectional"))
      (node (ref "RGTG") (pin "2") (pinfunction "P$2_2") (pintype "bidirectional"))
      (node (ref "RGTG") (pin "4") (pinfunction "P$4_4") (pintype "bidirectional"))
      (node (ref "USB1") (pin "GND") (pinfunction "GND_GND") (pintype "power_in"))
      (node (ref "USB1") (pin "GND2") (pinfunction "GND_GND2") (pintype "power_in"))
      (node (ref "X1") (pin "2") (pinfunction "GND_2") (pintype "passive"))
      (node (ref "X1") (pin "4") (pinfunction "GND_4") (pintype "passive"))
      (node (ref "X2") (pin "2") (pinfunction "GND_2") (pintype "passive"))
      (node (ref "X2") (pin "4") (pinfunction "GND_4") (pintype "passive"))
    )
    (net (code "24") (name "I2C0_SCL") (class "Default")
      (node (ref "DSP") (pin "7") (pinfunction "7_7") (pintype "bidirectional"))
      (node (ref "IC15") (pin "7") (pinfunction "GPIO5_7") (pintype "bidirectional"))
      (node (ref "R130") (pin "A1") (pinfunction "1_A1") (pintype "passive"))
    )
    (net (code "25") (name "I2C0_SDA") (class "Default")
      (node (ref "DSP") (pin "6") (pinfunction "6_6") (pintype "bidirectional"))
      (node (ref "IC15") (pin "6") (pinfunction "GPIO4_6") (pintype "bidirectional"))
      (node (ref "R130") (pin "B1") (pinfunction "2_B1") (pintype "passive"))
    )
    (net (code "26") (name "I2C1_SCL") (class "Default")
      (node (ref "IC15") (pin "5") (pinfunction "GPIO3_5") (pintype "bidirectional"))
      (node (ref "IC19") (pin "6") (pinfunction "SCL_6") (pintype "bidirectional"))
      (node (ref "IC4") (pin "8") (pinfunction "SCL_8") (pintype "bidirectional"))
      (node (ref "R130") (pin "C1") (pinfunction "3_C1") (pintype "passive"))
    )
    (net (code "27") (name "I2C1_SDA") (class "Default")
      (node (ref "IC15") (pin "4") (pinfunction "GPIO2_4") (pintype "bidirectional"))
      (node (ref "IC19") (pin "5") (pinfunction "SDA_5") (pintype "bidirectional"))
      (node (ref "IC4") (pin "9") (pinfunction "SDA_9") (pintype "bidirectional"))
      (node (ref "R130") (pin "D1") (pinfunction "4_D1") (pintype "passive"))
    )
    (net (code "28") (name "KEY_0") (class "Default")
      (node (ref "DSP") (pin "12") (pinfunction "12_12") (pintype "bidirectional"))
      (node (ref "IC15") (pin "15") (pinfunction "GPIO12_15") (pintype "bidirectional"))
    )
    (net (code "29") (name "KEY_1") (class "Default")
      (node (ref "DSP") (pin "11") (pinfunction "11_11") (pintype "bidirectional"))
      (node (ref "IC15") (pin "16") (pinfunction "GPIO13_16") (pintype "bidirectional"))
    )
    (net (code "30") (name "KEY_2") (class "Default")
      (node (ref "DSP") (pin "10") (pinfunction "10_10") (pintype "bidirectional"))
      (node (ref "IC15") (pin "17") (pinfunction "GPIO14_17") (pintype "bidirectional"))
    )
    (net (code "31") (name "KEY_3") (class "Default")
      (node (ref "DSP") (pin "9") (pinfunction "9_9") (pintype "bidirectional"))
      (node (ref "IC15") (pin "18") (pinfunction "GPIO15_18") (pintype "bidirectional"))
    )
    (net (code "32") (name "LCD_BL") (class "Default")
      (node (ref "DSP") (pin "13") (pinfunction "13_13") (pintype "bidirectional"))
      (node (ref "IC15") (pin "9") (pinfunction "GPIO7_9") (pintype "bidirectional"))
    )
    (net (code "33") (name "LCD_CS") (class "Default")
      (node (ref "DSP") (pin "19") (pinfunction "19_19") (pintype "bidirectional"))
      (node (ref "IC15") (pin "12") (pinfunction "GPIO9_12") (pintype "bidirectional"))
      (node (ref "R149") (pin "C2") (pinfunction "6_C2") (pintype "passive"))
    )
    (net (code "34") (name "LCD_DC") (class "Default")
      (node (ref "DSP") (pin "18") (pinfunction "18_18") (pintype "bidirectional"))
      (node (ref "IC15") (pin "8") (pinfunction "GPIO6_8") (pintype "bidirectional"))
    )
    (net (code "35") (name "LCD_MISO") (class "Default")
      (node (ref "DSP") (pin "15") (pinfunction "15_15") (pintype "bidirectional"))
      (node (ref "IC15") (pin "11") (pinfunction "GPIO8_11") (pintype "bidirectional"))
      (node (ref "R149") (pin "B2") (pinfunction "7_B2") (pintype "passive"))
    )
    (net (code "36") (name "LCD_MOSI") (class "Default")
      (node (ref "DSP") (pin "16") (pinfunction "16_16") (pintype "bidirectional"))
      (node (ref "IC15") (pin "14") (pinfunction "GPIO11_14") (pintype "bidirectional"))
    )
    (net (code "37") (name "LCD_RES") (class "Default")
      (node (ref "DSP") (pin "14") (pinfunction "14_14") (pintype "bidirectional"))
      (node (ref "IC15") (pin "34") (pinfunction "GPIO22_34") (pintype "bidirectional"))
      (node (ref "R149") (pin "A2") (pinfunction "8_A2") (pintype "passive"))
    )
    (net (code "38") (name "LCD_SCLK") (class "Default")
      (node (ref "DSP") (pin "17") (pinfunction "17_17") (pintype "bidirectional"))
      (node (ref "IC15") (pin "13") (pinfunction "GPIO10_13") (pintype "bidirectional"))
    )
    (net (code "39") (name "LREC1") (class "Default")
      (node (ref "C35") (pin "1") (pinfunction "+_1") (pintype "passive"))
      (node (ref "D10") (pin "C") (pinfunction "C_C") (pintype "passive"))
      (node (ref "IC13") (pin "5") (pinfunction "DRAIN_5") (pintype "input"))
      (node (ref "L-REC1") (pin "TP") (pinfunction "P$1_TP") (pintype "bidirectional"))
    )
    (net (code "40") (name "LREC2") (class "Default")
      (node (ref "C47") (pin "1") (pinfunction "+_1") (pintype "passive"))
      (node (ref "D12") (pin "C") (pinfunction "C_C") (pintype "passive"))
      (node (ref "IC5") (pin "5") (pinfunction "DRAIN_5") (pintype "input"))
      (node (ref "L-REC2") (pin "TP") (pinfunction "P$1_TP") (pintype "bidirectional"))
    )
    (net (code "41") (name "MCP_DSP_RST") (class "Default")
      (node (ref "DSP") (pin "20") (pinfunction "20_20") (pintype "bidirectional"))
      (node (ref "IC15") (pin "36") (pinfunction "GPIO24_36") (pintype "bidirectional"))
      (node (ref "R147") (pin "1") (pinfunction "1_1") (pintype "passive"))
    )
    (net (code "42") (name "MCP_REL_RST") (class "Default")
      (node (ref "IC15") (pin "35") (pinfunction "GPIO23_35") (pintype "bidirectional"))
      (node (ref "IC4") (pin "14") (pinfunction "~{RESET}_14") (pintype "bidirectional"))
    )
    (net (code "43") (name "MCP_VIN") (class "Default")
      (node (ref "C102") (pin "1") (pinfunction "1_1") (pintype "passive"))
      (node (ref "C63") (pin "1") (pinfunction "1_1") (pintype "passive"))
      (node (ref "IC17") (pin "2") (pinfunction "V+_2") (pintype "power_in"))
      (node (ref "R152") (pin "2") (pinfunction "2_2") (pintype "passive"))
    )
    (net (code "44") (name "MUX_A") (class "Default")
      (node (ref "IC4") (pin "25") (pinfunction "IO2.0_25") (pintype "bidirectional"))
      (node (ref "IC9") (pin "11") (pinfunction "A_11") (pintype "input"))
      (node (ref "R93") (pin "4") (pinfunction "4_4") (pintype "passive"))
    )
    (net (code "45") (name "MUX_B") (class "Default")
      (node (ref "IC4") (pin "26") (pinfunction "IO2.1_26") (pintype "bidirectional"))
      (node (ref "IC9") (pin "10") (pinfunction "B_10") (pintype "input"))
      (node (ref "R93") (pin "3") (pinfunction "3_3") (pintype "passive"))
    )
    (net (code "46") (name "MUX_C") (class "Default")
      (node (ref "IC4") (pin "27") (pinfunction "IO2.2_27") (pintype "bidirectional"))
      (node (ref "IC9") (pin "9") (pinfunction "C_9") (pintype "input"))
      (node (ref "R93") (pin "2") (pinfunction "2_2") (pintype "passive"))
    )
    (net (code "47") (name "MUX_EN") (class "Default")
      (node (ref "IC4") (pin "28") (pinfunction "IO2.3_28") (pintype "bidirectional"))
      (node (ref "IC9") (pin "7") (pinfunction "~{EN}_7") (pintype "input"))
      (node (ref "R93") (pin "1") (pinfunction "1_1") (pintype "passive"))
    )
    (net (code "48") (name "N_OUT1") (class "Default")
      (node (ref "N_OUT1") (pin "B2,8") (pinfunction "MOUNT_B2,8") (pintype "passive"))
      (node (ref "R25") (pin "1") (pinfunction "1_1") (pintype "passive"))
      (node (ref "R34") (pin "1") (pinfunction "1_1") (pintype "passive"))
      (node (ref "R35") (pin "1") (pinfunction "1_1") (pintype "passive"))
    )
    (net (code "49") (name "N_OUT2") (class "Default")
      (node (ref "N_OUT2") (pin "B2,8") (pinfunction "MOUNT_B2,8") (pintype "passive"))
      (node (ref "R32") (pin "1") (pinfunction "1_1") (pintype "passive"))
      (node (ref "R50") (pin "1") (pinfunction "1_1") (pintype "passive"))
      (node (ref "R51") (pin "1") (pinfunction "1_1") (pintype "passive"))
    )
    (net (code "50") (name "N_OUT3") (class "Default")
      (node (ref "N_OUT3") (pin "B2,8") (pinfunction "MOUNT_B2,8") (pintype "passive"))
      (node (ref "R31") (pin "1") (pinfunction "1_1") (pintype "passive"))
      (node (ref "R66") (pin "1") (pinfunction "1_1") (pintype "passive"))
      (node (ref "R67") (pin "1") (pinfunction "1_1") (pintype "passive"))
    )
    (net (code "51") (name "N_OUT4") (class "Default")
      (node (ref "N_OUT4") (pin "B2,8") (pinfunction "MOUNT_B2,8") (pintype "passive"))
      (node (ref "R30") (pin "1") (pinfunction "1_1") (pintype "passive"))
      (node (ref "R82") (pin "1") (pinfunction "1_1") (pintype "passive"))
      (node (ref "R83") (pin "1") (pinfunction "1_1") (pintype "passive"))
    )
    (net (code "52") (name "N_OUT5") (class "Default")
      (node (ref "N_OUT5") (pin "B2,8") (pinfunction "MOUNT_B2,8") (pintype "passive"))
      (node (ref "R26") (pin "1") (pinfunction "1_1") (pintype "passive"))
      (node (ref "R42") (pin "1") (pinfunction "1_1") (pintype "passive"))
      (node (ref "R43") (pin "1") (pinfunction "1_1") (pintype "passive"))
    )
    (net (code "53") (name "N_OUT6") (class "Default")
      (node (ref "N_OUT6") (pin "B2,8") (pinfunction "MOUNT_B2,8") (pintype "passive"))
      (node (ref "R27") (pin "1") (pinfunction "1_1") (pintype "passive"))
      (node (ref "R74") (pin "1") (pinfunction "1_1") (pintype "passive"))
      (node (ref "R75") (pin "1") (pinfunction "1_1") (pintype "passive"))
    )
    (net (code "54") (name "N_OUT7") (class "Default")
      (node (ref "N_OUT7") (pin "B2,8") (pinfunction "MOUNT_B2,8") (pintype "passive"))
      (node (ref "R28") (pin "1") (pinfunction "1_1") (pintype "passive"))
      (node (ref "R98") (pin "1") (pinfunction "1_1") (pintype "passive"))
      (node (ref "R99") (pin "1") (pinfunction "1_1") (pintype "passive"))
    )
    (net (code "55") (name "N_OUT8") (class "Default")
      (node (ref "N_OUT8") (pin "B2,8") (pinfunction "MOUNT_B2,8") (pintype "passive"))
      (node (ref "R114") (pin "1") (pinfunction "1_1") (pintype "passive"))
      (node (ref "R115") (pin "1") (pinfunction "1_1") (pintype "passive"))
      (node (ref "R29") (pin "1") (pinfunction "1_1") (pintype "passive"))
    )
    (net (code "56") (name "Net-(3VFB-P$1)") (class "Default")
      (node (ref "3VFB") (pin "TP") (pinfunction "P$1_TP") (pintype "bidirectional"))
      (node (ref "C12") (pin "2") (pinfunction "2_2") (pintype "passive"))
      (node (ref "R10") (pin "2") (pinfunction "2_2") (pintype "passive"))
      (node (ref "R13") (pin "2") (pinfunction "2_2") (pintype "passive"))
      (node (ref "R14") (pin "1") (pinfunction "1_1") (pintype "passive"))
    )
    (net (code "57") (name "Net-(5VFB-P$1)") (class "Default")
      (node (ref "5VFB") (pin "TP") (pinfunction "P$1_TP") (pintype "bidirectional"))
      (node (ref "C11") (pin "2") (pinfunction "2_2") (pintype "passive"))
      (node (ref "R11") (pin "2") (pinfunction "2_2") (pintype "passive"))
      (node (ref "R12") (pin "1") (pinfunction "1_1") (pintype "passive"))
      (node (ref "R8") (pin "2") (pinfunction "2_2") (pintype "passive"))
    )
    (net (code "58") (name "Net-(12VDC-P$1)") (class "Default")
      (node (ref "12VDC") (pin "TP") (pinfunction "P$1_TP") (pintype "bidirectional"))
      (node (ref "AC/DC1") (pin "+V") (pinfunction "+V_+V") (pintype "output"))
      (node (ref "AC/DC2") (pin "+V") (pinfunction "+V_+V") (pintype "output"))
      (node (ref "C10") (pin "1") (pinfunction "+_1") (pintype "passive"))
      (node (ref "C13") (pin "1") (pinfunction "+_1") (pintype "passive"))
      (node (ref "C16") (pin "1") (pinfunction "+_1") (pintype "passive"))
      (node (ref "D16") (pin "C") (pinfunction "C_C") (pintype "passive"))
      (node (ref "J10") (pin "2") (pinfunction "2_2") (pintype "passive"))
      (node (ref "J8") (pin "2") (pinfunction "2_2") (pintype "passive"))
      (node (ref "J9") (pin "2") (pinfunction "2_2") (pintype "passive"))
    )
    (net (code "59") (name "Net-(C8-Pad1)") (class "Default")
      (node (ref "C8") (pin "1") (pinfunction "1_1") (pintype "passive"))
      (node (ref "R7") (pin "1") (pinfunction "1_1") (pintype "passive"))
    )
    (net (code "60") (name "Net-(C9-Pad1)") (class "Default")
      (node (ref "C9") (pin "1") (pinfunction "1_1") (pintype "passive"))
      (node (ref "R9") (pin "1") (pinfunction "1_1") (pintype "passive"))
    )
    (net (code "61") (name "Net-(C106-Pad1)") (class "Default")
      (node (ref "C106") (pin "1") (pinfunction "1_1") (pintype "passive"))
      (node (ref "OPT1") (pin "2") (pinfunction "2_2") (pintype "passive"))
      (node (ref "R59") (pin "2") (pinfunction "2_2") (pintype "passive"))
    )
    (net (code "62") (name "Net-(C107-Pad1)") (class "Default")
      (node (ref "C107") (pin "1") (pinfunction "1_1") (pintype "passive"))
      (node (ref "OPT1") (pin "4") (pinfunction "4_4") (pintype "passive"))
      (node (ref "R153") (pin "2") (pinfunction "2_2") (pintype "passive"))
    )
    (net (code "63") (name "Net-(C108-Pad1)") (class "Default")
      (node (ref "C108") (pin "1") (pinfunction "1_1") (pintype "passive"))
      (node (ref "OPT1") (pin "6") (pinfunction "6_6") (pintype "passive"))
      (node (ref "R154") (pin "2") (pinfunction "2_2") (pintype "passive"))
    )
    (net (code "64") (name "Net-(C109-Pad1)") (class "Default")
      (node (ref "C109") (pin "1") (pinfunction "1_1") (pintype "passive"))
      (node (ref "OPT1") (pin "8") (pinfunction "8_8") (pintype "passive"))
      (node (ref "R155") (pin "2") (pinfunction "2_2") (pintype "passive"))
    )
    (net (code "65") (name "Net-(C110-Pad1)") (class "Default")
      (node (ref "C110") (pin "1") (pinfunction "1_1") (pintype "passive"))
      (node (ref "OPT2") (pin "2") (pinfunction "2_2") (pintype "passive"))
      (node (ref "R156") (pin "2") (pinfunction "2_2") (pintype "passive"))
    )
    (net (code "66") (name "Net-(C111-Pad1)") (class "Default")
      (node (ref "C111") (pin "1") (pinfunction "1_1") (pintype "passive"))
      (node (ref "OPT2") (pin "4") (pinfunction "4_4") (pintype "passive"))
      (node (ref "R157") (pin "2") (pinfunction "2_2") (pintype "passive"))
    )
    (net (code "67") (name "Net-(C112-Pad1)") (class "Default")
      (node (ref "C112") (pin "1") (pinfunction "1_1") (pintype "passive"))
      (node (ref "OPT2") (pin "6") (pinfunction "6_6") (pintype "passive"))
      (node (ref "R158") (pin "2") (pinfunction "2_2") (pintype "passive"))
    )
    (net (code "68") (name "Net-(C113-Pad1)") (class "Default")
      (node (ref "C113") (pin "1") (pinfunction "1_1") (pintype "passive"))
      (node (ref "OPT2") (pin "8") (pinfunction "8_8") (pintype "passive"))
      (node (ref "R159") (pin "2") (pinfunction "2_2") (pintype "passive"))
    )
    (net (code "69") (name "Net-(D10-PadA)") (class "Default")
      (node (ref "D10") (pin "A") (pinfunction "A_A") (pintype "passive"))
      (node (ref "R62") (pin "2") (pinfunction "2_2") (pintype "passive"))
    )
    (net (code "70") (name "Net-(D12-PadA)") (class "Default")
      (node (ref "D12") (pin "A") (pinfunction "A_A") (pintype "passive"))
      (node (ref "R106") (pin "2") (pinfunction "2_2") (pintype "passive"))
    )
    (net (code "71") (name "Net-(DAT-PadA)") (class "Default")
      (node (ref "DAT") (pin "A") (pinfunction "A_A") (pintype "passive"))
      (node (ref "R122") (pin "2") (pinfunction "2_2") (pintype "passive"))
    )
    (net (code "72") (name "Net-(ETH1-GREEN-)") (class "Default")
      (node (ref "ETH1") (pin "9") (pinfunction "GREEN-_9") (pintype "passive"))
      (node (ref "R142") (pin "2") (pinfunction "2_2") (pintype "passive"))
    )
    (net (code "73") (name "Net-(ETH1-YELLOW-)") (class "Default")
      (node (ref "ETH1") (pin "11") (pinfunction "YELLOW-_11") (pintype "passive"))
      (node (ref "R141") (pin "2") (pinfunction "2_2") (pintype "passive"))
    )
    (net (code "74") (name "Net-(IC1-AAM)") (class "Default")
      (node (ref "IC1") (pin "1") (pinfunction "AAM_1") (pintype "bidirectional"))
      (node (ref "R3") (pin "2") (pinfunction "2_2") (pintype "passive"))
      (node (ref "R4") (pin "1") (pinfunction "1_1") (pintype "passive"))
    )
    (net (code "75") (name "Net-(IC1-BST)") (class "Default")
      (node (ref "IC1") (pin "5") (pinfunction "BST_5") (pintype "bidirectional"))
      (node (ref "R7") (pin "2") (pinfunction "2_2") (pintype "passive"))
    )
    (net (code "76") (name "Net-(IC1-FB)") (class "Default")
      (node (ref "IC1") (pin "8") (pinfunction "FB_8") (pintype "bidirectional"))
      (node (ref "R8") (pin "1") (pinfunction "1_1") (pintype "passive"))
    )
    (net (code "77") (name "Net-(IC1-SW)") (class "Default")
      (node (ref "C8") (pin "2") (pinfunction "2_2") (pintype "passive"))
      (node (ref "IC1") (pin "3") (pinfunction "SW_3") (pintype "bidirectional"))
      (node (ref "L1") (pin "1") (pinfunction "1_1") (pintype "passive"))
      (node (ref "SW") (pin "TP") (pinfunction "P$1_TP") (pintype "bidirectional"))
    )
    (net (code "78") (name "Net-(IC1-VCC)") (class "Default")
      (node (ref "C6") (pin "1") (pinfunction "1_1") (pintype "passive"))
      (node (ref "IC1") (pin "7") (pinfunction "VCC_7") (pintype "bidirectional"))
      (node (ref "R3") (pin "1") (pinfunction "1_1") (pintype "passive"))
    )
    (net (code "79") (name "Net-(IC2-AAM)") (class "Default")
      (node (ref "IC2") (pin "1") (pinfunction "AAM_1") (pintype "bidirectional"))
      (node (ref "R5") (pin "2") (pinfunction "2_2") (pintype "passive"))
      (node (ref "R6") (pin "1") (pinfunction "1_1") (pintype "passive"))
    )
    (net (code "80") (name "Net-(IC2-BST)") (class "Default")
      (node (ref "IC2") (pin "5") (pinfunction "BST_5") (pintype "bidirectional"))
      (node (ref "R9") (pin "2") (pinfunction "2_2") (pintype "passive"))
    )
    (net (code "81") (name "Net-(IC2-FB)") (class "Default")
      (node (ref "IC2") (pin "8") (pinfunction "FB_8") (pintype "bidirectional"))
      (node (ref "R10") (pin "1") (pinfunction "1_1") (pintype "passive"))
    )
    (net (code "82") (name "Net-(IC2-SW)") (class "Default")
      (node (ref "C9") (pin "2") (pinfunction "2_2") (pintype "passive"))
      (node (ref "IC2") (pin "3") (pinfunction "SW_3") (pintype "bidirectional"))
      (node (ref "L2") (pin "1") (pinfunction "1_1") (pintype "passive"))
      (node (ref "SW3") (pin "TP") (pinfunction "P$1_TP") (pintype "bidirectional"))
    )
    (net (code "83") (name "Net-(IC2-VCC)") (class "Default")
      (node (ref "C7") (pin "1") (pinfunction "1_1") (pintype "passive"))
      (node (ref "IC2") (pin "7") (pinfunction "VCC_7") (pintype "bidirectional"))
      (node (ref "R5") (pin "1") (pinfunction "1_1") (pintype "passive"))
    )
    (net (code "84") (name "Net-(IC3-1C)") (class "Default")
      (node (ref "IC3") (pin "18") (pinfunction "1C_18") (pintype "bidirectional"))
      (node (ref "R17") (pin "1") (pinfunction "1_1") (pintype "passive"))
    )
    (net (code "85") (name "Net-(IC3-2C)") (class "Default")
      (node (ref "IC3") (pin "17") (pinfunction "2C_17") (pintype "bidirectional"))
      (node (ref "R18") (pin "1") (pinfunction "1_1") (pintype "passive"))
    )
    (net (code "86") (name "Net-(IC3-3C)") (class "Default")
      (node (ref "IC3") (pin "16") (pinfunction "3C_16") (pintype "bidirectional"))
      (node (ref "R19") (pin "1") (pinfunction "1_1") (pintype "passive"))
    )
    (net (code "87") (name "Net-(IC3-4C)") (class "Default")
      (node (ref "IC3") (pin "15") (pinfunction "4C_15") (pintype "bidirectional"))
      (node (ref "R20") (pin "1") (pinfunction "1_1") (pintype "passive"))
    )
    (net (code "88") (name "Net-(IC3-5C)") (class "Default")
      (node (ref "IC3") (pin "14") (pinfunction "5C_14") (pintype "bidirectional"))
      (node (ref "R21") (pin "1") (pinfunction "1_1") (pintype "passive"))
    )
    (net (code "89") (name "Net-(IC3-6C)") (class "Default")
      (node (ref "IC3") (pin "13") (pinfunction "6C_13") (pintype "bidirectional"))
      (node (ref "R22") (pin "1") (pinfunction "1_1") (pintype "passive"))
    )
    (net (code "90") (name "Net-(IC3-7C)") (class "Default")
      (node (ref "IC3") (pin "12") (pinfunction "7C_12") (pintype "bidirectional"))
      (node (ref "R23") (pin "1") (pinfunction "1_1") (pintype "passive"))
    )
    (net (code "91") (name "Net-(IC3-8C)") (class "Default")
      (node (ref "IC3") (pin "11") (pinfunction "8C_11") (pintype "bidirectional"))
      (node (ref "R24") (pin "1") (pinfunction "1_1") (pintype "passive"))
    )
    (net (code "92") (name "Net-(IC6-INN)") (class "Default")
      (node (ref "C25") (pin "1") (pinfunction "1_1") (pintype "passive"))
      (node (ref "IC6") (pin "3") (pinfunction "INN_3") (pintype "input"))
      (node (ref "R34") (pin "2") (pinfunction "2_2") (pintype "passive"))
    )
    (net (code "93") (name "Net-(IC6-INP)") (class "Default")
      (node (ref "C24") (pin "1") (pinfunction "1_1") (pintype "passive"))
      (node (ref "IC6") (pin "2") (pinfunction "INP_2") (pintype "input"))
      (node (ref "R33") (pin "2") (pinfunction "2_2") (pintype "passive"))
    )
    (net (code "94") (name "Net-(IC6-VP)") (class "Default")
      (node (ref "C26") (pin "1") (pinfunction "1_1") (pintype "passive"))
      (node (ref "IC6") (pin "4") (pinfunction "VP_4") (pintype "input"))
      (node (ref "R39") (pin "2") (pinfunction "2_2") (pintype "passive"))
      (node (ref "R40") (pin "1") (pinfunction "1_1") (pintype "passive"))
    )
    (net (code "95") (name "Net-(IC7-INN)") (class "Default")
      (node (ref "C28") (pin "1") (pinfunction "1_1") (pintype "passive"))
      (node (ref "IC7") (pin "3") (pinfunction "INN_3") (pintype "input"))
      (node (ref "R42") (pin "2") (pinfunction "2_2") (pintype "passive"))
    )
    (net (code "96") (name "Net-(IC7-INP)") (class "Default")
      (node (ref "C27") (pin "1") (pinfunction "1_1") (pintype "passive"))
      (node (ref "IC7") (pin "2") (pinfunction "INP_2") (pintype "input"))
      (node (ref "R41") (pin "2") (pinfunction "2_2") (pintype "passive"))
    )
    (net (code "97") (name "Net-(IC7-VP)") (class "Default")
      (node (ref "C29") (pin "1") (pinfunction "1_1") (pintype "passive"))
      (node (ref "IC7") (pin "4") (pinfunction "VP_4") (pintype "input"))
      (node (ref "R47") (pin "2") (pinfunction "2_2") (pintype "passive"))
      (node (ref "R48") (pin "1") (pinfunction "1_1") (pintype "passive"))
    )
    (net (code "98") (name "Net-(IC8-INN)") (class "Default")
      (node (ref "C31") (pin "1") (pinfunction "1_1") (pintype "passive"))
      (node (ref "IC8") (pin "3") (pinfunction "INN_3") (pintype "input"))
      (node (ref "R50") (pin "2") (pinfunction "2_2") (pintype "passive"))
    )
    (net (code "99") (name "Net-(IC8-INP)") (class "Default")
      (node (ref "C30") (pin "1") (pinfunction "1_1") (pintype "passive"))
      (node (ref "IC8") (pin "2") (pinfunction "INP_2") (pintype "input"))
      (node (ref "R49") (pin "2") (pinfunction "2_2") (pintype "passive"))
    )
    (net (code "100") (name "Net-(IC8-VP)") (class "Default")
      (node (ref "C32") (pin "1") (pinfunction "1_1") (pintype "passive"))
      (node (ref "IC8") (pin "4") (pinfunction "VP_4") (pintype "input"))
      (node (ref "R55") (pin "2") (pinfunction "2_2") (pintype "passive"))
      (node (ref "R56") (pin "1") (pinfunction "1_1") (pintype "passive"))
    )
    (net (code "101") (name "Net-(IC10-INN)") (class "Default")
      (node (ref "C37") (pin "1") (pinfunction "1_1") (pintype "passive"))
      (node (ref "IC10") (pin "3") (pinfunction "INN_3") (pintype "input"))
      (node (ref "R66") (pin "2") (pinfunction "2_2") (pintype "passive"))
    )
    (net (code "102") (name "Net-(IC10-INP)") (class "Default")
      (node (ref "C36") (pin "1") (pinfunction "1_1") (pintype "passive"))
      (node (ref "IC10") (pin "2") (pinfunction "INP_2") (pintype "input"))
      (node (ref "R65") (pin "2") (pinfunction "2_2") (pintype "passive"))
    )
    (net (code "103") (name "Net-(IC10-VP)") (class "Default")
      (node (ref "C38") (pin "1") (pinfunction "1_1") (pintype "passive"))
      (node (ref "IC10") (pin "4") (pinfunction "VP_4") (pintype "input"))
      (node (ref "R71") (pin "2") (pinfunction "2_2") (pintype "passive"))
      (node (ref "R72") (pin "1") (pinfunction "1_1") (pintype "passive"))
    )
    (net (code "104") (name "Net-(IC11-INN)") (class "Default")
      (node (ref "C40") (pin "1") (pinfunction "1_1") (pintype "passive"))
      (node (ref "IC11") (pin "3") (pinfunction "INN_3") (pintype "input"))
      (node (ref "R74") (pin "2") (pinfunction "2_2") (pintype "passive"))
    )
    (net (code "105") (name "Net-(IC11-INP)") (class "Default")
      (node (ref "C39") (pin "1") (pinfunction "1_1") (pintype "passive"))
      (node (ref "IC11") (pin "2") (pinfunction "INP_2") (pintype "input"))
      (node (ref "R73") (pin "2") (pinfunction "2_2") (pintype "passive"))
    )
    (net (code "106") (name "Net-(IC11-VP)") (class "Default")
      (node (ref "C41") (pin "1") (pinfunction "1_1") (pintype "passive"))
      (node (ref "IC11") (pin "4") (pinfunction "VP_4") (pintype "input"))
      (node (ref "R79") (pin "2") (pinfunction "2_2") (pintype "passive"))
      (node (ref "R80") (pin "1") (pinfunction "1_1") (pintype "passive"))
    )
    (net (code "107") (name "Net-(IC12-INN)") (class "Default")
      (node (ref "C43") (pin "1") (pinfunction "1_1") (pintype "passive"))
      (node (ref "IC12") (pin "3") (pinfunction "INN_3") (pintype "input"))
      (node (ref "R82") (pin "2") (pinfunction "2_2") (pintype "passive"))
    )
    (net (code "108") (name "Net-(IC12-INP)") (class "Default")
      (node (ref "C42") (pin "1") (pinfunction "1_1") (pintype "passive"))
      (node (ref "IC12") (pin "2") (pinfunction "INP_2") (pintype "input"))
      (node (ref "R81") (pin "2") (pinfunction "2_2") (pintype "passive"))
    )
    (net (code "109") (name "Net-(IC12-VP)") (class "Default")
      (node (ref "C44") (pin "1") (pinfunction "1_1") (pintype "passive"))
      (node (ref "IC12") (pin "4") (pinfunction "VP_4") (pintype "input"))
      (node (ref "R87") (pin "2") (pinfunction "2_2") (pintype "passive"))
      (node (ref "R88") (pin "1") (pinfunction "1_1") (pintype "passive"))
    )
    (net (code "110") (name "Net-(IC14-INN)") (class "Default")
      (node (ref "C49") (pin "1") (pinfunction "1_1") (pintype "passive"))
      (node (ref "IC14") (pin "3") (pinfunction "INN_3") (pintype "input"))
      (node (ref "R98") (pin "2") (pinfunction "2_2") (pintype "passive"))
    )
    (net (code "111") (name "Net-(IC14-INP)") (class "Default")
      (node (ref "C48") (pin "1") (pinfunction "1_1") (pintype "passive"))
      (node (ref "IC14") (pin "2") (pinfunction "INP_2") (pintype "input"))
      (node (ref "R97") (pin "2") (pinfunction "2_2") (pintype "passive"))
    )
    (net (code "112") (name "Net-(IC14-VP)") (class "Default")
      (node (ref "C50") (pin "1") (pinfunction "1_1") (pintype "passive"))
      (node (ref "IC14") (pin "4") (pinfunction "VP_4") (pintype "input"))
      (node (ref "R103") (pin "2") (pinfunction "2_2") (pintype "passive"))
      (node (ref "R104") (pin "1") (pinfunction "1_1") (pintype "passive"))
    )
    (net (code "113") (name "Net-(IC15-GPIO28{slash}ADC2)") (class "Default")
      (node (ref "IC15") (pin "40") (pinfunction "GPIO28/ADC2_40") (pintype "bidirectional"))
      (node (ref "R163") (pin "2") (pinfunction "2_2") (pintype "passive"))
    )
    (net (code "114") (name "Net-(IC15-USB_DM)") (class "Default")
      (node (ref "IC15") (pin "46") (pinfunction "USB_DM_46") (pintype "bidirectional"))
      (node (ref "R15") (pin "2") (pinfunction "2_2") (pintype "passive"))
    )
    (net (code "115") (name "Net-(IC15-USB_DP)") (class "Default")
      (node (ref "IC15") (pin "47") (pinfunction "USB_DP_47") (pintype "bidirectional"))
      (node (ref "R160") (pin "2") (pinfunction "2_2") (pintype "passive"))
    )
    (net (code "116") (name "Net-(IC16-INN)") (class "Default")
      (node (ref "C55") (pin "1") (pinfunction "1_1") (pintype "passive"))
      (node (ref "IC16") (pin "3") (pinfunction "INN_3") (pintype "input"))
      (node (ref "R114") (pin "2") (pinfunction "2_2") (pintype "passive"))
    )
    (net (code "117") (name "Net-(IC16-INP)") (class "Default")
      (node (ref "C54") (pin "1") (pinfunction "1_1") (pintype "passive"))
      (node (ref "IC16") (pin "2") (pinfunction "INP_2") (pintype "input"))
      (node (ref "R113") (pin "2") (pinfunction "2_2") (pintype "passive"))
    )
    (net (code "118") (name "Net-(IC16-VP)") (class "Default")
      (node (ref "C56") (pin "1") (pinfunction "1_1") (pintype "passive"))
      (node (ref "IC16") (pin "4") (pinfunction "VP_4") (pintype "input"))
      (node (ref "R119") (pin "2") (pinfunction "2_2") (pintype "passive"))
      (node (ref "R120") (pin "1") (pinfunction "1_1") (pintype "passive"))
    )
    (net (code "119") (name "Net-(IC17-+IN)") (class "Default")
      (node (ref "C60") (pin "1") (pinfunction "1_1") (pintype "passive"))
      (node (ref "C61") (pin "1") (pinfunction "1_1") (pintype "passive"))
      (node (ref "IC17") (pin "3") (pinfunction "+IN_3") (pintype "input"))
      (node (ref "R109") (pin "1") (pinfunction "1_1") (pintype "passive"))
      (node (ref "REF1") (pin "1") (pinfunction "C_1") (pintype "passive"))
      (node (ref "VREF") (pin "TP") (pinfunction "P$1_TP") (pintype "bidirectional"))
    )
    (net (code "120") (name "Net-(IC19-A0)") (class "Default")
      (node (ref "IC19") (pin "1") (pinfunction "A0_1") (pintype "bidirectional"))
      (node (ref "R128") (pin "1") (pinfunction "1_1") (pintype "passive"))
      (node (ref "R129") (pin "2") (pinfunction "2_2") (pintype "passive"))
    )
    (net (code "121") (name "Net-(IC20-1V2O)") (class "Default")
      (node (ref "C84") (pin "1") (pinfunction "1_1") (pintype "passive"))
      (node (ref "IC20") (pin "22") (pinfunction "1V2O_22") (pintype "output"))
    )
    (net (code "122") (name "Net-(IC20-EXRES1)") (class "Default")
      (node (ref "IC20") (pin "10") (pinfunction "EXRES1_10") (pintype "bidirectional"))
      (node (ref "R143") (pin "2") (pinfunction "2_2") (pintype "passive"))
    )
    (net (code "123") (name "Net-(IC20-TOCAP)") (class "Default")
      (node (ref "C85") (pin "1") (pinfunction "1_1") (pintype "passive"))
      (node (ref "IC20") (pin "20") (pinfunction "TOCAP_20") (pintype "output"))
    )
    (net (code "124") (name "Net-(IC20-XI)") (class "Default")
      (node (ref "C87") (pin "1") (pinfunction "1_1") (pintype "passive"))
      (node (ref "IC20") (pin "30") (pinfunction "XI_30") (pintype "input"))
      (node (ref "R144") (pin "1") (pinfunction "1_1") (pintype "passive"))
      (node (ref "X2") (pin "3") (pinfunction "2_3") (pintype "passive"))
    )
    (net (code "125") (name "Net-(IC20-XO)") (class "Default")
      (node (ref "C86") (pin "1") (pinfunction "1_1") (pintype "passive"))
      (node (ref "IC20") (pin "31") (pinfunction "XO_31") (pintype "output"))
      (node (ref "R144") (pin "2") (pinfunction "2_2") (pintype "passive"))
      (node (ref "X2") (pin "1") (pinfunction "1_1") (pintype "passive"))
    )
    (net (code "126") (name "Net-(IC22--IN)") (class "Default")
      (node (ref "IC22") (pin "1") (pinfunction "OUT_1") (pintype "output"))
      (node (ref "IC22") (pin "4") (pinfunction "-IN_4") (pintype "input"))
      (node (ref "R122") (pin "1") (pinfunction "1_1") (pintype "passive"))
    )
    (net (code "127") (name "Net-(P3ON-PadA)") (class "Default")
      (node (ref "P3ON") (pin "A") (pinfunction "A_A") (pintype "passive"))
      (node (ref "R123") (pin "2") (pinfunction "2_2") (pintype "passive"))
    )
    (net (code "128") (name "Net-(P5ON-PadA)") (class "Default")
      (node (ref "P5ON") (pin "A") (pinfunction "A_A") (pintype "passive"))
      (node (ref "R148") (pin "2") (pinfunction "2_2") (pintype "passive"))
    )
    (net (code "129") (name "Net-(P12ON-PadA)") (class "Default")
      (node (ref "P12ON") (pin "A") (pinfunction "A_A") (pintype "passive"))
      (node (ref "R150") (pin "2") (pinfunction "2_2") (pintype "passive"))
    )
    (net (code "130") (name "Net-(PROC-PadA)") (class "Default")
      (node (ref "PROC") (pin "A") (pinfunction "A_A") (pintype "passive"))
      (node (ref "R163") (pin "1") (pinfunction "1_1") (pintype "passive"))
    )
    (net (code "131") (name "Net-(PWR-PadC)") (class "Default")
      (node (ref "PWR") (pin "C") (pinfunction "C_C") (pintype "passive"))
      (node (ref "R151") (pin "2") (pinfunction "2_2") (pintype "passive"))
    )
    (net (code "132") (name "Net-(R36-Pad1)") (class "Default")
      (node (ref "R36") (pin "1") (pinfunction "1_1") (pintype "passive"))
      (node (ref "R37") (pin "2") (pinfunction "2_2") (pintype "passive"))
    )
    (net (code "133") (name "Net-(R37-Pad1)") (class "Default")
      (node (ref "R37") (pin "1") (pinfunction "1_1") (pintype "passive"))
      (node (ref "R38") (pin "1") (pinfunction "1_1") (pintype "passive"))
    )
    (net (code "134") (name "Net-(R38-Pad2)") (class "Default")
      (node (ref "R38") (pin "2") (pinfunction "2_2") (pintype "passive"))
      (node (ref "R39") (pin "1") (pinfunction "1_1") (pintype "passive"))
    )
    (net (code "135") (name "Net-(R44-Pad2)") (class "Default")
      (node (ref "R44") (pin "2") (pinfunction "2_2") (pintype "passive"))
      (node (ref "R45") (pin "2") (pinfunction "2_2") (pintype "passive"))
    )
    (net (code "136") (name "Net-(R45-Pad1)") (class "Default")
      (node (ref "R45") (pin "1") (pinfunction "1_1") (pintype "passive"))
      (node (ref "R46") (pin "1") (pinfunction "1_1") (pintype "passive"))
    )
    (net (code "137") (name "Net-(R46-Pad2)") (class "Default")
      (node (ref "R46") (pin "2") (pinfunction "2_2") (pintype "passive"))
      (node (ref "R47") (pin "1") (pinfunction "1_1") (pintype "passive"))
    )
    (net (code "138") (name "Net-(R52-Pad2)") (class "Default")
      (node (ref "R52") (pin "2") (pinfunction "2_2") (pintype "passive"))
      (node (ref "R53") (pin "2") (pinfunction "2_2") (pintype "passive"))
    )
    (net (code "139") (name "Net-(R53-Pad1)") (class "Default")
      (node (ref "R53") (pin "1") (pinfunction "1_1") (pintype "passive"))
      (node (ref "R54") (pin "1") (pinfunction "1_1") (pintype "passive"))
    )
    (net (code "140") (name "Net-(R54-Pad2)") (class "Default")
      (node (ref "R54") (pin "2") (pinfunction "2_2") (pintype "passive"))
      (node (ref "R55") (pin "1") (pinfunction "1_1") (pintype "passive"))
    )
    (net (code "141") (name "Net-(R57-Pad1)") (class "Default")
      (node (ref "R57") (pin "1") (pinfunction "1_1") (pintype "passive"))
      (node (ref "R58") (pin "1") (pinfunction "1_1") (pintype "passive"))
      (node (ref "R91") (pin "2") (pinfunction "2_2") (pintype "passive"))
      (node (ref "R92") (pin "2") (pinfunction "2_2") (pintype "passive"))
    )
    (net (code "142") (name "Net-(R63-5)") (class "Default")
      (node (ref "OPT1") (pin "7") (pinfunction "7_7") (pintype "passive"))
      (node (ref "R63") (pin "D2") (pinfunction "5_D2") (pintype "passive"))
    )
    (net (code "143") (name "Net-(R63-6)") (class "Default")
      (node (ref "OPT1") (pin "5") (pinfunction "5_5") (pintype "passive"))
      (node (ref "R63") (pin "C2") (pinfunction "6_C2") (pintype "passive"))
    )
    (net (code "144") (name "Net-(R63-7)") (class "Default")
      (node (ref "OPT1") (pin "3") (pinfunction "3_3") (pintype "passive"))
      (node (ref "R63") (pin "B2") (pinfunction "7_B2") (pintype "passive"))
    )
    (net (code "145") (name "Net-(R63-8)") (class "Default")
      (node (ref "OPT1") (pin "1") (pinfunction "1_1") (pintype "passive"))
      (node (ref "R63") (pin "A2") (pinfunction "8_A2") (pintype "passive"))
    )
    (net (code "146") (name "Net-(R64-5)") (class "Default")
      (node (ref "OPT2") (pin "7") (pinfunction "7_7") (pintype "passive"))
      (node (ref "R64") (pin "D2") (pinfunction "5_D2") (pintype "passive"))
    )
    (net (code "147") (name "Net-(R64-6)") (class "Default")
      (node (ref "OPT2") (pin "5") (pinfunction "5_5") (pintype "passive"))
      (node (ref "R64") (pin "C2") (pinfunction "6_C2") (pintype "passive"))
    )
    (net (code "148") (name "Net-(R64-7)") (class "Default")
      (node (ref "OPT2") (pin "3") (pinfunction "3_3") (pintype "passive"))
      (node (ref "R64") (pin "B2") (pinfunction "7_B2") (pintype "passive"))
    )
    (net (code "149") (name "Net-(R64-8)") (class "Default")
      (node (ref "OPT2") (pin "1") (pinfunction "1_1") (pintype "passive"))
      (node (ref "R64") (pin "A2") (pinfunction "8_A2") (pintype "passive"))
    )
    (net (code "150") (name "Net-(R68-Pad2)") (class "Default")
      (node (ref "R68") (pin "2") (pinfunction "2_2") (pintype "passive"))
      (node (ref "R69") (pin "2") (pinfunction "2_2") (pintype "passive"))
    )
    (net (code "151") (name "Net-(R69-Pad1)") (class "Default")
      (node (ref "R69") (pin "1") (pinfunction "1_1") (pintype "passive"))
      (node (ref "R70") (pin "1") (pinfunction "1_1") (pintype "passive"))
    )
    (net (code "152") (name "Net-(R70-Pad2)") (class "Default")
      (node (ref "R70") (pin "2") (pinfunction "2_2") (pintype "passive"))
      (node (ref "R71") (pin "1") (pinfunction "1_1") (pintype "passive"))
    )
    (net (code "153") (name "Net-(R76-Pad2)") (class "Default")
      (node (ref "R76") (pin "2") (pinfunction "2_2") (pintype "passive"))
      (node (ref "R77") (pin "2") (pinfunction "2_2") (pintype "passive"))
    )
    (net (code "154") (name "Net-(R77-Pad1)") (class "Default")
      (node (ref "R77") (pin "1") (pinfunction "1_1") (pintype "passive"))
      (node (ref "R78") (pin "1") (pinfunction "1_1") (pintype "passive"))
    )
    (net (code "155") (name "Net-(R78-Pad2)") (class "Default")
      (node (ref "R78") (pin "2") (pinfunction "2_2") (pintype "passive"))
      (node (ref "R79") (pin "1") (pinfunction "1_1") (pintype "passive"))
    )
    (net (code "156") (name "Net-(R84-Pad2)") (class "Default")
      (node (ref "R84") (pin "2") (pinfunction "2_2") (pintype "passive"))
      (node (ref "R85") (pin "2") (pinfunction "2_2") (pintype "passive"))
    )
    (net (code "157") (name "Net-(R85-Pad1)") (class "Default")
      (node (ref "R85") (pin "1") (pinfunction "1_1") (pintype "passive"))
      (node (ref "R86") (pin "1") (pinfunction "1_1") (pintype "passive"))
    )
    (net (code "158") (name "Net-(R86-Pad2)") (class "Default")
      (node (ref "R86") (pin "2") (pinfunction "2_2") (pintype "passive"))
      (node (ref "R87") (pin "1") (pinfunction "1_1") (pintype "passive"))
    )
    (net (code "159") (name "Net-(R100-Pad2)") (class "Default")
      (node (ref "R100") (pin "2") (pinfunction "2_2") (pintype "passive"))
      (node (ref "R101") (pin "2") (pinfunction "2_2") (pintype "passive"))
    )
    (net (code "160") (name "Net-(R101-Pad1)") (class "Default")
      (node (ref "R101") (pin "1") (pinfunction "1_1") (pintype "passive"))
      (node (ref "R102") (pin "1") (pinfunction "1_1") (pintype "passive"))
    )
    (net (code "161") (name "Net-(R102-Pad2)") (class "Default")
      (node (ref "R102") (pin "2") (pinfunction "2_2") (pintype "passive"))
      (node (ref "R103") (pin "1") (pinfunction "1_1") (pintype "passive"))
    )
    (net (code "162") (name "Net-(R116-Pad2)") (class "Default")
      (node (ref "R116") (pin "2") (pinfunction "2_2") (pintype "passive"))
      (node (ref "R117") (pin "2") (pinfunction "2_2") (pintype "passive"))
    )
    (net (code "163") (name "Net-(R117-Pad1)") (class "Default")
      (node (ref "R117") (pin "1") (pinfunction "1_1") (pintype "passive"))
      (node (ref "R118") (pin "1") (pinfunction "1_1") (pintype "passive"))
    )
    (net (code "164") (name "Net-(R118-Pad2)") (class "Default")
      (node (ref "R118") (pin "2") (pinfunction "2_2") (pintype "passive"))
      (node (ref "R119") (pin "1") (pinfunction "1_1") (pintype "passive"))
    )
    (net (code "165") (name "Net-(X1-2)") (class "Default")
      (node (ref "C59") (pin "1") (pinfunction "1_1") (pintype "passive"))
      (node (ref "R16") (pin "1") (pinfunction "1_1") (pintype "passive"))
      (node (ref "X1") (pin "3") (pinfunction "2_3") (pintype "passive"))
    )
    (net (code "166") (name "OUT_1") (class "Default")
      (node (ref "K1") (pin "4") (pinfunction "4_4") (pintype "passive"))
      (node (ref "K1") (pin "5") (pinfunction "5_5") (pintype "passive"))
      (node (ref "L_OUT1") (pin "B2,8") (pinfunction "MOUNT_B2,8") (pintype "passive"))
      (node (ref "R36") (pin "2") (pinfunction "2_2") (pintype "passive"))
    )
    (net (code "167") (name "OUT_2") (class "Default")
      (node (ref "K2") (pin "4") (pinfunction "4_4") (pintype "passive"))
      (node (ref "K2") (pin "5") (pinfunction "5_5") (pintype "passive"))
      (node (ref "L_OUT2") (pin "B2,8") (pinfunction "MOUNT_B2,8") (pintype "passive"))
      (node (ref "R52") (pin "1") (pinfunction "1_1") (pintype "passive"))
    )
    (net (code "168") (name "OUT_3") (class "Default")
      (node (ref "K3") (pin "4") (pinfunction "4_4") (pintype "passive"))
      (node (ref "K3") (pin "5") (pinfunction "5_5") (pintype "passive"))
      (node (ref "L_OUT3") (pin "B2,8") (pinfunction "MOUNT_B2,8") (pintype "passive"))
      (node (ref "R68") (pin "1") (pinfunction "1_1") (pintype "passive"))
    )
    (net (code "169") (name "OUT_4") (class "Default")
      (node (ref "K4") (pin "4") (pinfunction "4_4") (pintype "passive"))
      (node (ref "K4") (pin "5") (pinfunction "5_5") (pintype "passive"))
      (node (ref "L_OUT4") (pin "B2,8") (pinfunction "MOUNT_B2,8") (pintype "passive"))
      (node (ref "R84") (pin "1") (pinfunction "1_1") (pintype "passive"))
    )
    (net (code "170") (name "OUT_5") (class "Default")
      (node (ref "K5") (pin "4") (pinfunction "4_4") (pintype "passive"))
      (node (ref "K5") (pin "5") (pinfunction "5_5") (pintype "passive"))
      (node (ref "L_OUT5") (pin "B2,8") (pinfunction "MOUNT_B2,8") (pintype "passive"))
      (node (ref "R44") (pin "1") (pinfunction "1_1") (pintype "passive"))
    )
    (net (code "171") (name "OUT_6") (class "Default")
      (node (ref "K6") (pin "4") (pinfunction "4_4") (pintype "passive"))
      (node (ref "K6") (pin "5") (pinfunction "5_5") (pintype "passive"))
      (node (ref "L_OUT6") (pin "B2,8") (pinfunction "MOUNT_B2,8") (pintype "passive"))
      (node (ref "R76") (pin "1") (pinfunction "1_1") (pintype "passive"))
    )
    (net (code "172") (name "OUT_7") (class "Default")
      (node (ref "K7") (pin "4") (pinfunction "4_4") (pintype "passive"))
      (node (ref "K7") (pin "5") (pinfunction "5_5") (pintype "passive"))
      (node (ref "L_OUT7") (pin "B2,8") (pinfunction "MOUNT_B2,8") (pintype "passive"))
      (node (ref "R100") (pin "1") (pinfunction "1_1") (pintype "passive"))
    )
    (net (code "173") (name "OUT_8") (class "Default")
      (node (ref "K8") (pin "4") (pinfunction "4_4") (pintype "passive"))
      (node (ref "K8") (pin "5") (pinfunction "5_5") (pintype "passive"))
      (node (ref "L_OUT8") (pin "B2,8") (pinfunction "MOUNT_B2,8") (pintype "passive"))
      (node (ref "R116") (pin "1") (pinfunction "1_1") (pintype "passive"))
    )
    (net (code "174") (name "QSPI_SCLK") (class "Default")
      (node (ref "IC15") (pin "52") (pinfunction "QSPI_SCLK_52") (pintype "bidirectional"))
      (node (ref "IC18") (pin "6") (pinfunction "CLK_6") (pintype "bidirectional"))
    )
    (net (code "175") (name "QSPI_SD0") (class "Default")
      (node (ref "IC15") (pin "53") (pinfunction "QSPI_SD0_53") (pintype "bidirectional"))
      (node (ref "IC18") (pin "5") (pinfunction "DI/IO0_5") (pintype "bidirectional"))
    )
    (net (code "176") (name "QSPI_SD1") (class "Default")
      (node (ref "IC15") (pin "55") (pinfunction "QSPI_SD1_55") (pintype "bidirectional"))
      (node (ref "IC18") (pin "2") (pinfunction "DO/IO1_2") (pintype "bidirectional"))
    )
    (net (code "177") (name "QSPI_SD2") (class "Default")
      (node (ref "IC15") (pin "54") (pinfunction "QSPI_SD2_54") (pintype "bidirectional"))
      (node (ref "IC18") (pin "3") (pinfunction "~{WP}/IO2_3") (pintype "bidirectional"))
    )
    (net (code "178") (name "QSPI_SD3") (class "Default")
      (node (ref "IC15") (pin "51") (pinfunction "QSPI_SD3_51") (pintype "bidirectional"))
      (node (ref "IC18") (pin "7") (pinfunction "~{HOLD}/IO3_7") (pintype "bidirectional"))
    )
    (net (code "179") (name "RCT") (class "Default")
      (node (ref "C79") (pin "1") (pinfunction "1_1") (pintype "passive"))
      (node (ref "ETH1") (pin "5") (pinfunction "P5/RCT_5") (pintype "passive"))
      (node (ref "R137") (pin "1") (pinfunction "1_1") (pintype "passive"))
      (node (ref "R138") (pin "1") (pinfunction "1_1") (pintype "passive"))
    )
    (net (code "180") (name "RDC_RD_N") (class "Default")
      (node (ref "C81") (pin "1") (pinfunction "1_1") (pintype "passive"))
      (node (ref "R136") (pin "2") (pinfunction "2_2") (pintype "passive"))
      (node (ref "R137") (pin "2") (pinfunction "2_2") (pintype "passive"))
    )
    (net (code "181") (name "RDC_RD_P") (class "Default")
      (node (ref "C82") (pin "1") (pinfunction "1_1") (pintype "passive"))
      (node (ref "R135") (pin "2") (pinfunction "2_2") (pintype "passive"))
      (node (ref "R138") (pin "2") (pinfunction "2_2") (pintype "passive"))
    )
    (net (code "182") (name "RD_N") (class "Default")
      (node (ref "C81") (pin "2") (pinfunction "2_2") (pintype "passive"))
      (node (ref "ETH1") (pin "6") (pinfunction "RD-_6") (pintype "passive"))
    )
    (net (code "183") (name "RD_P") (class "Default")
      (node (ref "C82") (pin "2") (pinfunction "2_2") (pintype "passive"))
      (node (ref "ETH1") (pin "4") (pinfunction "RD+_4") (pintype "passive"))
    )
    (net (code "184") (name "RELAY_1") (class "Default")
      (node (ref "D1") (pin "A") (pinfunction "A_A") (pintype "passive"))
      (node (ref "K1") (pin "1") (pinfunction "1_1") (pintype "passive"))
      (node (ref "R24") (pin "2") (pinfunction "2_2") (pintype "passive"))
    )
    (net (code "185") (name "RELAY_2") (class "Default")
      (node (ref "D2") (pin "A") (pinfunction "A_A") (pintype "passive"))
      (node (ref "K2") (pin "1") (pinfunction "1_1") (pintype "passive"))
      (node (ref "R23") (pin "2") (pinfunction "2_2") (pintype "passive"))
    )
    (net (code "186") (name "RELAY_3") (class "Default")
      (node (ref "D3") (pin "A") (pinfunction "A_A") (pintype "passive"))
      (node (ref "K3") (pin "1") (pinfunction "1_1") (pintype "passive"))
      (node (ref "R22") (pin "2") (pinfunction "2_2") (pintype "passive"))
    )
    (net (code "187") (name "RELAY_4") (class "Default")
      (node (ref "D4") (pin "A") (pinfunction "A_A") (pintype "passive"))
      (node (ref "K4") (pin "1") (pinfunction "1_1") (pintype "passive"))
      (node (ref "R21") (pin "2") (pinfunction "2_2") (pintype "passive"))
    )
    (net (code "188") (name "RELAY_5") (class "Default")
      (node (ref "D5") (pin "A") (pinfunction "A_A") (pintype "passive"))
      (node (ref "K5") (pin "1") (pinfunction "1_1") (pintype "passive"))
      (node (ref "R20") (pin "2") (pinfunction "2_2") (pintype "passive"))
    )
    (net (code "189") (name "RELAY_6") (class "Default")
      (node (ref "D6") (pin "A") (pinfunction "A_A") (pintype "passive"))
      (node (ref "K6") (pin "1") (pinfunction "1_1") (pintype "passive"))
      (node (ref "R19") (pin "2") (pinfunction "2_2") (pintype "passive"))
    )
    (net (code "190") (name "RELAY_7") (class "Default")
      (node (ref "D7") (pin "A") (pinfunction "A_A") (pintype "passive"))
      (node (ref "K7") (pin "1") (pinfunction "1_1") (pintype "passive"))
      (node (ref "R18") (pin "2") (pinfunction "2_2") (pintype "passive"))
    )
    (net (code "191") (name "RELAY_8") (class "Default")
      (node (ref "D8") (pin "A") (pinfunction "A_A") (pintype "passive"))
      (node (ref "K8") (pin "1") (pinfunction "1_1") (pintype "passive"))
      (node (ref "R17") (pin "2") (pinfunction "2_2") (pintype "passive"))
    )
    (net (code "192") (name "REL_0") (class "Default")
      (node (ref "IC3") (pin "8") (pinfunction "8B_8") (pintype "bidirectional"))
      (node (ref "IC4") (pin "17") (pinfunction "IO1.0_17") (pintype "bidirectional"))
    )
    (net (code "193") (name "REL_1") (class "Default")
      (node (ref "IC3") (pin "7") (pinfunction "7B_7") (pintype "bidirectional"))
      (node (ref "IC4") (pin "18") (pinfunction "IO1.1_18") (pintype "bidirectional"))
    )
    (net (code "194") (name "REL_2") (class "Default")
      (node (ref "IC3") (pin "6") (pinfunction "6B_6") (pintype "bidirectional"))
      (node (ref "IC4") (pin "19") (pinfunction "IO1.2_19") (pintype "bidirectional"))
    )
    (net (code "195") (name "REL_3") (class "Default")
      (node (ref "IC3") (pin "5") (pinfunction "5B_5") (pintype "bidirectional"))
      (node (ref "IC4") (pin "20") (pinfunction "IO1.3_20") (pintype "bidirectional"))
    )
    (net (code "196") (name "REL_4") (class "Default")
      (node (ref "IC3") (pin "4") (pinfunction "4B_4") (pintype "bidirectional"))
      (node (ref "IC4") (pin "21") (pinfunction "IO1.4_21") (pintype "bidirectional"))
    )
    (net (code "197") (name "REL_5") (class "Default")
      (node (ref "IC3") (pin "3") (pinfunction "3B_3") (pintype "bidirectional"))
      (node (ref "IC4") (pin "22") (pinfunction "IO1.5_22") (pintype "bidirectional"))
    )
    (net (code "198") (name "REL_6") (class "Default")
      (node (ref "IC3") (pin "2") (pinfunction "2B_2") (pintype "bidirectional"))
      (node (ref "IC4") (pin "23") (pinfunction "IO1.6_23") (pintype "bidirectional"))
    )
    (net (code "199") (name "REL_7") (class "Default")
      (node (ref "IC3") (pin "1") (pinfunction "1B_1") (pintype "bidirectional"))
      (node (ref "IC4") (pin "24") (pinfunction "IO1.7_24") (pintype "bidirectional"))
    )
    (net (code "200") (name "RP_XI") (class "Default")
      (node (ref "C58") (pin "1") (pinfunction "1_1") (pintype "passive"))
      (node (ref "IC15") (pin "20") (pinfunction "XIN_20") (pintype "bidirectional"))
      (node (ref "X1") (pin "1") (pinfunction "1_1") (pintype "passive"))
    )
    (net (code "201") (name "RP_XO") (class "Default")
      (node (ref "IC15") (pin "21") (pinfunction "XOUT_21") (pintype "bidirectional"))
      (node (ref "R16") (pin "2") (pinfunction "2_2") (pintype "passive"))
    )
    (net (code "202") (name "RUN") (class "Default")
      (node (ref "GDGC") (pin "2") (pinfunction "P$2_2") (pintype "bidirectional"))
      (node (ref "IC15") (pin "26") (pinfunction "RUN_26") (pintype "bidirectional"))
      (node (ref "R132") (pin "2") (pinfunction "2_2") (pintype "passive"))
      (node (ref "RESET") (pin "2") (pinfunction "P$2_2") (pintype "bidirectional"))
    )
    (net (code "203") (name "RX_RD_N") (class "Default")
      (node (ref "IC20") (pin "5") (pinfunction "RXN_5") (pintype "input"))
      (node (ref "R136") (pin "1") (pinfunction "1_1") (pintype "passive"))
    )
    (net (code "204") (name "RX_RD_P") (class "Default")
      (node (ref "IC20") (pin "6") (pinfunction "RXP_6") (pintype "input"))
      (node (ref "R135") (pin "1") (pinfunction "1_1") (pintype "passive"))
    )
    (net (code "205") (name "SH") (class "Default")
      (node (ref "C78") (pin "1") (pinfunction "1_1") (pintype "passive"))
      (node (ref "C83") (pin "2") (pinfunction "2_2") (pintype "passive"))
      (node (ref "ETH1") (pin "13") (pinfunction "SHIELD_13") (pintype "passive"))
      (node (ref "ETH1") (pin "14") (pinfunction "SHIELD_14") (pintype "passive"))
      (node (ref "R110") (pin "2") (pinfunction "2_2") (pintype "passive"))
      (node (ref "R131") (pin "1") (pinfunction "1_1") (pintype "passive"))
      (node (ref "USB1") (pin "SHLD1") (pinfunction "SHILED_SHLD1") (pintype "power_in"))
      (node (ref "USB1") (pin "SHLD2") (pinfunction "SHILED_SHLD2") (pintype "power_in"))
      (node (ref "USB1") (pin "SHLD3") (pinfunction "SHILED_SHLD3") (pintype "power_in"))
      (node (ref "USB1") (pin "SHLD4") (pinfunction "SHILED_SHLD4") (pintype "power_in"))
    )
    (net (code "206") (name "SRC1") (class "Default")
      (node (ref "C21") (pin "1") (pinfunction "1_1") (pintype "passive"))
      (node (ref "C22") (pin "1") (pinfunction "1_1") (pintype "passive"))
      (node (ref "C5") (pin "1") (pinfunction "1_1") (pintype "passive"))
      (node (ref "D11") (pin "C") (pinfunction "C_C") (pintype "passive"))
      (node (ref "IC13") (pin "3") (pinfunction "SRC2_3") (pintype "output"))
      (node (ref "IC13") (pin "4") (pinfunction "SRC_4") (pintype "output"))
      (node (ref "L3") (pin "1") (pinfunction "1_1") (pintype "passive"))
      (node (ref "R60") (pin "2") (pinfunction "2_2") (pintype "passive"))
    )
    (net (code "207") (name "SRC2") (class "Default")
      (node (ref "C46") (pin "1") (pinfunction "1_1") (pintype "passive"))
      (node (ref "C51") (pin "1") (pinfunction "1_1") (pintype "passive"))
      (node (ref "C52") (pin "1") (pinfunction "1_1") (pintype "passive"))
      (node (ref "D14") (pin "C") (pinfunction "C_C") (pintype "passive"))
      (node (ref "IC5") (pin "3") (pinfunction "SRC2_3") (pintype "output"))
      (node (ref "IC5") (pin "4") (pinfunction "SRC_4") (pintype "output"))
      (node (ref "L5") (pin "1") (pinfunction "1_1") (pintype "passive"))
      (node (ref "R107") (pin "2") (pinfunction "2_2") (pintype "passive"))
    )
    (net (code "208") (name "SWCLK") (class "Default")
      (node (ref "GDGC") (pin "1") (pinfunction "P$1_1") (pintype "bidirectional"))
      (node (ref "IC15") (pin "24") (pinfunction "SWCLK_24") (pintype "bidirectional"))
    )
    (net (code "209") (name "SWDIO") (class "Default")
      (node (ref "GDGC") (pin "3") (pinfunction "P$3_3") (pintype "bidirectional"))
      (node (ref "IC15") (pin "25") (pinfunction "SWDIO_25") (pintype "bidirectional"))
    )
    (net (code "210") (name "TCT") (class "Default")
      (node (ref "C80") (pin "1") (pinfunction "1_1") (pintype "passive"))
      (node (ref "ETH1") (pin "2") (pinfunction "P4/TCT_2") (pintype "passive"))
      (node (ref "R146") (pin "1") (pinfunction "1_1") (pintype "passive"))
    )
    (net (code "211") (name "TD_N") (class "Default")
      (node (ref "ETH1") (pin "3") (pinfunction "TD-_3") (pintype "passive"))
      (node (ref "R134") (pin "2") (pinfunction "2_2") (pintype "passive"))
      (node (ref "R140") (pin "1") (pinfunction "1_1") (pintype "passive"))
    )
    (net (code "212") (name "TD_P") (class "Default")
      (node (ref "ETH1") (pin "1") (pinfunction "TD+_1") (pintype "passive"))
      (node (ref "R133") (pin "2") (pinfunction "2_2") (pintype "passive"))
      (node (ref "R139") (pin "1") (pinfunction "1_1") (pintype "passive"))
    )
    (net (code "213") (name "TX_CH1") (class "Default")
      (node (ref "IC6") (pin "6") (pinfunction "TX_6") (pintype "bidirectional"))
      (node (ref "R155") (pin "1") (pinfunction "1_1") (pintype "passive"))
    )
    (net (code "214") (name "TX_CH2") (class "Default")
      (node (ref "IC8") (pin "6") (pinfunction "TX_6") (pintype "bidirectional"))
      (node (ref "R154") (pin "1") (pinfunction "1_1") (pintype "passive"))
    )
    (net (code "215") (name "TX_CH3") (class "Default")
      (node (ref "IC10") (pin "6") (pinfunction "TX_6") (pintype "bidirectional"))
      (node (ref "R153") (pin "1") (pinfunction "1_1") (pintype "passive"))
    )
    (net (code "216") (name "TX_CH4") (class "Default")
      (node (ref "IC12") (pin "6") (pinfunction "TX_6") (pintype "bidirectional"))
      (node (ref "R59") (pin "1") (pinfunction "1_1") (pintype "passive"))
    )
    (net (code "217") (name "TX_CH5") (class "Default")
      (node (ref "IC7") (pin "6") (pinfunction "TX_6") (pintype "bidirectional"))
      (node (ref "R159") (pin "1") (pinfunction "1_1") (pintype "passive"))
    )
    (net (code "218") (name "TX_CH6") (class "Default")
      (node (ref "IC11") (pin "6") (pinfunction "TX_6") (pintype "bidirectional"))
      (node (ref "R158") (pin "1") (pinfunction "1_1") (pintype "passive"))
    )
    (net (code "219") (name "TX_CH7") (class "Default")
      (node (ref "IC14") (pin "6") (pinfunction "TX_6") (pintype "bidirectional"))
      (node (ref "R157") (pin "1") (pinfunction "1_1") (pintype "passive"))
    )
    (net (code "220") (name "TX_CH8") (class "Default")
      (node (ref "IC16") (pin "6") (pinfunction "TX_6") (pintype "bidirectional"))
      (node (ref "R156") (pin "1") (pinfunction "1_1") (pintype "passive"))
    )
    (net (code "221") (name "TX_MUX1") (class "Default")
      (node (ref "IC9") (pin "4") (pinfunction "D0_4") (pintype "bidirectional"))
      (node (ref "OPT1") (pin "10") (pinfunction "10_10") (pintype "passive"))
      (node (ref "R89") (pin "D1") (pinfunction "4_D1") (pintype "passive"))
    )
    (net (code "222") (name "TX_MUX2") (class "Default")
      (node (ref "IC9") (pin "3") (pinfunction "D1_3") (pintype "bidirectional"))
      (node (ref "OPT1") (pin "12") (pinfunction "12_12") (pintype "passive"))
      (node (ref "R89") (pin "C1") (pinfunction "3_C1") (pintype "passive"))
    )
    (net (code "223") (name "TX_MUX3") (class "Default")
      (node (ref "IC9") (pin "2") (pinfunction "D2_2") (pintype "bidirectional"))
      (node (ref "OPT1") (pin "14") (pinfunction "14_14") (pintype "passive"))
      (node (ref "R89") (pin "B1") (pinfunction "2_B1") (pintype "passive"))
    )
    (net (code "224") (name "TX_MUX4") (class "Default")
      (node (ref "IC9") (pin "1") (pinfunction "D3_1") (pintype "bidirectional"))
      (node (ref "OPT1") (pin "16") (pinfunction "16_16") (pintype "passive"))
      (node (ref "R89") (pin "A1") (pinfunction "1_A1") (pintype "passive"))
    )
    (net (code "225") (name "TX_MUX5") (class "Default")
      (node (ref "IC9") (pin "15") (pinfunction "D4_15") (pintype "bidirectional"))
      (node (ref "OPT2") (pin "16") (pinfunction "16_16") (pintype "passive"))
      (node (ref "R90") (pin "A1") (pinfunction "1_A1") (pintype "passive"))
    )
    (net (code "226") (name "TX_MUX6") (class "Default")
      (node (ref "IC9") (pin "14") (pinfunction "D5_14") (pintype "bidirectional"))
      (node (ref "OPT2") (pin "14") (pinfunction "14_14") (pintype "passive"))
      (node (ref "R90") (pin "B1") (pinfunction "2_B1") (pintype "passive"))
    )
    (net (code "227") (name "TX_MUX7") (class "Default")
      (node (ref "IC9") (pin "13") (pinfunction "D6_13") (pintype "bidirectional"))
      (node (ref "OPT2") (pin "12") (pinfunction "12_12") (pintype "passive"))
      (node (ref "R90") (pin "C1") (pinfunction "3_C1") (pintype "passive"))
    )
    (net (code "228") (name "TX_MUX8") (class "Default")
      (node (ref "IC9") (pin "12") (pinfunction "D7_12") (pintype "bidirectional"))
      (node (ref "OPT2") (pin "10") (pinfunction "10_10") (pintype "passive"))
      (node (ref "R90") (pin "D1") (pinfunction "4_D1") (pintype "passive"))
    )
    (net (code "229") (name "TX_OUT") (class "Default")
      (node (ref "IC9") (pin "5") (pinfunction "Y_5") (pintype "bidirectional"))
      (node (ref "R91") (pin "1") (pinfunction "1_1") (pintype "passive"))
    )
    (net (code "230") (name "TX_TD_N") (class "Default")
      (node (ref "IC20") (pin "1") (pinfunction "TXN_1") (pintype "output"))
      (node (ref "R134") (pin "1") (pinfunction "1_1") (pintype "passive"))
    )
    (net (code "231") (name "TX_TD_P") (class "Default")
      (node (ref "IC20") (pin "2") (pinfunction "TXP_2") (pintype "output"))
      (node (ref "R133") (pin "1") (pinfunction "1_1") (pintype "passive"))
    )
    (net (code "232") (name "UART0_RX") (class "Default")
      (node (ref "IC15") (pin "2") (pinfunction "GPIO0_2") (pintype "bidirectional"))
      (node (ref "R58") (pin "2") (pinfunction "2_2") (pintype "passive"))
      (node (ref "RGTG") (pin "1") (pinfunction "P$1_1") (pintype "bidirectional"))
    )
    (net (code "233") (name "UART0_TX") (class "Default")
      (node (ref "IC15") (pin "3") (pinfunction "GPIO1_3") (pintype "bidirectional"))
      (node (ref "R57") (pin "2") (pinfunction "2_2") (pintype "passive"))
      (node (ref "RGTG") (pin "3") (pinfunction "P$3_3") (pintype "bidirectional"))
    )
    (net (code "234") (name "USB2_DP_N") (class "Default")
      (node (ref "ESD1") (pin "3") (pinfunction "C2_3") (pintype "bidirectional"))
      (node (ref "R15") (pin "1") (pinfunction "1_1") (pintype "passive"))
      (node (ref "USB1") (pin "A7") (pinfunction "D-_A7") (pintype "bidirectional"))
      (node (ref "USB1") (pin "B7") (pinfunction "D-_B7") (pintype "bidirectional"))
    )
    (net (code "235") (name "USB2_DP_P") (class "Default")
      (node (ref "ESD1") (pin "2") (pinfunction "C1_2") (pintype "bidirectional"))
      (node (ref "R160") (pin "1") (pinfunction "1_1") (pintype "passive"))
      (node (ref "USB1") (pin "A6") (pinfunction "D+_A6") (pintype "bidirectional"))
      (node (ref "USB1") (pin "B6") (pinfunction "D+_B6") (pintype "bidirectional"))
    )
    (net (code "236") (name "USB_BOOT") (class "Default")
      (node (ref "BOOT") (pin "1") (pinfunction "P$1_1") (pintype "bidirectional"))
      (node (ref "R112") (pin "1") (pinfunction "1_1") (pintype "passive"))
    )
    (net (code "237") (name "VBUS") (class "Default")
      (node (ref "C65") (pin "1") (pinfunction "1_1") (pintype "passive"))
      (node (ref "C66") (pin "1") (pinfunction "1_1") (pintype "passive"))
      (node (ref "C97") (pin "1") (pinfunction "1_1") (pintype "passive"))
      (node (ref "C98") (pin "1") (pinfunction "1_1") (pintype "passive"))
      (node (ref "D15") (pin "C") (pinfunction "C_C") (pintype "passive"))
      (node (ref "ESD1") (pin "4") (pinfunction "C3_4") (pintype "bidirectional"))
      (node (ref "IC21") (pin "1") (pinfunction "VIN_1") (pintype "bidirectional"))
      (node (ref "IC21") (pin "3") (pinfunction "EN_3") (pintype "bidirectional"))
      (node (ref "R121") (pin "1") (pinfunction "1_1") (pintype "passive"))
      (node (ref "R126") (pin "1") (pinfunction "1_1") (pintype "passive"))
      (node (ref "USB1") (pin "VBUS1") (pinfunction "VBUS_VBUS1") (pintype "power_in"))
      (node (ref "USB1") (pin "VBUS2") (pinfunction "VBUS_VBUS2") (pintype "power_in"))
      (node (ref "VBUS") (pin "TP") (pinfunction "P$1_TP") (pintype "bidirectional"))
    )
    (net (code "238") (name "VNI1") (class "Default")
      (node (ref "C21") (pin "2") (pinfunction "2_2") (pintype "passive"))
      (node (ref "IC13") (pin "1") (pinfunction "VCC_1") (pintype "output"))
      (node (ref "VNI1") (pin "TP") (pinfunction "P$1_TP") (pintype "bidirectional"))
    )
    (net (code "239") (name "VNI2") (class "Default")
      (node (ref "C46") (pin "2") (pinfunction "2_2") (pintype "passive"))
      (node (ref "IC5") (pin "1") (pinfunction "VCC_1") (pintype "output"))
      (node (ref "VNI2") (pin "TP") (pinfunction "P$1_TP") (pintype "bidirectional"))
    )
    (net (code "240") (name "W5500_MISO") (class "Default")
      (node (ref "IC15") (pin "27") (pinfunction "GPIO16_27") (pintype "bidirectional"))
      (node (ref "IC20") (pin "34") (pinfunction "MISO_34") (pintype "output"))
    )
    (net (code "241") (name "W5500_MOSI") (class "Default")
      (node (ref "IC15") (pin "30") (pinfunction "GPIO19_30") (pintype "bidirectional"))
      (node (ref "IC20") (pin "35") (pinfunction "MOSI_35") (pintype "input"))
    )
    (net (code "242") (name "W5500_SCK") (class "Default")
      (node (ref "IC15") (pin "29") (pinfunction "GPIO18_29") (pintype "bidirectional"))
      (node (ref "IC20") (pin "33") (pinfunction "SCLK_33") (pintype "input"))
    )
    (net (code "243") (name "unconnected-(IC4-INTA-Pad16)") (class "Default")
      (node (ref "IC4") (pin "16") (pinfunction "INTA_16") (pintype "bidirectional"))
    )
    (net (code "244") (name "unconnected-(IC4-INTB-Pad15)") (class "Default")
      (node (ref "IC4") (pin "15") (pinfunction "INTB_15") (pintype "bidirectional"))
    )
    (net (code "245") (name "unconnected-(IC4-IO2.4-Pad1)") (class "Default")
      (node (ref "IC4") (pin "1") (pinfunction "IO2.4_1") (pintype "bidirectional"))
    )
    (net (code "246") (name "unconnected-(IC4-IO2.5-Pad2)") (class "Default")
      (node (ref "IC4") (pin "2") (pinfunction "IO2.5_2") (pintype "bidirectional"))
    )
    (net (code "247") (name "unconnected-(IC4-IO2.6-Pad3)") (class "Default")
      (node (ref "IC4") (pin "3") (pinfunction "IO2.6_3") (pintype "bidirectional"))
    )
    (net (code "248") (name "unconnected-(IC4-IO2.7-Pad4)") (class "Default")
      (node (ref "IC4") (pin "4") (pinfunction "IO2.7_4") (pintype "bidirectional"))
    )
    (net (code "249") (name "unconnected-(IC6-PF-Pad7)") (class "Default")
      (node (ref "IC6") (pin "7") (pinfunction "PF_7") (pintype "bidirectional"))
    )
    (net (code "250") (name "unconnected-(IC6-RX-Pad8)") (class "Default")
      (node (ref "IC6") (pin "8") (pinfunction "RX_8") (pintype "bidirectional"))
    )
    (net (code "251") (name "unconnected-(IC7-PF-Pad7)") (class "Default")
      (node (ref "IC7") (pin "7") (pinfunction "PF_7") (pintype "bidirectional"))
    )
    (net (code "252") (name "unconnected-(IC7-RX-Pad8)") (class "Default")
      (node (ref "IC7") (pin "8") (pinfunction "RX_8") (pintype "bidirectional"))
    )
    (net (code "253") (name "unconnected-(IC8-PF-Pad7)") (class "Default")
      (node (ref "IC8") (pin "7") (pinfunction "PF_7") (pintype "bidirectional"))
    )
    (net (code "254") (name "unconnected-(IC8-RX-Pad8)") (class "Default")
      (node (ref "IC8") (pin "8") (pinfunction "RX_8") (pintype "bidirectional"))
    )
    (net (code "255") (name "unconnected-(IC10-PF-Pad7)") (class "Default")
      (node (ref "IC10") (pin "7") (pinfunction "PF_7") (pintype "bidirectional"))
    )
    (net (code "256") (name "unconnected-(IC10-RX-Pad8)") (class "Default")
      (node (ref "IC10") (pin "8") (pinfunction "RX_8") (pintype "bidirectional"))
    )
    (net (code "257") (name "unconnected-(IC11-PF-Pad7)") (class "Default")
      (node (ref "IC11") (pin "7") (pinfunction "PF_7") (pintype "bidirectional"))
    )
    (net (code "258") (name "unconnected-(IC11-RX-Pad8)") (class "Default")
      (node (ref "IC11") (pin "8") (pinfunction "RX_8") (pintype "bidirectional"))
    )
    (net (code "259") (name "unconnected-(IC12-PF-Pad7)") (class "Default")
      (node (ref "IC12") (pin "7") (pinfunction "PF_7") (pintype "bidirectional"))
    )
    (net (code "260") (name "unconnected-(IC12-RX-Pad8)") (class "Default")
      (node (ref "IC12") (pin "8") (pinfunction "RX_8") (pintype "bidirectional"))
    )
    (net (code "261") (name "unconnected-(IC14-PF-Pad7)") (class "Default")
      (node (ref "IC14") (pin "7") (pinfunction "PF_7") (pintype "bidirectional"))
    )
    (net (code "262") (name "unconnected-(IC14-RX-Pad8)") (class "Default")
      (node (ref "IC14") (pin "8") (pinfunction "RX_8") (pintype "bidirectional"))
    )
    (net (code "263") (name "unconnected-(IC15-GPIO27{slash}ADC1-Pad39)") (class "Default")
      (node (ref "IC15") (pin "39") (pinfunction "GPIO27/ADC1_39") (pintype "bidirectional"))
    )
    (net (code "264") (name "unconnected-(IC16-PF-Pad7)") (class "Default")
      (node (ref "IC16") (pin "7") (pinfunction "PF_7") (pintype "bidirectional"))
    )
    (net (code "265") (name "unconnected-(IC16-RX-Pad8)") (class "Default")
      (node (ref "IC16") (pin "8") (pinfunction "RX_8") (pintype "bidirectional"))
    )
    (net (code "266") (name "unconnected-(IC20-DNC-Pad7)") (class "Default")
      (node (ref "IC20") (pin "7") (pinfunction "DNC_7") (pintype "bidirectional"))
    )
    (net (code "267") (name "unconnected-(IC20-DUPLED-Pad26)") (class "Default")
      (node (ref "IC20") (pin "26") (pinfunction "DUPLED_26") (pintype "output"))
    )
    (net (code "268") (name "unconnected-(IC20-RSVD1-Pad23)") (class "Default")
      (node (ref "IC20") (pin "23") (pinfunction "RSVD1_23") (pintype "input"))
    )
    (net (code "269") (name "unconnected-(IC20-RSVD2-Pad38)") (class "Default")
      (node (ref "IC20") (pin "38") (pinfunction "RSVD2_38") (pintype "input"))
    )
    (net (code "270") (name "unconnected-(IC20-RSVD3-Pad39)") (class "Default")
      (node (ref "IC20") (pin "39") (pinfunction "RSVD3_39") (pintype "input"))
    )
    (net (code "271") (name "unconnected-(IC20-RSVD4-Pad40)") (class "Default")
      (node (ref "IC20") (pin "40") (pinfunction "RSVD4_40") (pintype "input"))
    )
    (net (code "272") (name "unconnected-(IC20-RSVD5-Pad41)") (class "Default")
      (node (ref "IC20") (pin "41") (pinfunction "RSVD5_41") (pintype "input"))
    )
    (net (code "273") (name "unconnected-(IC20-RSVD6-Pad42)") (class "Default")
      (node (ref "IC20") (pin "42") (pinfunction "RSVD6_42") (pintype "input"))
    )
    (net (code "274") (name "unconnected-(IC20-SPDLED-Pad24)") (class "Default")
      (node (ref "IC20") (pin "24") (pinfunction "SPDLED_24") (pintype "output"))
    )
    (net (code "275") (name "unconnected-(IC20-VBG-Pad18)") (class "Default")
      (node (ref "IC20") (pin "18") (pinfunction "VBG_18") (pintype "output"))
    )
    (net (code "276") (name "unconnected-(IC21-NC-Pad4)") (class "Default")
      (node (ref "IC21") (pin "4") (pinfunction "NC_4") (pintype "bidirectional"))
    )
    (net (code "277") (name "unconnected-(R149-5-PadD2)") (class "Default")
      (node (ref "R149") (pin "D2") (pinfunction "5_D2") (pintype "passive"))
    )
    (net (code "278") (name "unconnected-(USB1-SBU1-PadA8)") (class "Default")
      (node (ref "USB1") (pin "A8") (pinfunction "SBU1_A8") (pintype "bidirectional"))
    )
    (net (code "279") (name "unconnected-(USB1-SBU2-PadB8)") (class "Default")
      (node (ref "USB1") (pin "B8") (pinfunction "SBU2_B8") (pintype "bidirectional"))
    )
    (net (code "280") (name "~{ACT}") (class "Default")
      (node (ref "IC20") (pin "27") (pinfunction "ACTLED_27") (pintype "output"))
      (node (ref "R142") (pin "1") (pinfunction "1_1") (pintype "passive"))
    )
    (net (code "281") (name "~{LINK}") (class "Default")
      (node (ref "IC20") (pin "25") (pinfunction "LINKLED_25") (pintype "output"))
      (node (ref "R141") (pin "1") (pinfunction "1_1") (pintype "passive"))
    )
    (net (code "282") (name "~{QSPI_SS}") (class "Default")
      (node (ref "IC15") (pin "56") (pinfunction "QSPI_SS_N_56") (pintype "bidirectional"))
      (node (ref "IC18") (pin "1") (pinfunction "~{CS}_1") (pintype "bidirectional"))
      (node (ref "R111") (pin "1") (pinfunction "1_1") (pintype "passive"))
      (node (ref "R112") (pin "2") (pinfunction "2_2") (pintype "passive"))
    )
    (net (code "283") (name "~{TX_OUT}") (class "Default")
      (node (ref "IC22") (pin "3") (pinfunction "+IN_3") (pintype "input"))
      (node (ref "IC9") (pin "6") (pinfunction "~{Y}_6") (pintype "bidirectional"))
      (node (ref "R92") (pin "1") (pinfunction "1_1") (pintype "passive"))
    )
    (net (code "284") (name "~{W5500_CS}") (class "Default")
      (node (ref "IC15") (pin "28") (pinfunction "GPIO17_28") (pintype "bidirectional"))
      (node (ref "IC20") (pin "32") (pinfunction "~{SCSN}_32") (pintype "input"))
    )
    (net (code "285") (name "~{W5500_INT}") (class "Default")
      (node (ref "IC15") (pin "32") (pinfunction "GPIO21_32") (pintype "bidirectional"))
      (node (ref "IC20") (pin "36") (pinfunction "~{INTN}_36") (pintype "input"))
    )
    (net (code "286") (name "~{W5500_RST}") (class "Default")
      (node (ref "IC15") (pin "31") (pinfunction "GPIO20_31") (pintype "bidirectional"))
      (node (ref "IC20") (pin "37") (pinfunction "~{RSTN}_37") (pintype "input"))
      (node (ref "R145") (pin "1") (pinfunction "1_1") (pintype "passive"))
    )
  )
)
